# edcmain.net
KiCad netlist of a schematic drawn in EAGLE
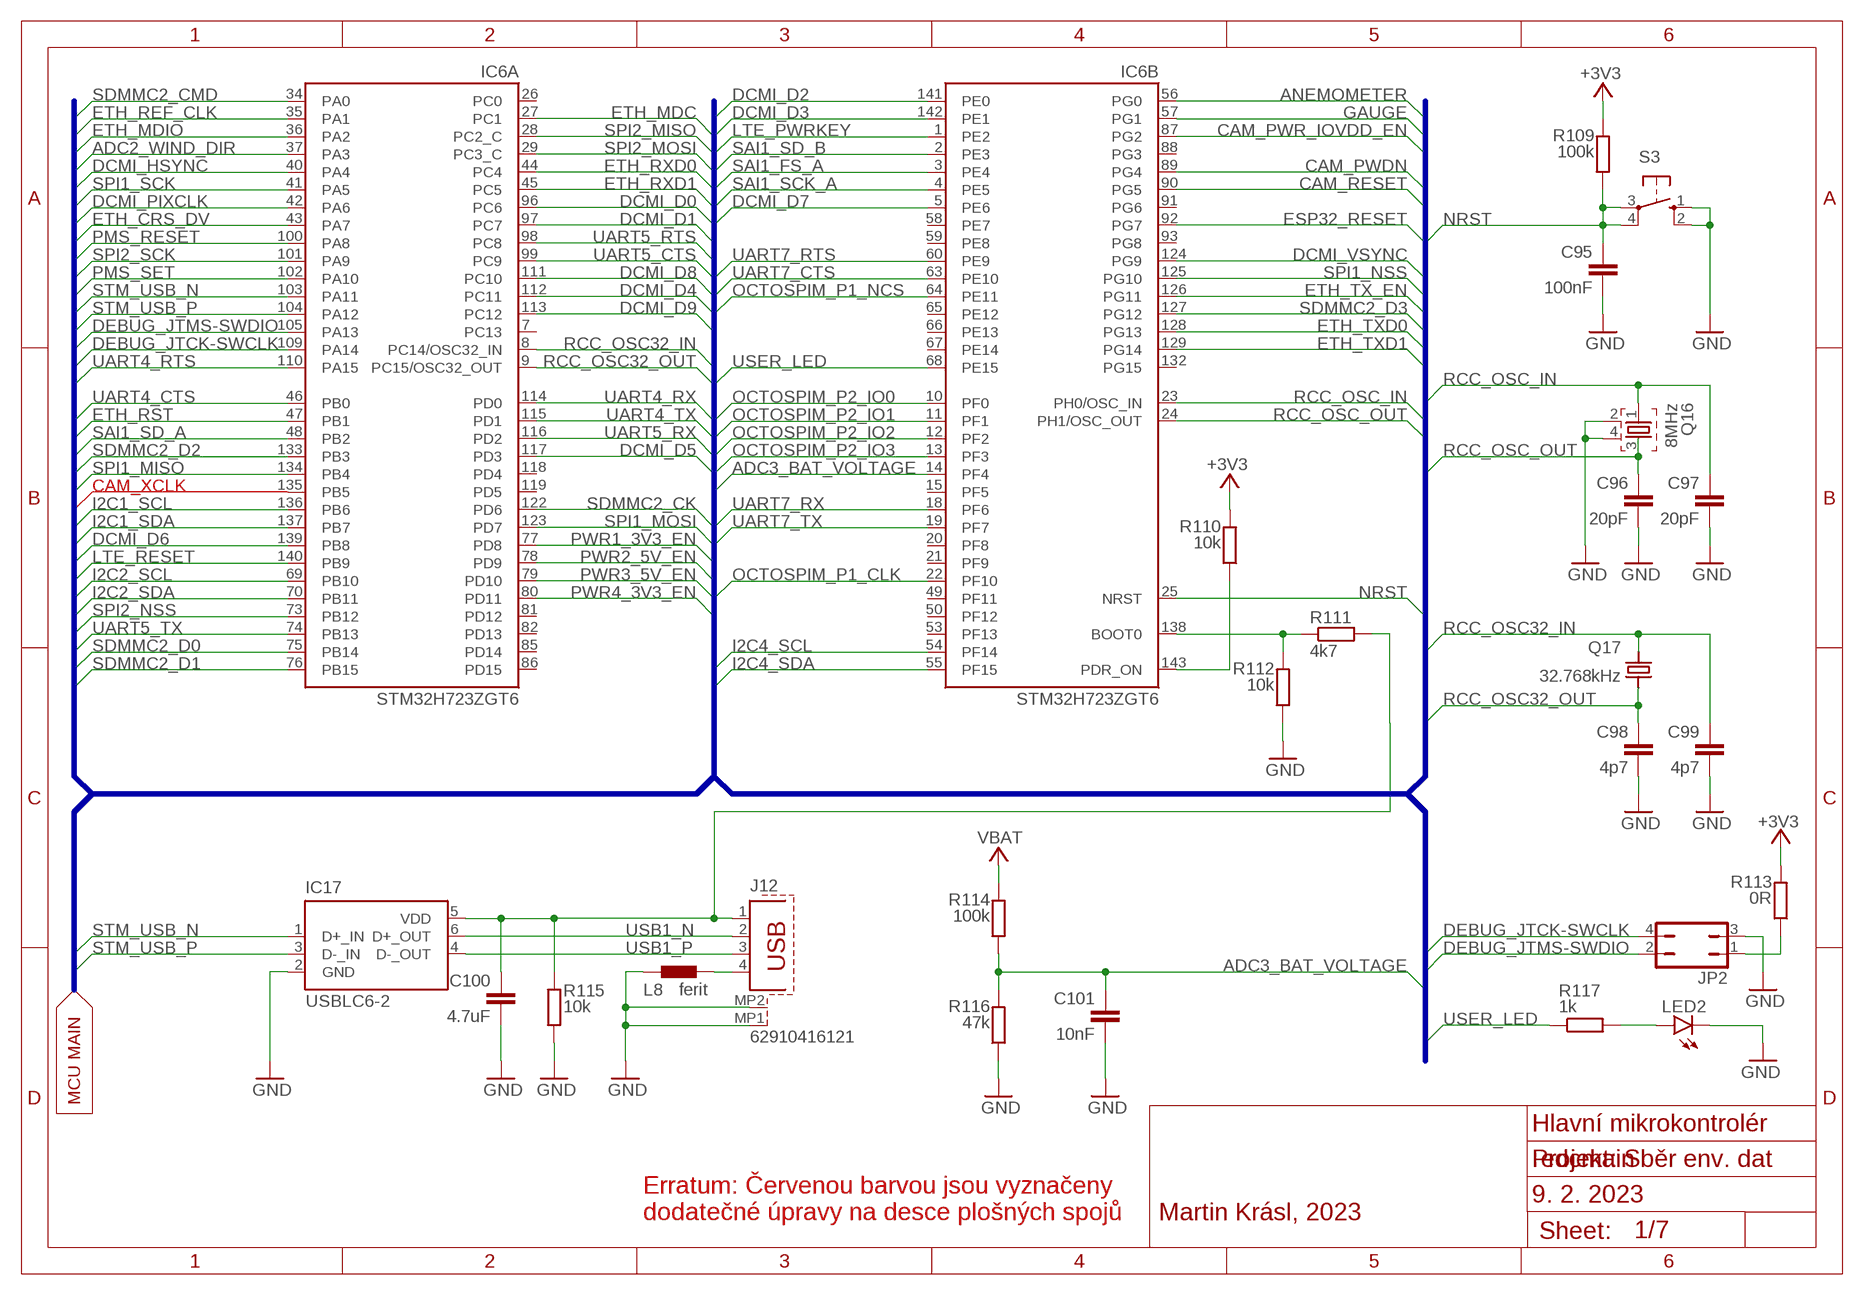
[diagram p0: schematic, sheet 1]
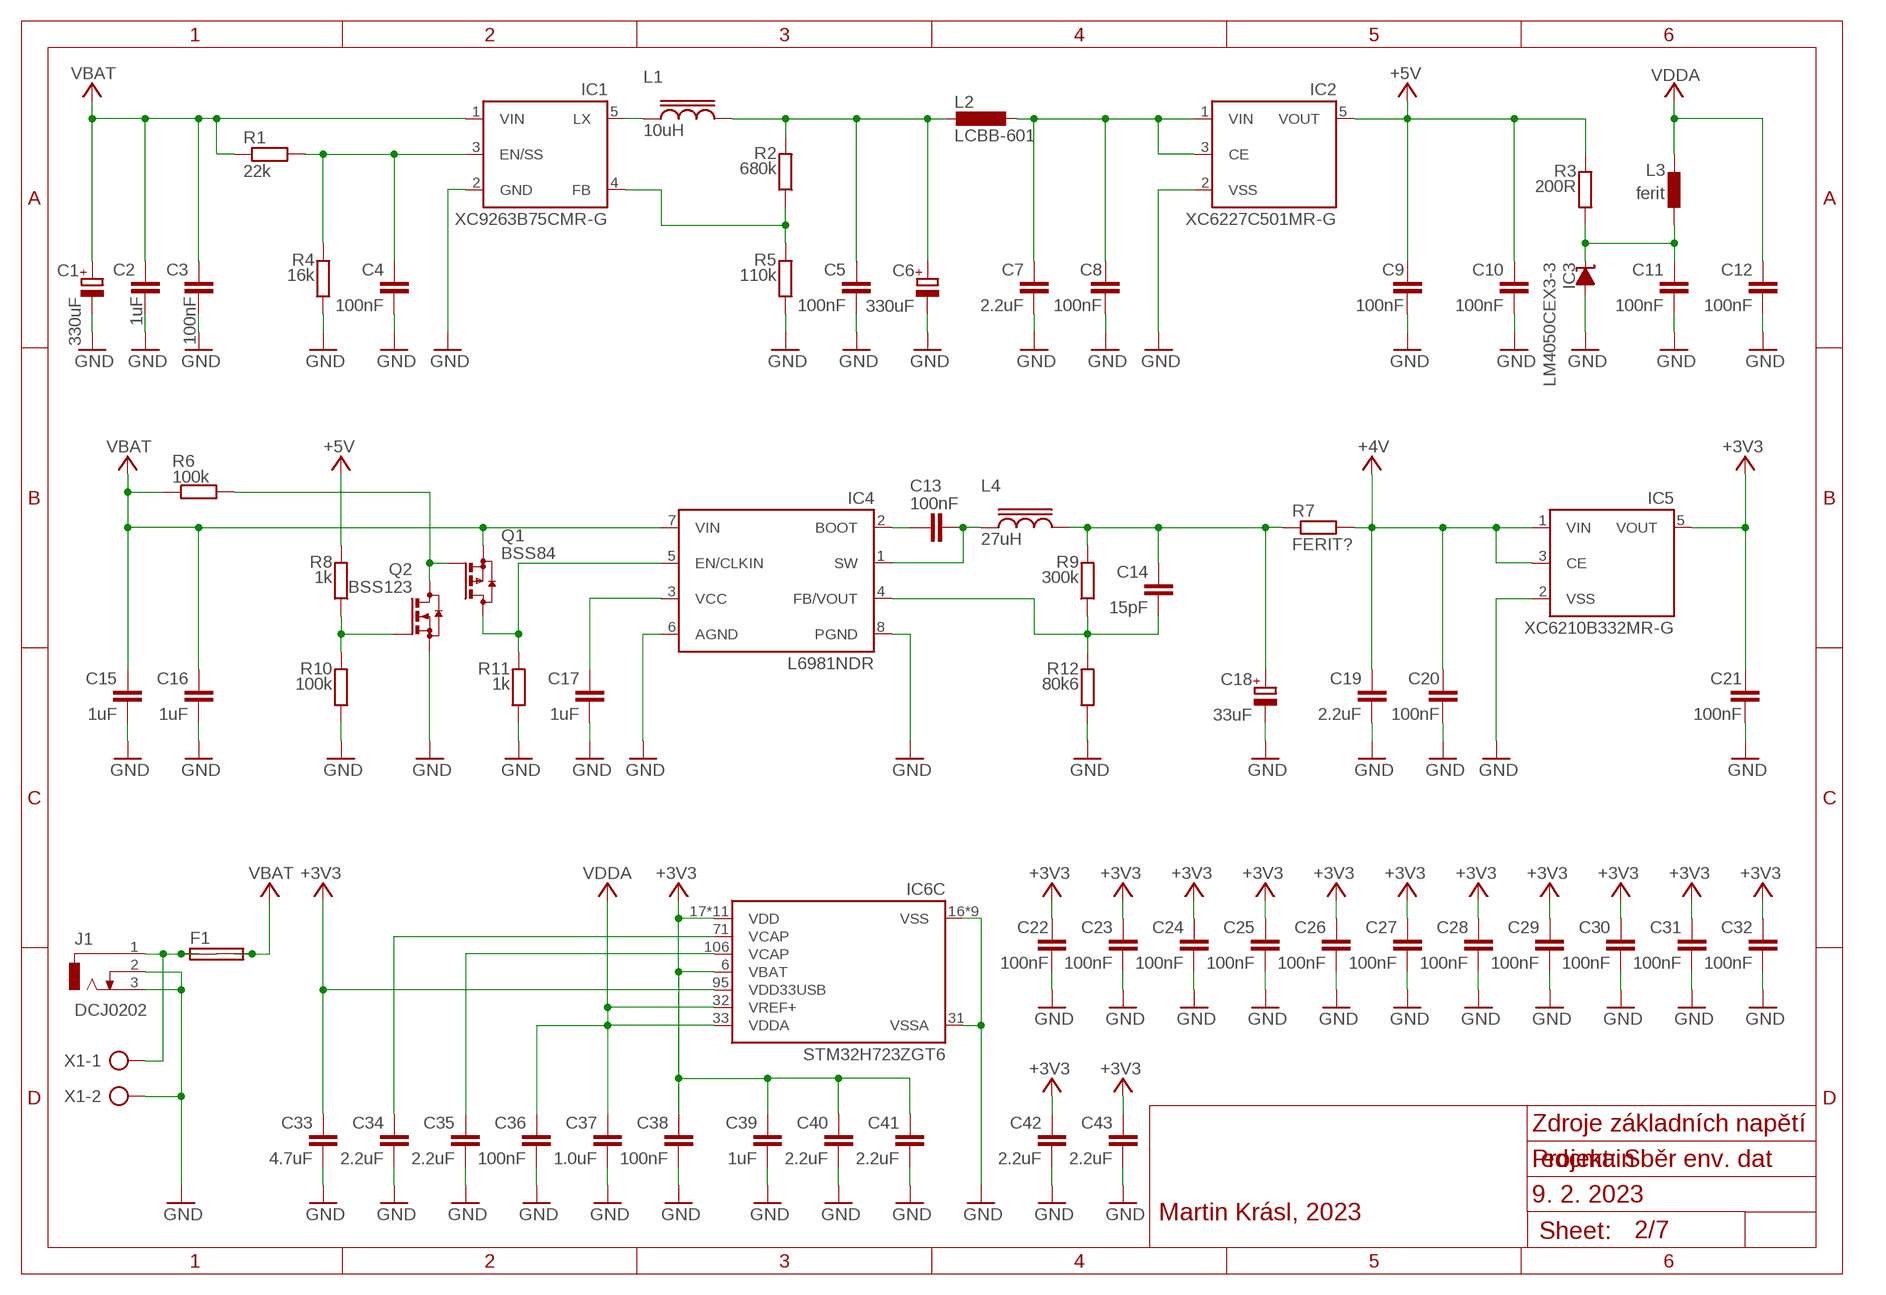
[diagram p1: schematic, sheet 2]
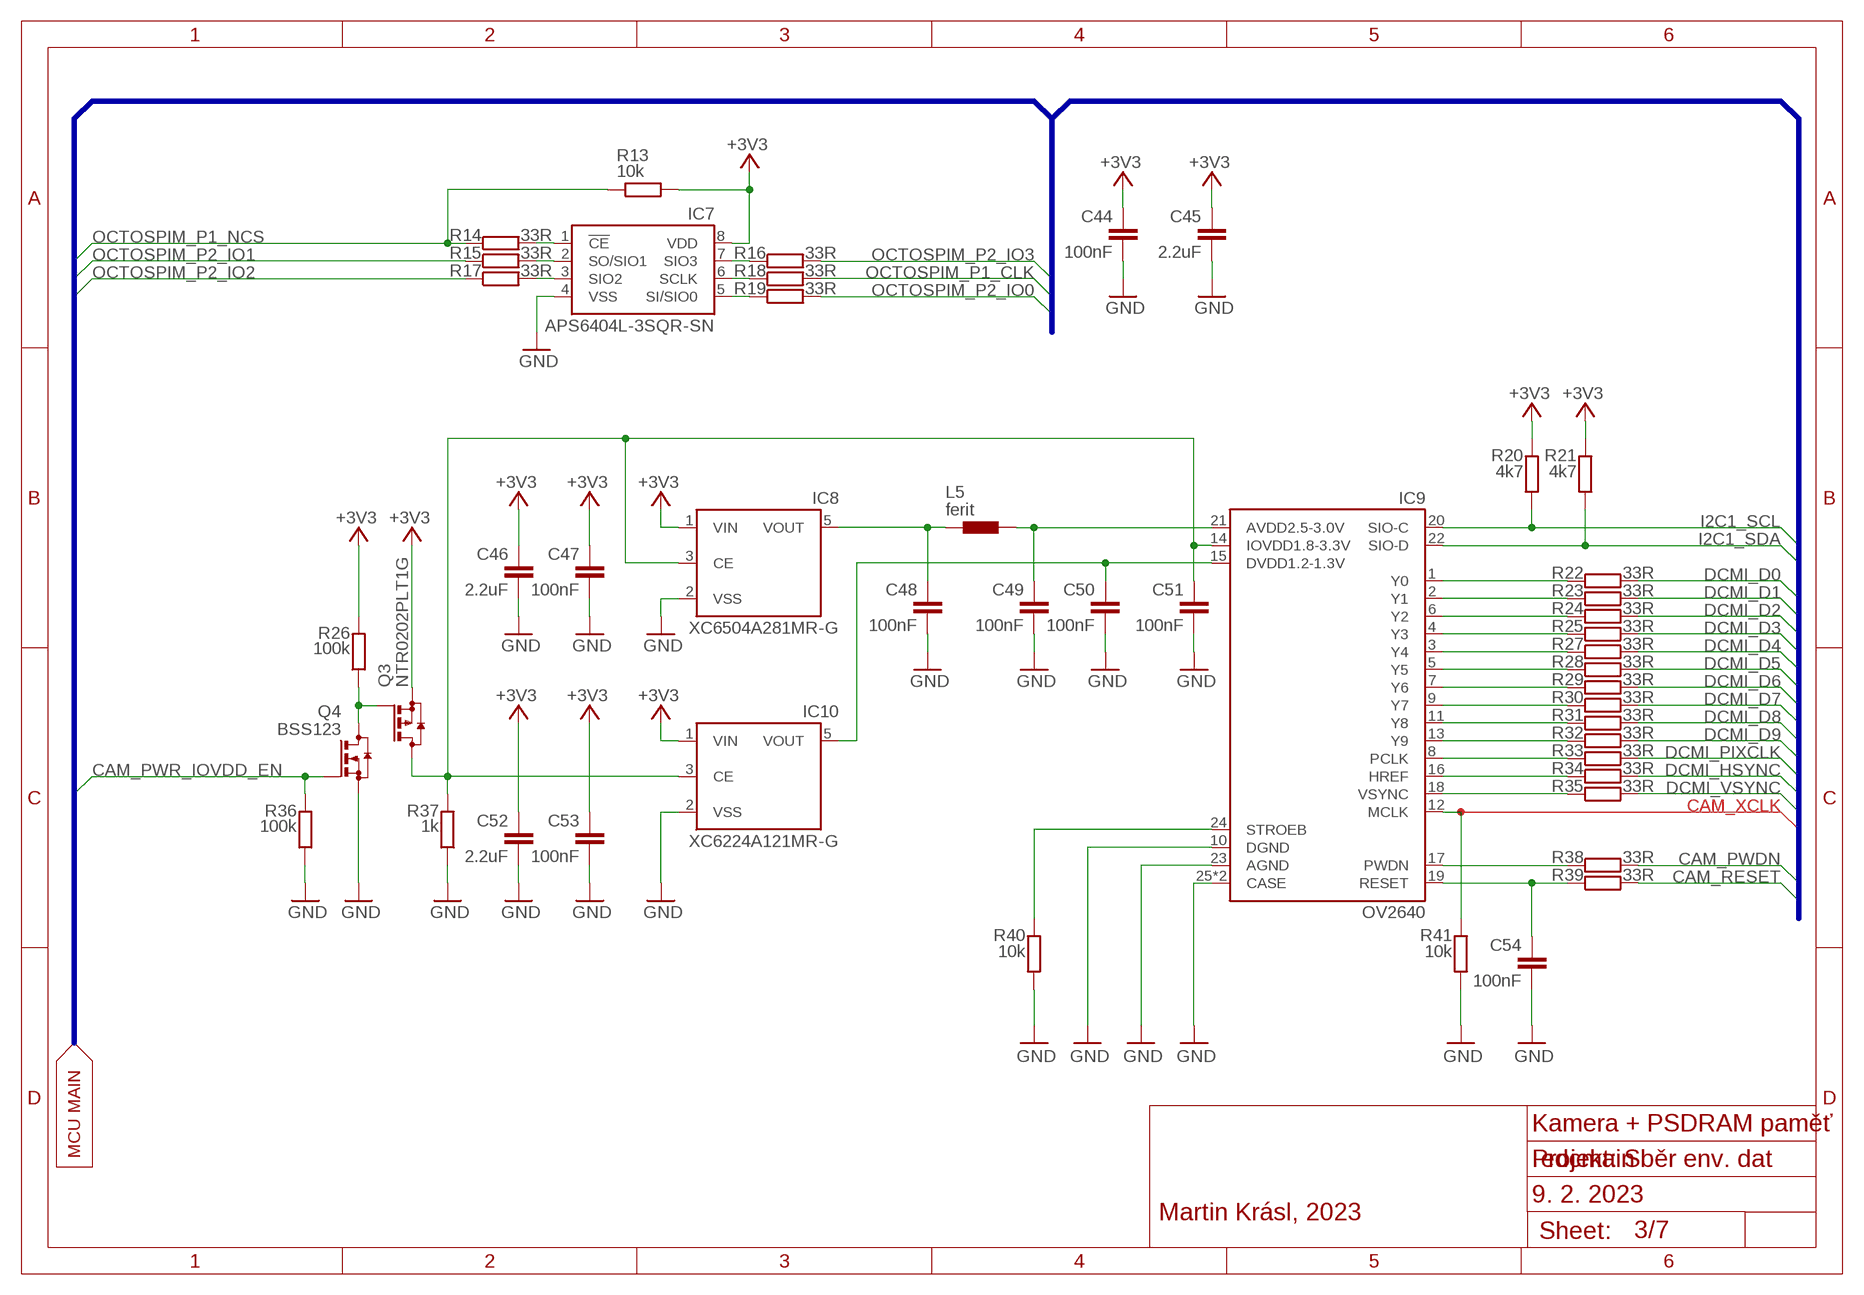
[diagram p2: schematic, sheet 3]
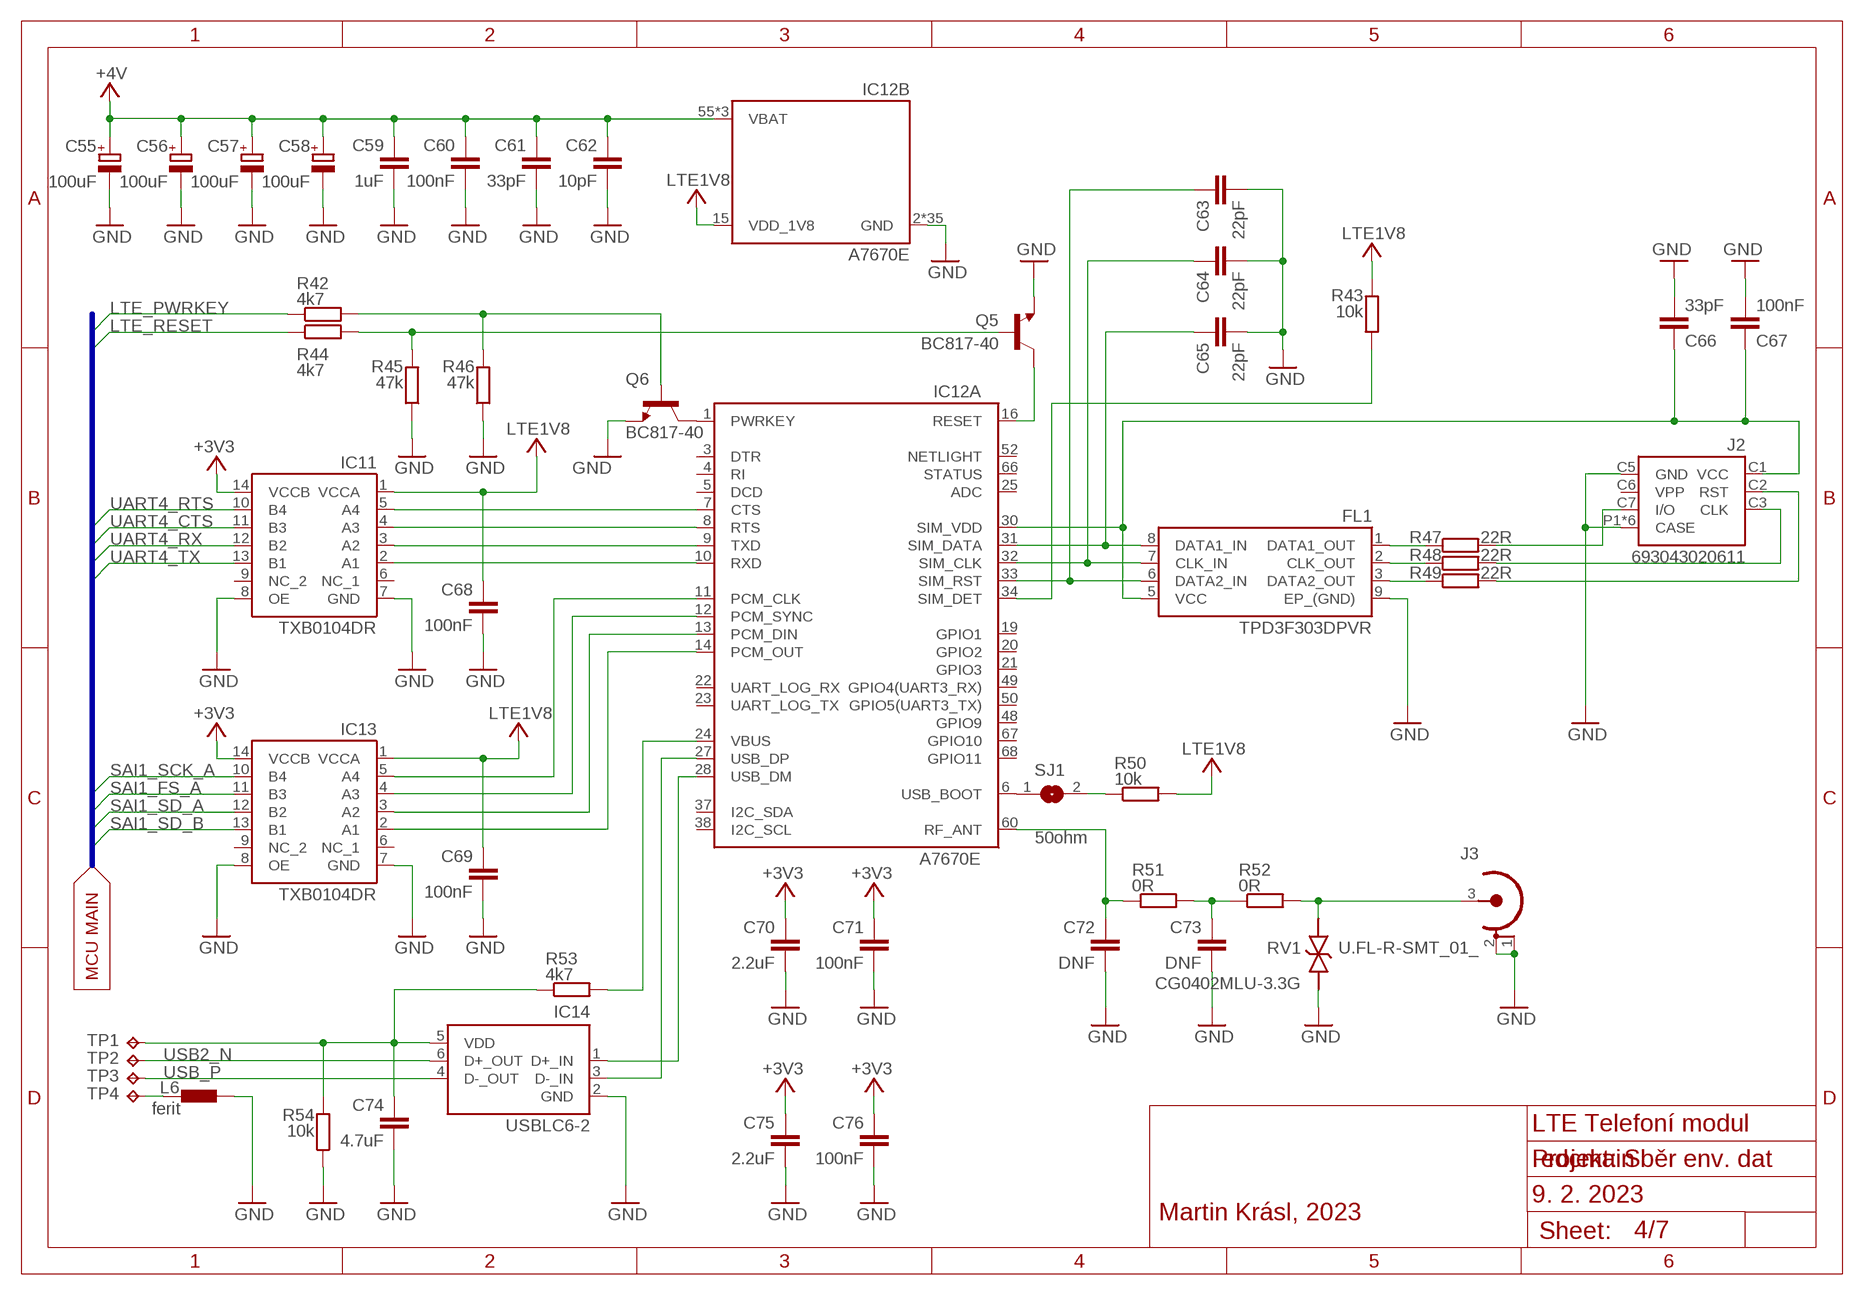
[diagram p3: schematic, sheet 4]
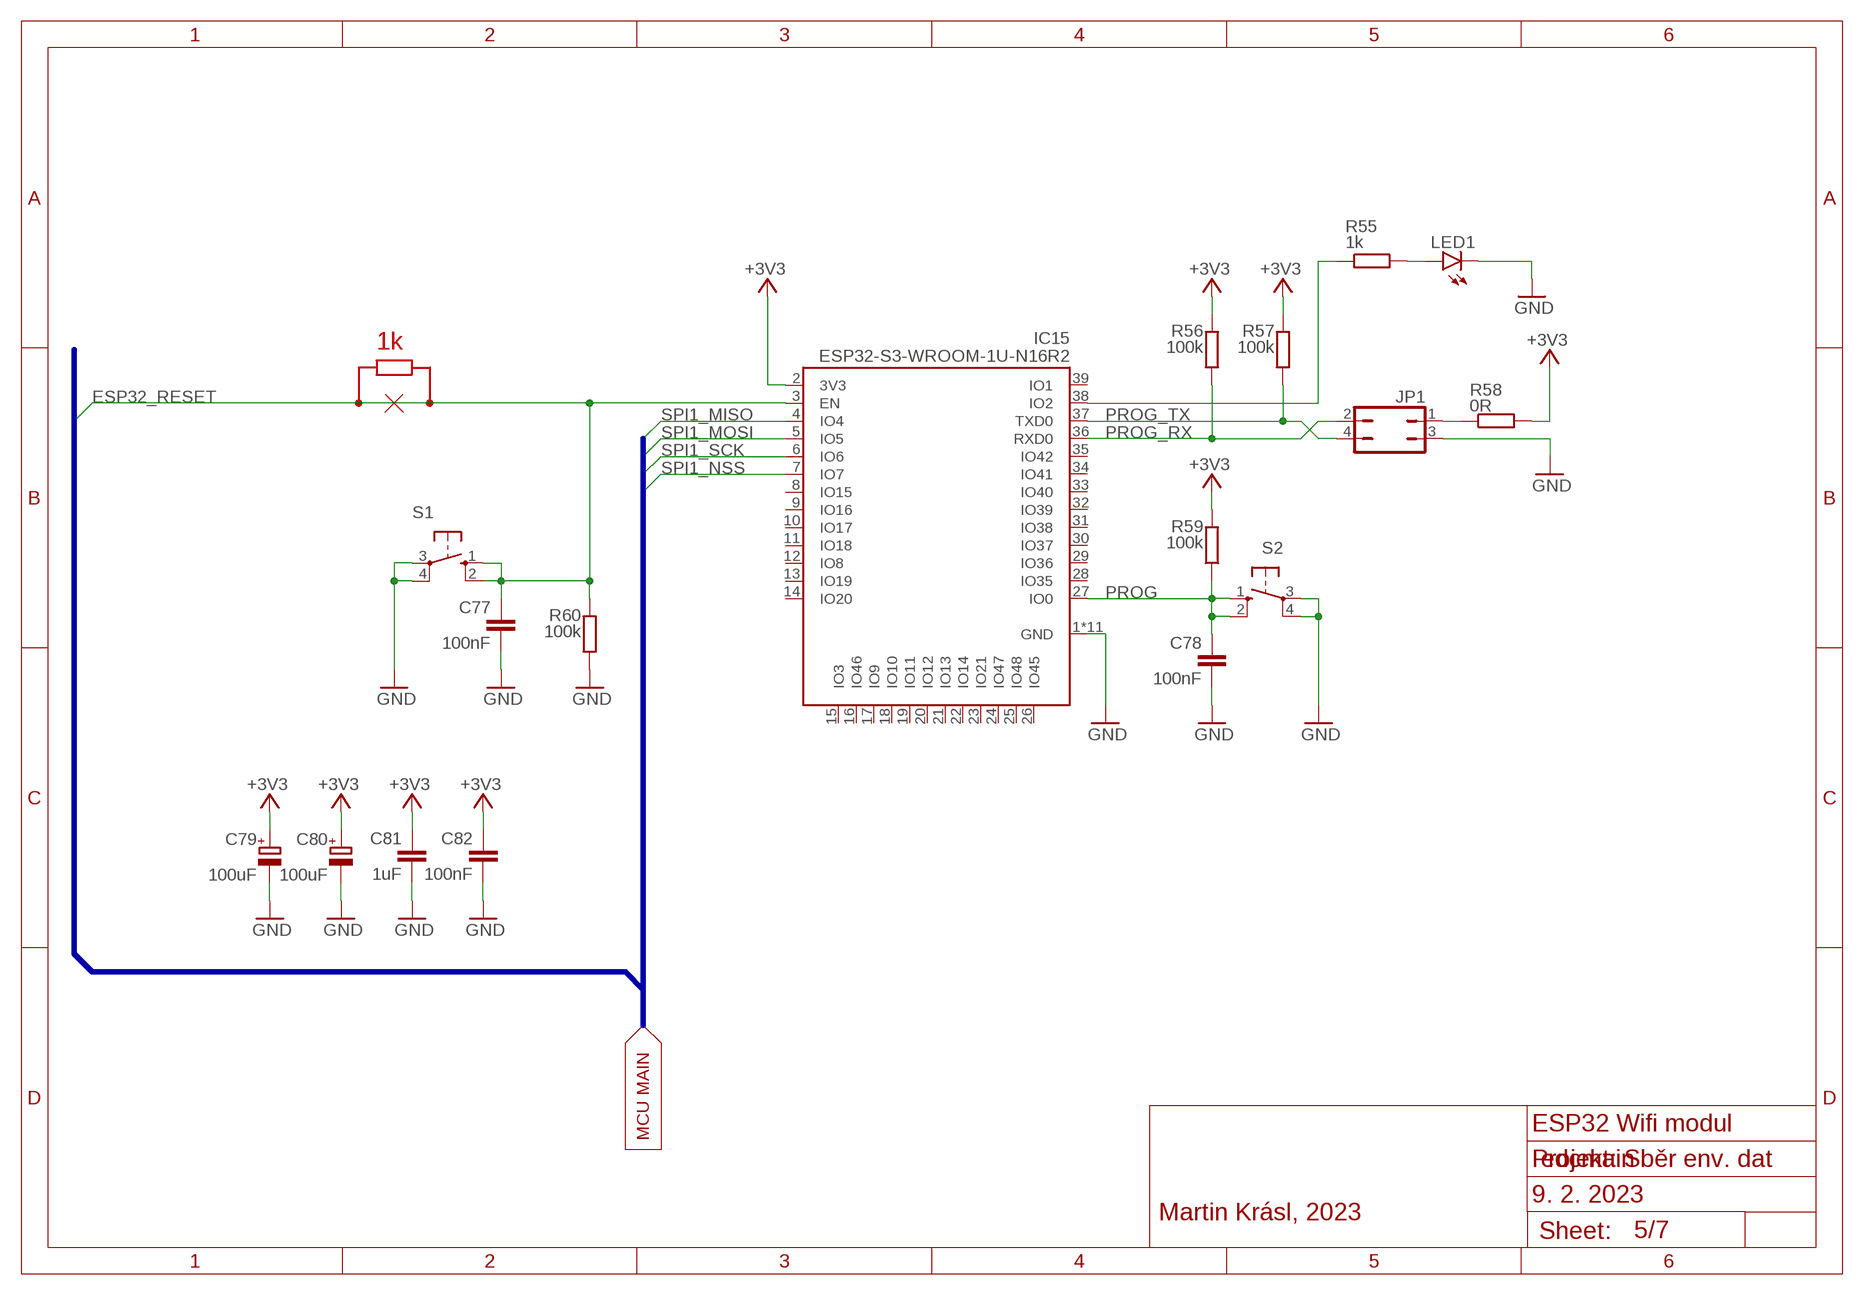
[diagram p4: schematic, sheet 5]
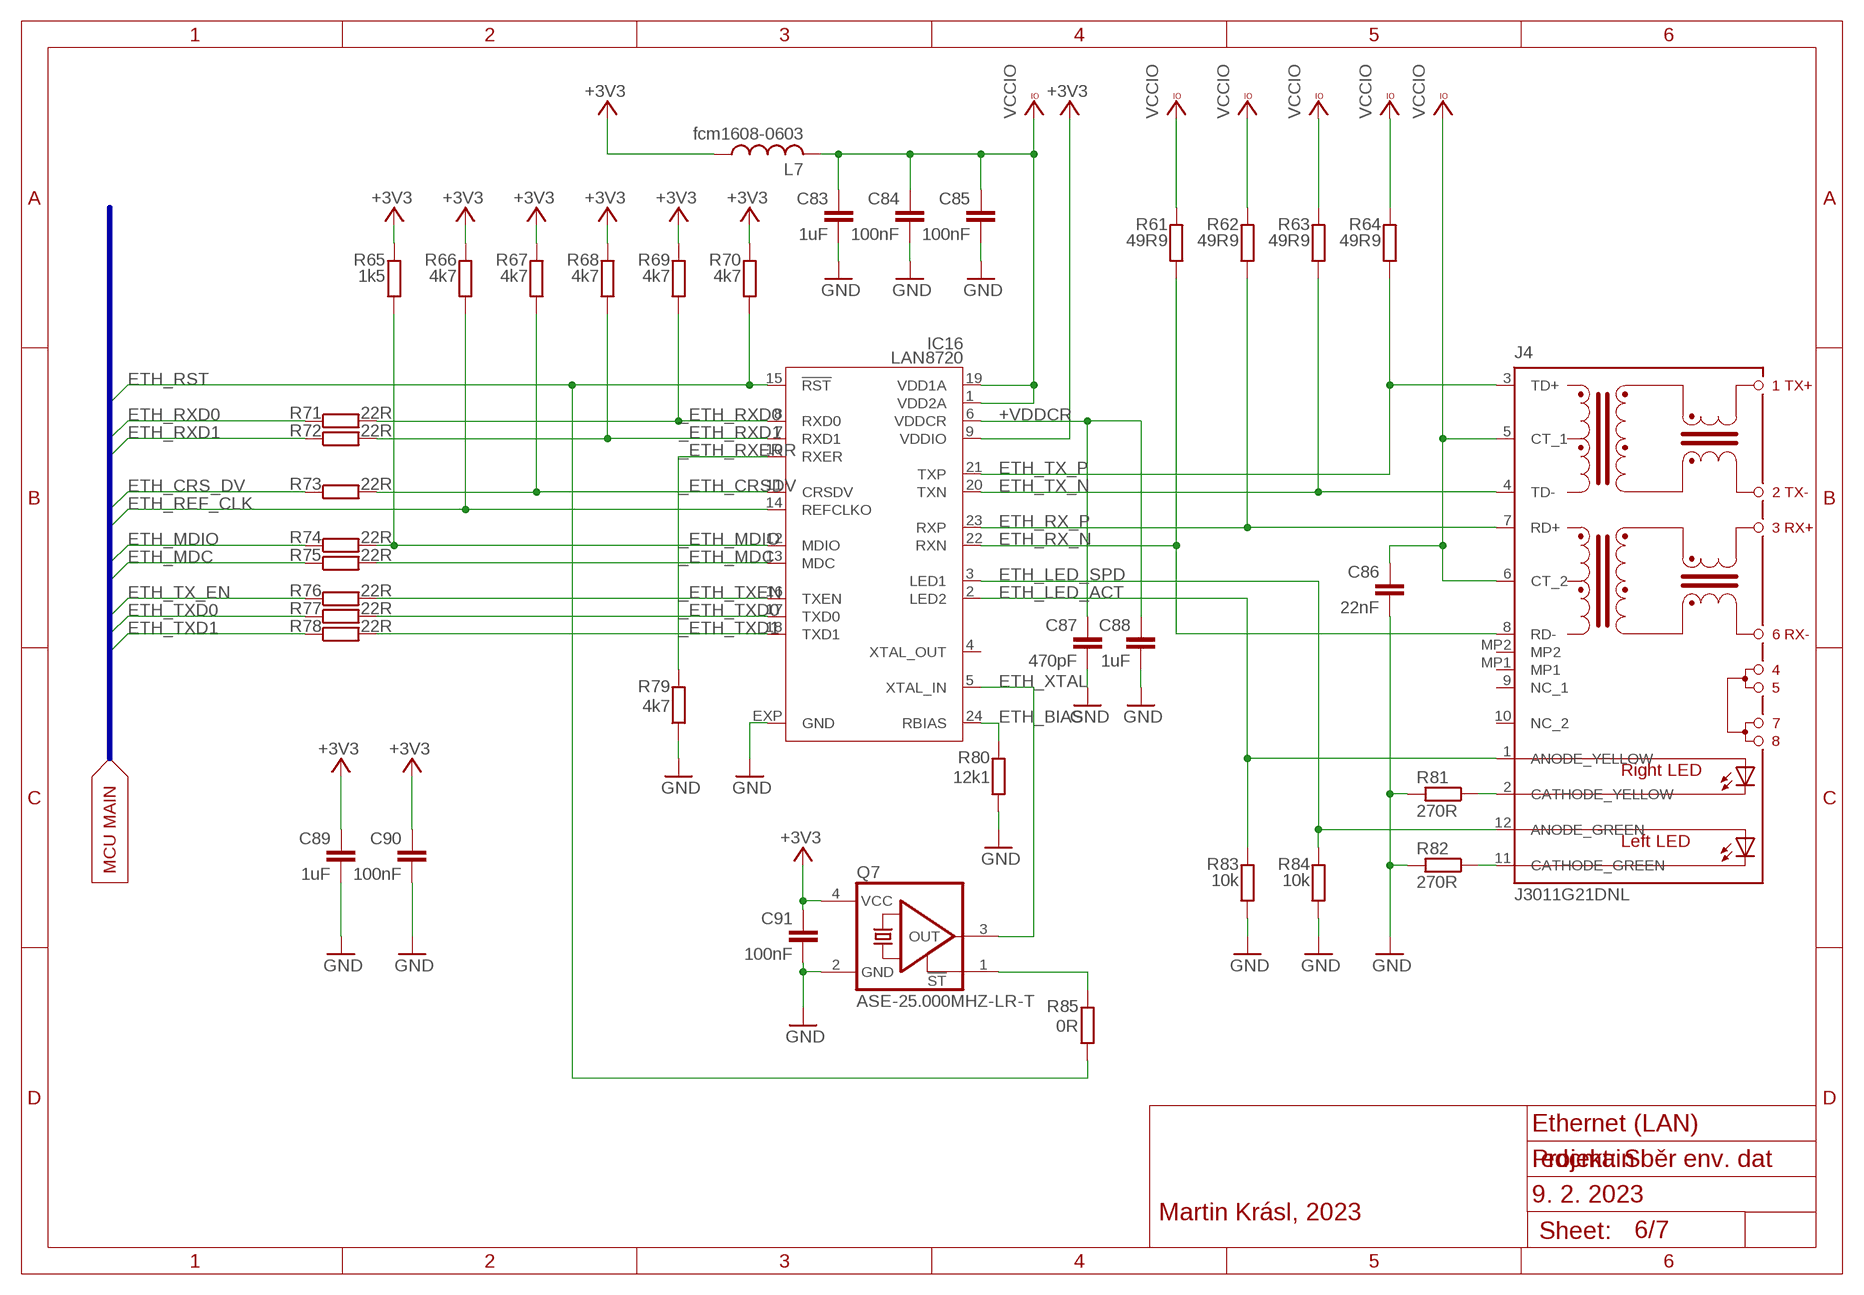
[diagram p5: schematic, sheet 6]
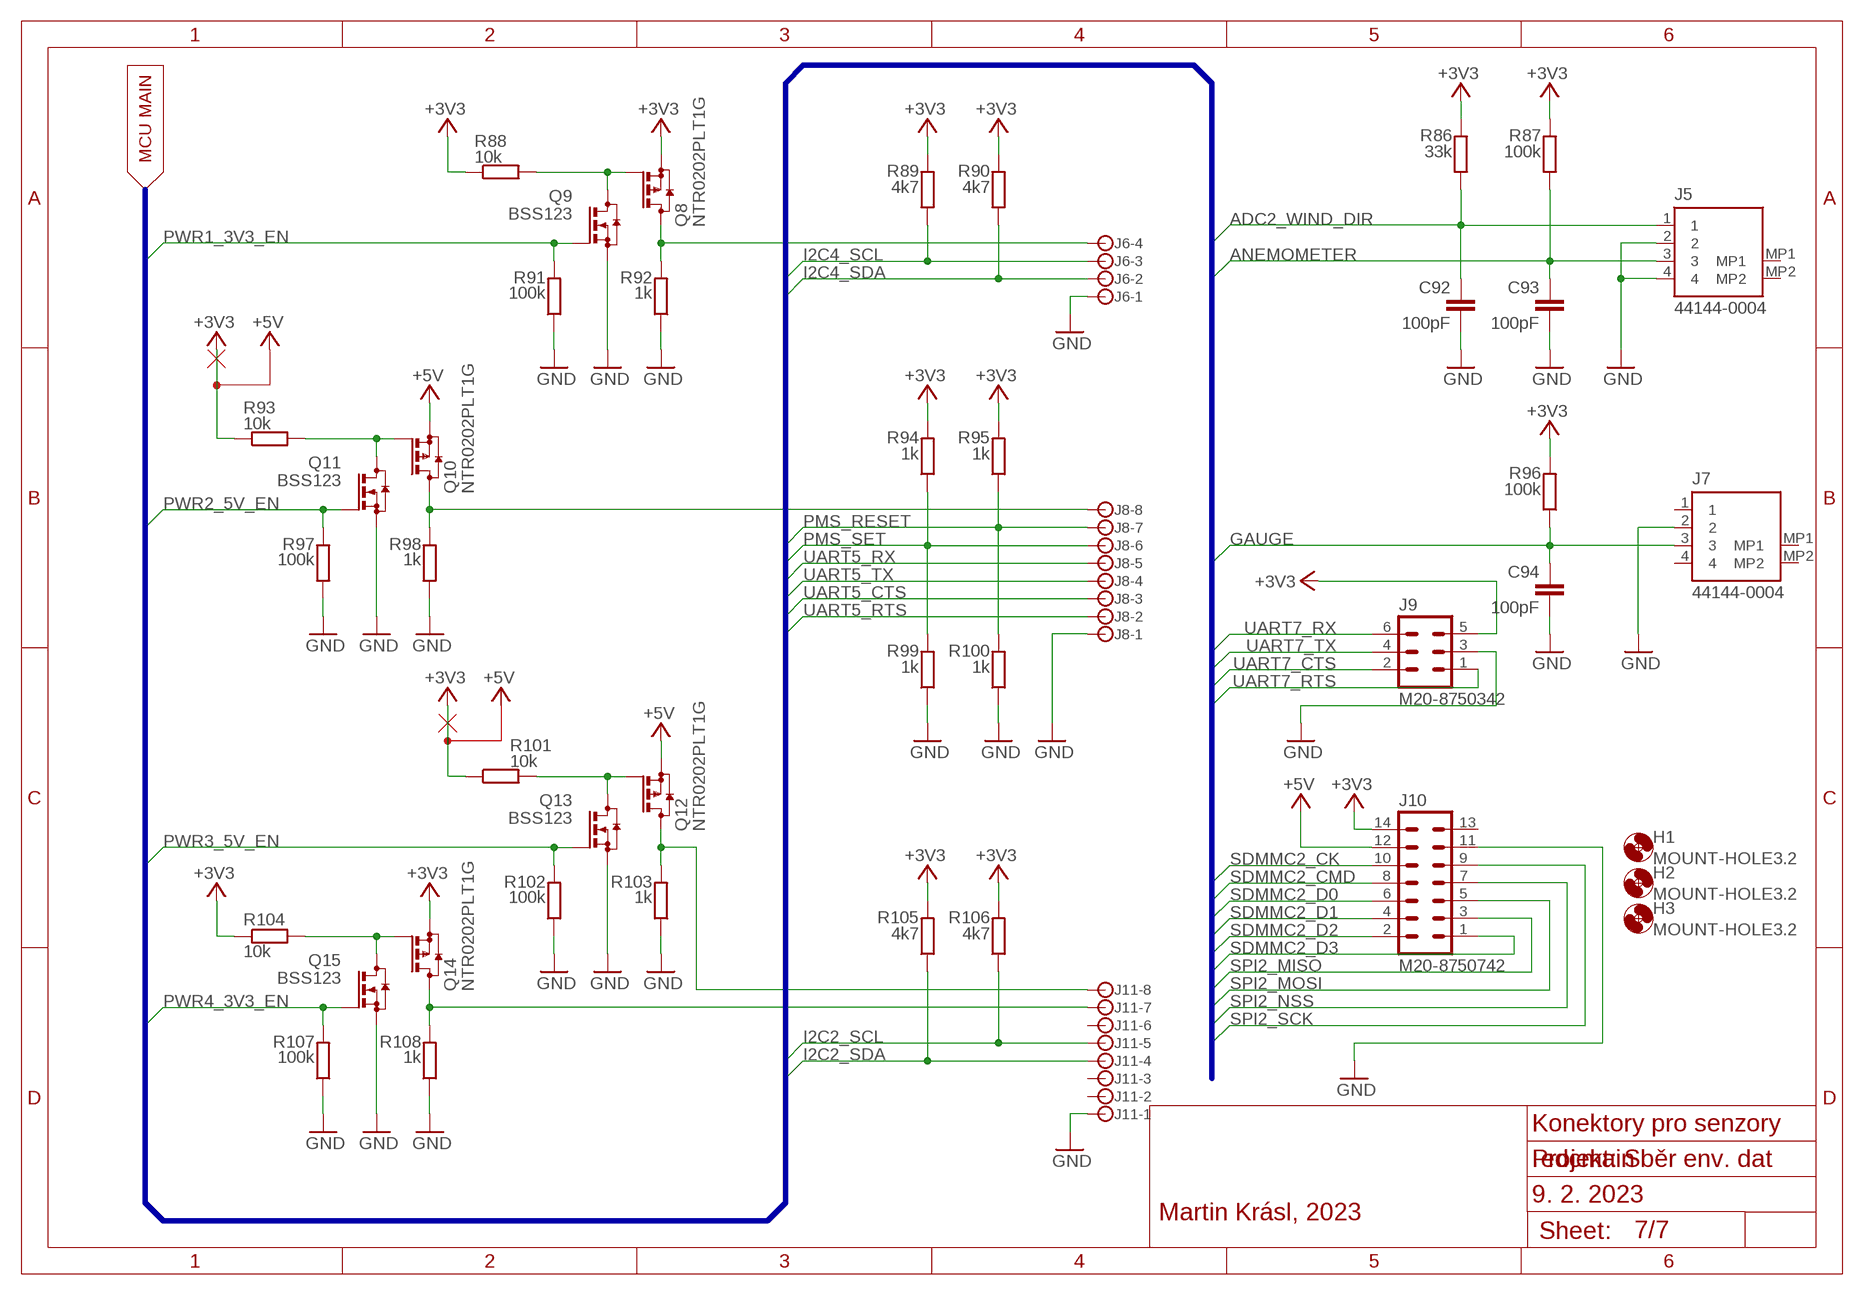
[diagram p6: schematic, sheet 7]

(export (version "E")
  (design (tool "Eeschema 10.0.6"))
  (components
    (comp (ref "C77")
      (value "100nF")
      (footprint "eagle-import:C0402")
      (libsource (lib "eagle-import") (part "C-EUC0402"))
    )
    (comp (ref "C78")
      (value "100nF")
      (footprint "eagle-import:C0402")
      (libsource (lib "eagle-import") (part "C-EUC0402"))
    )
    (comp (ref "C79")
      (value "100uF")
      (footprint "eagle-import:B_3528-21R")
      (libsource (lib "eagle-import") (part "CPOL-EUB/3528-21R"))
    )
    (comp (ref "C80")
      (value "100uF")
      (footprint "eagle-import:B_3528-21R")
      (libsource (lib "eagle-import") (part "CPOL-EUB/3528-21R"))
    )
    (comp (ref "C81")
      (value "1uF")
      (footprint "eagle-import:C0805")
      (libsource (lib "eagle-import") (part "C-EUC0805"))
    )
    (comp (ref "C82")
      (value "100nF")
      (footprint "eagle-import:C0402")
      (libsource (lib "eagle-import") (part "C-EUC0402"))
    )
    (comp (ref "IC15")
      (value "ESP32-S3-WROOM-1U-N16R2")
      (footprint "eagle-import:ESP32S3WROOM1UN16R2")
      (fields (field (name "MOUSER_PART_NUMBER") "356-ESP32S3WM1UN16R2"))
      (libsource (lib "eagle-import") (part "ESP32-S3-WROOM-1U-N16R2"))
    )
    (comp (ref "JP1")
      (value "JP2Q")
      (footprint "eagle-import:JP2Q")
      (libsource (lib "eagle-import") (part "JP2Q"))
    )
    (comp (ref "LED1")
      (value "LEDCHIP-LED0805")
      (footprint "eagle-import:CHIP-LED0805")
      (libsource (lib "eagle-import") (part "LEDCHIP-LED0805"))
    )
    (comp (ref "R55")
      (value "1k")
      (footprint "eagle-import:R0402")
      (libsource (lib "eagle-import") (part "R-EU_R0402"))
    )
    (comp (ref "R56")
      (value "100k")
      (footprint "eagle-import:R0402")
      (libsource (lib "eagle-import") (part "R-EU_R0402"))
    )
    (comp (ref "R57")
      (value "100k")
      (footprint "eagle-import:R0402")
      (libsource (lib "eagle-import") (part "R-EU_R0402"))
    )
    (comp (ref "R58")
      (value "0R")
      (footprint "eagle-import:R0402")
      (libsource (lib "eagle-import") (part "R-EU_R0402"))
    )
    (comp (ref "R59")
      (value "100k")
      (footprint "eagle-import:R0402")
      (libsource (lib "eagle-import") (part "R-EU_R0402"))
    )
    (comp (ref "R60")
      (value "100k")
      (footprint "eagle-import:R0402")
      (libsource (lib "eagle-import") (part "R-EU_R0402"))
    )
    (comp (ref "S1")
      (value "10-XX")
      (footprint "eagle-import:B3F-10XX")
      (fields (field (name "MPN") "B3F-1000"))
      (libsource (lib "eagle-import") (part "10-XX"))
    )
    (comp (ref "S2")
      (value "10-XX")
      (footprint "eagle-import:B3F-10XX")
      (fields (field (name "MPN") "B3F-1000"))
      (libsource (lib "eagle-import") (part "10-XX"))
    )
    (comp (ref "C44")
      (value "100nF")
      (footprint "eagle-import:C0402")
      (libsource (lib "eagle-import") (part "C-EUC0402"))
    )
    (comp (ref "C45")
      (value "2.2uF")
      (footprint "eagle-import:C0402")
      (libsource (lib "eagle-import") (part "C-EUC0402"))
    )
    (comp (ref "C46")
      (value "2.2uF")
      (footprint "eagle-import:C0402")
      (libsource (lib "eagle-import") (part "C-EUC0402"))
    )
    (comp (ref "C47")
      (value "100nF")
      (footprint "eagle-import:C0402")
      (libsource (lib "eagle-import") (part "C-EUC0402"))
    )
    (comp (ref "C48")
      (value "100nF")
      (footprint "eagle-import:C0402")
      (libsource (lib "eagle-import") (part "C-EUC0402"))
    )
    (comp (ref "C49")
      (value "100nF")
      (footprint "eagle-import:C0402")
      (libsource (lib "eagle-import") (part "C-EUC0402"))
    )
    (comp (ref "C50")
      (value "100nF")
      (footprint "eagle-import:C0402")
      (libsource (lib "eagle-import") (part "C-EUC0402"))
    )
    (comp (ref "C51")
      (value "100nF")
      (footprint "eagle-import:C0402")
      (libsource (lib "eagle-import") (part "C-EUC0402"))
    )
    (comp (ref "C52")
      (value "2.2uF")
      (footprint "eagle-import:C0805")
      (libsource (lib "eagle-import") (part "C-EUC0805"))
    )
    (comp (ref "C53")
      (value "100nF")
      (footprint "eagle-import:C0402")
      (libsource (lib "eagle-import") (part "C-EUC0402"))
    )
    (comp (ref "C54")
      (value "100nF")
      (footprint "eagle-import:C0402")
      (libsource (lib "eagle-import") (part "C-EUC0402"))
    )
    (comp (ref "IC7")
      (value "APS6404L-3SQR-SN")
      (footprint "eagle-import:SOP08")
      (libsource (lib "eagle-import") (part "APS6404L-3SQR-SN"))
    )
    (comp (ref "IC8")
      (value "XC6504A281MR-G")
      (footprint "eagle-import:SOT95P280X130-5N")
      (fields
        (field (name "MANUFACTURER_PART_NUMBER") "XC6210B332MR-G")
        (field (name "MOUSER_PART_NUMBER") "865-XC6210B332MR-G")
      )
      (libsource (lib "eagle-import") (part "XC6210B332MR-G"))
    )
    (comp (ref "IC9")
      (value "OV2640")
      (footprint "eagle-import:XF2M-2415-1A-SWAP")
      (libsource (lib "eagle-import") (part "OV2640"))
    )
    (comp (ref "IC10")
      (value "XC6224A121MR-G")
      (footprint "eagle-import:SOT95P280X130-5N")
      (fields
        (field (name "MANUFACTURER_PART_NUMBER") "XC6210B332MR-G")
        (field (name "MOUSER_PART_NUMBER") "865-XC6210B332MR-G")
      )
      (libsource (lib "eagle-import") (part "XC6210B332MR-G"))
    )
    (comp (ref "L5")
      (value "ferit")
      (footprint "eagle-import:0402")
      (libsource (lib "eagle-import") (part "BLM15HB121SN1"))
    )
    (comp (ref "Q3")
      (value "NTR0202PLT1G")
      (footprint "eagle-import:SOT23")
      (libsource (lib "eagle-import") (part "BSS84"))
    )
    (comp (ref "Q4")
      (value "BSS123")
      (footprint "eagle-import:SOT23")
      (libsource (lib "eagle-import") (part "BSS123"))
    )
    (comp (ref "R13")
      (value "10k")
      (footprint "eagle-import:R0402")
      (libsource (lib "eagle-import") (part "R-EU_R0402"))
    )
    (comp (ref "R14")
      (value "33R")
      (footprint "eagle-import:R0402")
      (libsource (lib "eagle-import") (part "R-EU_R0402"))
    )
    (comp (ref "R15")
      (value "33R")
      (footprint "eagle-import:R0402")
      (libsource (lib "eagle-import") (part "R-EU_R0402"))
    )
    (comp (ref "R16")
      (value "33R")
      (footprint "eagle-import:R0402")
      (libsource (lib "eagle-import") (part "R-EU_R0402"))
    )
    (comp (ref "R17")
      (value "33R")
      (footprint "eagle-import:R0402")
      (libsource (lib "eagle-import") (part "R-EU_R0402"))
    )
    (comp (ref "R18")
      (value "33R")
      (footprint "eagle-import:R0402")
      (libsource (lib "eagle-import") (part "R-EU_R0402"))
    )
    (comp (ref "R19")
      (value "33R")
      (footprint "eagle-import:R0402")
      (libsource (lib "eagle-import") (part "R-EU_R0402"))
    )
    (comp (ref "R20")
      (value "4k7")
      (footprint "eagle-import:R0402")
      (libsource (lib "eagle-import") (part "R-EU_R0402"))
    )
    (comp (ref "R21")
      (value "4k7")
      (footprint "eagle-import:R0402")
      (libsource (lib "eagle-import") (part "R-EU_R0402"))
    )
    (comp (ref "R22")
      (value "33R")
      (footprint "eagle-import:R0402")
      (libsource (lib "eagle-import") (part "R-EU_R0402"))
    )
    (comp (ref "R23")
      (value "33R")
      (footprint "eagle-import:R0402")
      (libsource (lib "eagle-import") (part "R-EU_R0402"))
    )
    (comp (ref "R24")
      (value "33R")
      (footprint "eagle-import:R0402")
      (libsource (lib "eagle-import") (part "R-EU_R0402"))
    )
    (comp (ref "R25")
      (value "33R")
      (footprint "eagle-import:R0402")
      (libsource (lib "eagle-import") (part "R-EU_R0402"))
    )
    (comp (ref "R26")
      (value "100k")
      (footprint "eagle-import:R0402")
      (libsource (lib "eagle-import") (part "R-EU_R0402"))
    )
    (comp (ref "R27")
      (value "33R")
      (footprint "eagle-import:R0402")
      (libsource (lib "eagle-import") (part "R-EU_R0402"))
    )
    (comp (ref "R28")
      (value "33R")
      (footprint "eagle-import:R0402")
      (libsource (lib "eagle-import") (part "R-EU_R0402"))
    )
    (comp (ref "R29")
      (value "33R")
      (footprint "eagle-import:R0402")
      (libsource (lib "eagle-import") (part "R-EU_R0402"))
    )
    (comp (ref "R30")
      (value "33R")
      (footprint "eagle-import:R0402")
      (libsource (lib "eagle-import") (part "R-EU_R0402"))
    )
    (comp (ref "R31")
      (value "33R")
      (footprint "eagle-import:R0402")
      (libsource (lib "eagle-import") (part "R-EU_R0402"))
    )
    (comp (ref "R32")
      (value "33R")
      (footprint "eagle-import:R0402")
      (libsource (lib "eagle-import") (part "R-EU_R0402"))
    )
    (comp (ref "R33")
      (value "33R")
      (footprint "eagle-import:R0402")
      (libsource (lib "eagle-import") (part "R-EU_R0402"))
    )
    (comp (ref "R34")
      (value "33R")
      (footprint "eagle-import:R0402")
      (libsource (lib "eagle-import") (part "R-EU_R0402"))
    )
    (comp (ref "R35")
      (value "33R")
      (footprint "eagle-import:R0402")
      (libsource (lib "eagle-import") (part "R-EU_R0402"))
    )
    (comp (ref "R36")
      (value "100k")
      (footprint "eagle-import:R0402")
      (libsource (lib "eagle-import") (part "R-EU_R0402"))
    )
    (comp (ref "R37")
      (value "1k")
      (footprint "eagle-import:R0402")
      (libsource (lib "eagle-import") (part "R-EU_R0402"))
    )
    (comp (ref "R38")
      (value "33R")
      (footprint "eagle-import:R0402")
      (libsource (lib "eagle-import") (part "R-EU_R0402"))
    )
    (comp (ref "R39")
      (value "33R")
      (footprint "eagle-import:R0402")
      (libsource (lib "eagle-import") (part "R-EU_R0402"))
    )
    (comp (ref "R40")
      (value "10k")
      (footprint "eagle-import:R0402")
      (libsource (lib "eagle-import") (part "R-EU_R0402"))
    )
    (comp (ref "R41")
      (value "10k")
      (footprint "eagle-import:R0402")
      (libsource (lib "eagle-import") (part "R-EU_R0402"))
    )
    (comp (ref "C1")
      (value "330uF")
      (footprint "eagle-import:PANASONIC_G")
      (libsource (lib "eagle-import") (part "CPOL-EUG"))
    )
    (comp (ref "C2")
      (value "1uF")
      (footprint "eagle-import:C0805")
      (libsource (lib "eagle-import") (part "C-EUC0805"))
    )
    (comp (ref "C3")
      (value "100nF")
      (footprint "eagle-import:C0402")
      (libsource (lib "eagle-import") (part "C-EUC0402"))
    )
    (comp (ref "C4")
      (value "100nF")
      (footprint "eagle-import:C0402")
      (libsource (lib "eagle-import") (part "C-EUC0402"))
    )
    (comp (ref "C5")
      (value "100nF")
      (footprint "eagle-import:C0402")
      (libsource (lib "eagle-import") (part "C-EUC0402"))
    )
    (comp (ref "C6")
      (value "330uF")
      (footprint "eagle-import:PANASONIC_G")
      (libsource (lib "eagle-import") (part "CPOL-EUG"))
    )
    (comp (ref "C7")
      (value "2.2uF")
      (footprint "eagle-import:C0805")
      (libsource (lib "eagle-import") (part "C-EUC0805"))
    )
    (comp (ref "C8")
      (value "100nF")
      (footprint "eagle-import:C0402")
      (libsource (lib "eagle-import") (part "C-EUC0402"))
    )
    (comp (ref "C9")
      (value "100nF")
      (footprint "eagle-import:C0402")
      (libsource (lib "eagle-import") (part "C-EUC0402"))
    )
    (comp (ref "C10")
      (value "100nF")
      (footprint "eagle-import:C0402")
      (libsource (lib "eagle-import") (part "C-EUC0402"))
    )
    (comp (ref "C11")
      (value "100nF")
      (footprint "eagle-import:C0402")
      (libsource (lib "eagle-import") (part "C-EUC0402"))
    )
    (comp (ref "C12")
      (value "100nF")
      (footprint "eagle-import:C0402")
      (libsource (lib "eagle-import") (part "C-EUC0402"))
    )
    (comp (ref "C13")
      (value "100nF")
      (footprint "eagle-import:C0402")
      (libsource (lib "eagle-import") (part "C-EUC0402"))
    )
    (comp (ref "C14")
      (value "15pF")
      (footprint "eagle-import:C0402")
      (libsource (lib "eagle-import") (part "C-EUC0402"))
    )
    (comp (ref "C15")
      (value "1uF")
      (footprint "eagle-import:C0805")
      (libsource (lib "eagle-import") (part "C-EUC0805"))
    )
    (comp (ref "C16")
      (value "1uF")
      (footprint "eagle-import:C0805")
      (libsource (lib "eagle-import") (part "C-EUC0805"))
    )
    (comp (ref "C17")
      (value "1uF")
      (footprint "eagle-import:C0402")
      (libsource (lib "eagle-import") (part "C-EUC0402"))
    )
    (comp (ref "C18")
      (value "33uF")
      (footprint "eagle-import:PANASONIC_G")
      (libsource (lib "eagle-import") (part "CPOL-EUG"))
    )
    (comp (ref "C19")
      (value "2.2uF")
      (footprint "eagle-import:C0402")
      (libsource (lib "eagle-import") (part "C-EUC0402"))
    )
    (comp (ref "C20")
      (value "100nF")
      (footprint "eagle-import:C0402")
      (libsource (lib "eagle-import") (part "C-EUC0402"))
    )
    (comp (ref "C21")
      (value "100nF")
      (footprint "eagle-import:C0402")
      (libsource (lib "eagle-import") (part "C-EUC0402"))
    )
    (comp (ref "C22")
      (value "100nF")
      (footprint "eagle-import:C0402")
      (libsource (lib "eagle-import") (part "C-EUC0402"))
    )
    (comp (ref "C23")
      (value "100nF")
      (footprint "eagle-import:C0402")
      (libsource (lib "eagle-import") (part "C-EUC0402"))
    )
    (comp (ref "C24")
      (value "100nF")
      (footprint "eagle-import:C0402")
      (libsource (lib "eagle-import") (part "C-EUC0402"))
    )
    (comp (ref "C25")
      (value "100nF")
      (footprint "eagle-import:C0402")
      (libsource (lib "eagle-import") (part "C-EUC0402"))
    )
    (comp (ref "C26")
      (value "100nF")
      (footprint "eagle-import:C0402")
      (libsource (lib "eagle-import") (part "C-EUC0402"))
    )
    (comp (ref "C27")
      (value "100nF")
      (footprint "eagle-import:C0402")
      (libsource (lib "eagle-import") (part "C-EUC0402"))
    )
    (comp (ref "C28")
      (value "100nF")
      (footprint "eagle-import:C0402")
      (libsource (lib "eagle-import") (part "C-EUC0402"))
    )
    (comp (ref "C29")
      (value "100nF")
      (footprint "eagle-import:C0402")
      (libsource (lib "eagle-import") (part "C-EUC0402"))
    )
    (comp (ref "C30")
      (value "100nF")
      (footprint "eagle-import:C0402")
      (libsource (lib "eagle-import") (part "C-EUC0402"))
    )
    (comp (ref "C31")
      (value "100nF")
      (footprint "eagle-import:C0402")
      (libsource (lib "eagle-import") (part "C-EUC0402"))
    )
    (comp (ref "C32")
      (value "100nF")
      (footprint "eagle-import:C0402")
      (libsource (lib "eagle-import") (part "C-EUC0402"))
    )
    (comp (ref "C33")
      (value "4.7uF")
      (footprint "eagle-import:C0402")
      (libsource (lib "eagle-import") (part "C-EUC0402"))
    )
    (comp (ref "C34")
      (value "2.2uF")
      (footprint "eagle-import:C0805")
      (libsource (lib "eagle-import") (part "C-EUC0805"))
    )
    (comp (ref "C35")
      (value "2.2uF")
      (footprint "eagle-import:C0805")
      (libsource (lib "eagle-import") (part "C-EUC0805"))
    )
    (comp (ref "C36")
      (value "100nF")
      (footprint "eagle-import:C0402")
      (libsource (lib "eagle-import") (part "C-EUC0402"))
    )
    (comp (ref "C37")
      (value "1.0uF")
      (footprint "eagle-import:C0402")
      (libsource (lib "eagle-import") (part "C-EUC0402"))
    )
    (comp (ref "C38")
      (value "100nF")
      (footprint "eagle-import:C0402")
      (libsource (lib "eagle-import") (part "C-EUC0402"))
    )
    (comp (ref "C39")
      (value "1uF")
      (footprint "eagle-import:C0402")
      (libsource (lib "eagle-import") (part "C-EUC0402"))
    )
    (comp (ref "C40")
      (value "2.2uF")
      (footprint "eagle-import:C0402")
      (libsource (lib "eagle-import") (part "C-EUC0402"))
    )
    (comp (ref "C41")
      (value "2.2uF")
      (footprint "eagle-import:C0402")
      (libsource (lib "eagle-import") (part "C-EUC0402"))
    )
    (comp (ref "C42")
      (value "2.2uF")
      (footprint "eagle-import:C0402")
      (libsource (lib "eagle-import") (part "C-EUC0402"))
    )
    (comp (ref "C43")
      (value "2.2uF")
      (footprint "eagle-import:C0805")
      (libsource (lib "eagle-import") (part "C-EUC0805"))
    )
    (comp (ref "F1")
      (value "SHK20L")
      (footprint "eagle-import:SHK20L")
      (libsource (lib "eagle-import") (part "SHK20L"))
    )
    (comp (ref "IC1")
      (value "XC9263B75CMR-G")
      (footprint "eagle-import:SOT95P280X130-5N")
      (fields
        (field (name "MANUFACTURER_PART_NUMBER") "XC9263B755MR-G")
        (field (name "MOUSER_PART_NUMBER") "865-XC9263B755MR-G")
      )
      (libsource (lib "eagle-import") (part "XC9263B755MR-G"))
    )
    (comp (ref "IC2")
      (value "XC6227C501MR-G")
      (footprint "eagle-import:SOT95P280X130-5N")
      (fields
        (field (name "MANUFACTURER_PART_NUMBER") "XC6210B332MR-G")
        (field (name "MOUSER_PART_NUMBER") "865-XC6210B332MR-G")
      )
      (libsource (lib "eagle-import") (part "XC6210B332MR-G"))
    )
    (comp (ref "IC3")
      (value "LM4050CEX3-3")
      (footprint "eagle-import:SC70-3")
      (libsource (lib "eagle-import") (part "LM4041"))
    )
    (comp (ref "IC4")
      (value "L6981NDR")
      (footprint "eagle-import:SOIC127P600X175-8N")
      (fields (field (name "MOUSER_PART_NUMBER") "511-L6981NDR"))
      (libsource (lib "eagle-import") (part "L6981NDR"))
    )
    (comp (ref "IC5")
      (value "XC6210B332MR-G")
      (footprint "eagle-import:SOT95P280X130-5N")
      (fields (field (name "MOUSER_PART_NUMBER") "865-XC6210B332MR-G"))
      (libsource (lib "eagle-import") (part "XC6210B332MR-G"))
    )
    (comp (ref "IC6")
      (value "STM32H723ZGT6")
      (footprint "eagle-import:QFP50P2200X2200X160-144N")
      (fields (field (name "MOUSER_PART_NUMBER") "511-STM32H723ZGT6"))
      (libsource (lib "eagle-import") (part "STM32H723ZGT6"))
    )
    (comp (ref "IMG1")
      (value "IMAGEPRINT")
      (footprint "eagle-import:RD_14_24_PRINT")
      (libsource (lib "eagle-import") (part "IMAGEPRINT"))
    )
    (comp (ref "J1")
      (value "DCJ0202")
      (footprint "eagle-import:DCJ0202")
      (libsource (lib "eagle-import") (part "DCJ0202"))
    )
    (comp (ref "L1")
      (value "10uH")
      (footprint "eagle-import:L6")
      (libsource (lib "eagle-import") (part "INDUCTORLQH5BP|4D28"))
    )
    (comp (ref "L2")
      (value "LCBB-601")
      (footprint "eagle-import:L2012C")
      (libsource (lib "eagle-import") (part "L-EU2012(0805)"))
    )
    (comp (ref "L3")
      (value "ferit")
      (footprint "eagle-import:0402")
      (libsource (lib "eagle-import") (part "BLM15HB121SN1"))
    )
    (comp (ref "L4")
      (value "27uH")
      (footprint "eagle-import:L6")
      (libsource (lib "eagle-import") (part "INDUCTORLQH5BP|4D28"))
    )
    (comp (ref "Q1")
      (value "BSS84")
      (footprint "eagle-import:SOT23")
      (libsource (lib "eagle-import") (part "BSS84"))
    )
    (comp (ref "Q2")
      (value "BSS123")
      (footprint "eagle-import:SOT23")
      (libsource (lib "eagle-import") (part "BSS123"))
    )
    (comp (ref "R1")
      (value "22k")
      (footprint "eagle-import:R0402")
      (libsource (lib "eagle-import") (part "R-EU_R0402"))
    )
    (comp (ref "R2")
      (value "680k")
      (footprint "eagle-import:R0402")
      (libsource (lib "eagle-import") (part "R-EU_R0402"))
    )
    (comp (ref "R3")
      (value "200R")
      (footprint "eagle-import:R0402")
      (libsource (lib "eagle-import") (part "R-EU_R0402"))
    )
    (comp (ref "R4")
      (value "16k")
      (footprint "eagle-import:R0402")
      (libsource (lib "eagle-import") (part "R-EU_R0402"))
    )
    (comp (ref "R5")
      (value "110k")
      (footprint "eagle-import:R0402")
      (libsource (lib "eagle-import") (part "R-EU_R0402"))
    )
    (comp (ref "R6")
      (value "100k")
      (footprint "eagle-import:R0402")
      (libsource (lib "eagle-import") (part "R-EU_R0402"))
    )
    (comp (ref "R7")
      (value "FERIT?")
      (footprint "eagle-import:R2010")
      (libsource (lib "eagle-import") (part "R-EU_R2010"))
    )
    (comp (ref "R8")
      (value "1k")
      (footprint "eagle-import:R0402")
      (libsource (lib "eagle-import") (part "R-EU_R0402"))
    )
    (comp (ref "R9")
      (value "300k")
      (footprint "eagle-import:R0402")
      (libsource (lib "eagle-import") (part "R-EU_R0402"))
    )
    (comp (ref "R10")
      (value "100k")
      (footprint "eagle-import:R0402")
      (libsource (lib "eagle-import") (part "R-EU_R0402"))
    )
    (comp (ref "R11")
      (value "1k")
      (footprint "eagle-import:R0402")
      (libsource (lib "eagle-import") (part "R-EU_R0402"))
    )
    (comp (ref "R12")
      (value "80k6")
      (footprint "eagle-import:R0402")
      (libsource (lib "eagle-import") (part "R-EU_R0402"))
    )
    (comp (ref "X1")
      (value "AK500/2")
      (footprint "eagle-import:AK500_2")
      (libsource (lib "eagle-import") (part "AK500/2"))
    )
    (comp (ref "C55")
      (value "100uF")
      (footprint "eagle-import:B_3528-21R")
      (libsource (lib "eagle-import") (part "CPOL-EUB/3528-21R"))
    )
    (comp (ref "C56")
      (value "100uF")
      (footprint "eagle-import:B_3528-21R")
      (libsource (lib "eagle-import") (part "CPOL-EUB/3528-21R"))
    )
    (comp (ref "C57")
      (value "100uF")
      (footprint "eagle-import:B_3528-21R")
      (libsource (lib "eagle-import") (part "CPOL-EUB/3528-21R"))
    )
    (comp (ref "C58")
      (value "100uF")
      (footprint "eagle-import:B_3528-21R")
      (libsource (lib "eagle-import") (part "CPOL-EUB/3528-21R"))
    )
    (comp (ref "C59")
      (value "1uF")
      (footprint "eagle-import:C0805")
      (libsource (lib "eagle-import") (part "C-EUC0805"))
    )
    (comp (ref "C60")
      (value "100nF")
      (footprint "eagle-import:C0402")
      (libsource (lib "eagle-import") (part "C-EUC0402"))
    )
    (comp (ref "C61")
      (value "33pF")
      (footprint "eagle-import:C0402")
      (libsource (lib "eagle-import") (part "C-EUC0402"))
    )
    (comp (ref "C62")
      (value "10pF")
      (footprint "eagle-import:C0402")
      (libsource (lib "eagle-import") (part "C-EUC0402"))
    )
    (comp (ref "C63")
      (value "22pF")
      (footprint "eagle-import:C0402")
      (libsource (lib "eagle-import") (part "C-EUC0402"))
    )
    (comp (ref "C64")
      (value "22pF")
      (footprint "eagle-import:C0402")
      (libsource (lib "eagle-import") (part "C-EUC0402"))
    )
    (comp (ref "C65")
      (value "22pF")
      (footprint "eagle-import:C0402")
      (libsource (lib "eagle-import") (part "C-EUC0402"))
    )
    (comp (ref "C66")
      (value "33pF")
      (footprint "eagle-import:C0402")
      (libsource (lib "eagle-import") (part "C-EUC0402"))
    )
    (comp (ref "C67")
      (value "100nF")
      (footprint "eagle-import:C0402")
      (libsource (lib "eagle-import") (part "C-EUC0402"))
    )
    (comp (ref "C68")
      (value "100nF")
      (footprint "eagle-import:C0402")
      (libsource (lib "eagle-import") (part "C-EUC0402"))
    )
    (comp (ref "C69")
      (value "100nF")
      (footprint "eagle-import:C0402")
      (libsource (lib "eagle-import") (part "C-EUC0402"))
    )
    (comp (ref "C70")
      (value "2.2uF")
      (footprint "eagle-import:C0402")
      (libsource (lib "eagle-import") (part "C-EUC0402"))
    )
    (comp (ref "C71")
      (value "100nF")
      (footprint "eagle-import:C0402")
      (libsource (lib "eagle-import") (part "C-EUC0402"))
    )
    (comp (ref "C72")
      (value "DNF")
      (footprint "eagle-import:C0402")
      (libsource (lib "eagle-import") (part "C-EUC0402"))
    )
    (comp (ref "C73")
      (value "DNF")
      (footprint "eagle-import:C0402")
      (libsource (lib "eagle-import") (part "C-EUC0402"))
    )
    (comp (ref "C74")
      (value "4.7uF")
      (footprint "eagle-import:C0402")
      (libsource (lib "eagle-import") (part "C-EUC0402"))
    )
    (comp (ref "C75")
      (value "2.2uF")
      (footprint "eagle-import:C0402")
      (libsource (lib "eagle-import") (part "C-EUC0402"))
    )
    (comp (ref "C76")
      (value "100nF")
      (footprint "eagle-import:C0402")
      (libsource (lib "eagle-import") (part "C-EUC0402"))
    )
    (comp (ref "FL1")
      (value "TPD3F303DPVR")
      (footprint "eagle-import:SON50P160X210X65-9N")
      (fields (field (name "MOUSER_PART_NUMBER") "595-TPD3F303DPVR"))
      (libsource (lib "eagle-import") (part "TPD3F303DPVR"))
    )
    (comp (ref "IC11")
      (value "TXB0104DR")
      (footprint "eagle-import:SOIC127P600X175-14N")
      (fields (field (name "MOUSER_PART_NUMBER") "595-TXB0104DR"))
      (libsource (lib "eagle-import") (part "TXB0104DR"))
    )
    (comp (ref "IC12")
      (value "A7670E")
      (footprint "eagle-import:A7670CLNSC")
      (fields (field (name "MANUFACTURER_PART_NUMBER") "A7670C-LNSC"))
      (libsource (lib "eagle-import") (part "A7670C-LNSC"))
    )
    (comp (ref "IC13")
      (value "TXB0104DR")
      (footprint "eagle-import:SOIC127P600X175-14N")
      (fields (field (name "MOUSER_PART_NUMBER") "595-TXB0104DR"))
      (libsource (lib "eagle-import") (part "TXB0104DR"))
    )
    (comp (ref "IC14")
      (value "USBLC6-2")
      (footprint "eagle-import:SOT23-6")
      (libsource (lib "eagle-import") (part "USBLC6-2"))
    )
    (comp (ref "J2")
      (value "693043020611")
      (footprint "eagle-import:693043020611")
      (fields (field (name "MOUSER_PART_NUMBER") "710-693043020611"))
      (libsource (lib "eagle-import") (part "693043020611"))
    )
    (comp (ref "J3")
      (value "U.FL-R-SMT_01_")
      (footprint "eagle-import:UFLRSMT01")
      (fields
        (field (name "MANUFACTURER_PART_NUMBER") "U.FL-R-SMT(01)")
        (field (name "MOUSER_PART_NUMBER") "798-U.FL-R-SMT01")
      )
      (libsource (lib "eagle-import") (part "U.FL-R-SMT_01_"))
    )
    (comp (ref "L6")
      (value "ferit")
      (footprint "eagle-import:0402")
      (libsource (lib "eagle-import") (part "BLM15HB121SN1"))
    )
    (comp (ref "Q5")
      (value "BC817-40")
      (footprint "eagle-import:SOT23-BEC")
      (libsource (lib "eagle-import") (part "BC817SMD-16LT1"))
    )
    (comp (ref "Q6")
      (value "BC817-40")
      (footprint "eagle-import:SOT23-BEC")
      (libsource (lib "eagle-import") (part "BC817SMD-16LT1"))
    )
    (comp (ref "R42")
      (value "4k7")
      (footprint "eagle-import:R0402")
      (libsource (lib "eagle-import") (part "R-EU_R0402"))
    )
    (comp (ref "R43")
      (value "10k")
      (footprint "eagle-import:R0402")
      (libsource (lib "eagle-import") (part "R-EU_R0402"))
    )
    (comp (ref "R44")
      (value "4k7")
      (footprint "eagle-import:R0402")
      (libsource (lib "eagle-import") (part "R-EU_R0402"))
    )
    (comp (ref "R45")
      (value "47k")
      (footprint "eagle-import:R0402")
      (libsource (lib "eagle-import") (part "R-EU_R0402"))
    )
    (comp (ref "R46")
      (value "47k")
      (footprint "eagle-import:R0402")
      (libsource (lib "eagle-import") (part "R-EU_R0402"))
    )
    (comp (ref "R47")
      (value "22R")
      (footprint "eagle-import:R0402")
      (libsource (lib "eagle-import") (part "R-EU_R0402"))
    )
    (comp (ref "R48")
      (value "22R")
      (footprint "eagle-import:R0402")
      (libsource (lib "eagle-import") (part "R-EU_R0402"))
    )
    (comp (ref "R49")
      (value "22R")
      (footprint "eagle-import:R0402")
      (libsource (lib "eagle-import") (part "R-EU_R0402"))
    )
    (comp (ref "R50")
      (value "10k")
      (footprint "eagle-import:R0402")
      (libsource (lib "eagle-import") (part "R-EU_R0402"))
    )
    (comp (ref "R51")
      (value "0R")
      (footprint "eagle-import:R0402")
      (libsource (lib "eagle-import") (part "R-EU_R0402"))
    )
    (comp (ref "R52")
      (value "0R")
      (footprint "eagle-import:R0402")
      (libsource (lib "eagle-import") (part "R-EU_R0402"))
    )
    (comp (ref "R53")
      (value "4k7")
      (footprint "eagle-import:R0402")
      (libsource (lib "eagle-import") (part "R-EU_R0402"))
    )
    (comp (ref "R54")
      (value "10k")
      (footprint "eagle-import:R0402")
      (libsource (lib "eagle-import") (part "R-EU_R0402"))
    )
    (comp (ref "RV1")
      (value "CG0402MLU-3.3G")
      (footprint "eagle-import:VARC1005X41N")
      (fields (field (name "MOUSER_PART_NUMBER") "652-CG0402MLU-3.3G"))
      (libsource (lib "eagle-import") (part "CG0402MLU-3.3G"))
    )
    (comp (ref "SJ1") (value "SJ") (footprint "eagle-import:SJ") (libsource (lib "eagle-import") (part "SJ")))
    (comp (ref "TP1")
      (value "TPB1,27")
      (footprint "eagle-import:B1,27")
      (libsource (lib "eagle-import") (part "TPB1,27"))
    )
    (comp (ref "TP2")
      (value "TPB1,27")
      (footprint "eagle-import:B1,27")
      (libsource (lib "eagle-import") (part "TPB1,27"))
    )
    (comp (ref "TP3")
      (value "TPB1,27")
      (footprint "eagle-import:B1,27")
      (libsource (lib "eagle-import") (part "TPB1,27"))
    )
    (comp (ref "TP4")
      (value "TPB1,27")
      (footprint "eagle-import:B1,27")
      (libsource (lib "eagle-import") (part "TPB1,27"))
    )
    (comp (ref "C92")
      (value "100pF")
      (footprint "eagle-import:C0402")
      (libsource (lib "eagle-import") (part "C-EUC0402"))
    )
    (comp (ref "C93")
      (value "100pF")
      (footprint "eagle-import:C0402")
      (libsource (lib "eagle-import") (part "C-EUC0402"))
    )
    (comp (ref "C94")
      (value "100pF")
      (footprint "eagle-import:C0402")
      (libsource (lib "eagle-import") (part "C-EUC0402"))
    )
    (comp (ref "H1")
      (value "MOUNT-HOLE3.2")
      (footprint "eagle-import:3,2")
      (libsource (lib "eagle-import") (part "MOUNT-HOLE3.2"))
    )
    (comp (ref "H2")
      (value "MOUNT-HOLE3.2")
      (footprint "eagle-import:3,2")
      (libsource (lib "eagle-import") (part "MOUNT-HOLE3.2"))
    )
    (comp (ref "H3")
      (value "MOUNT-HOLE3.2")
      (footprint "eagle-import:3,2")
      (libsource (lib "eagle-import") (part "MOUNT-HOLE3.2"))
    )
    (comp (ref "J5")
      (value "44144-0004")
      (footprint "eagle-import:441440004")
      (fields (field (name "MOUSER_PART_NUMBER") "538-44144-0004"))
      (libsource (lib "eagle-import") (part "44144-0004"))
    )
    (comp (ref "J6")
      (value "JST-XH-4")
      (footprint "eagle-import:B4B-XH-A")
      (fields (field (name "MF") "JST") (field (name "MPN") "B4B-XH-A"))
      (libsource (lib "eagle-import") (part "JST-XH-4"))
    )
    (comp (ref "J7")
      (value "44144-0004")
      (footprint "eagle-import:441440004")
      (fields (field (name "MOUSER_PART_NUMBER") "538-44144-0004"))
      (libsource (lib "eagle-import") (part "44144-0004"))
    )
    (comp (ref "J8")
      (value "JST-XH-8")
      (footprint "eagle-import:B8B-XH-A")
      (fields (field (name "MF") "JST") (field (name "MPN") "B8B-XH-A"))
      (libsource (lib "eagle-import") (part "JST-XH-8"))
    )
    (comp (ref "J9")
      (value "M20-8750342")
      (footprint "eagle-import:M208750342")
      (fields (field (name "MOUSER_PART_NUMBER") "855-M20-8750342"))
      (libsource (lib "eagle-import") (part "M20-8750342"))
    )
    (comp (ref "J10")
      (value "M20-8750742")
      (footprint "eagle-import:M208750742")
      (fields (field (name "MOUSER_PART_NUMBER") "855-M20-8750742"))
      (libsource (lib "eagle-import") (part "M20-8750742"))
    )
    (comp (ref "J11")
      (value "JST-XH-8")
      (footprint "eagle-import:B8B-XH-A")
      (fields (field (name "MF") "JST") (field (name "MPN") "B8B-XH-A"))
      (libsource (lib "eagle-import") (part "JST-XH-8"))
    )
    (comp (ref "Q8")
      (value "NTR0202PLT1G")
      (footprint "eagle-import:SOT23")
      (libsource (lib "eagle-import") (part "BSS84"))
    )
    (comp (ref "Q9")
      (value "BSS123")
      (footprint "eagle-import:SOT23")
      (libsource (lib "eagle-import") (part "BSS123"))
    )
    (comp (ref "Q10")
      (value "NTR0202PLT1G")
      (footprint "eagle-import:SOT23")
      (libsource (lib "eagle-import") (part "BSS84"))
    )
    (comp (ref "Q11")
      (value "BSS123")
      (footprint "eagle-import:SOT23")
      (libsource (lib "eagle-import") (part "BSS123"))
    )
    (comp (ref "Q12")
      (value "NTR0202PLT1G")
      (footprint "eagle-import:SOT23")
      (libsource (lib "eagle-import") (part "BSS84"))
    )
    (comp (ref "Q13")
      (value "BSS123")
      (footprint "eagle-import:SOT23")
      (libsource (lib "eagle-import") (part "BSS123"))
    )
    (comp (ref "Q14")
      (value "NTR0202PLT1G")
      (footprint "eagle-import:SOT23")
      (libsource (lib "eagle-import") (part "BSS84"))
    )
    (comp (ref "Q15")
      (value "BSS123")
      (footprint "eagle-import:SOT23")
      (libsource (lib "eagle-import") (part "BSS123"))
    )
    (comp (ref "R86")
      (value "33k")
      (footprint "eagle-import:R0402")
      (libsource (lib "eagle-import") (part "R-EU_R0402"))
    )
    (comp (ref "R87")
      (value "100k")
      (footprint "eagle-import:R0402")
      (libsource (lib "eagle-import") (part "R-EU_R0402"))
    )
    (comp (ref "R88")
      (value "10k")
      (footprint "eagle-import:R0402")
      (libsource (lib "eagle-import") (part "R-EU_R0402"))
    )
    (comp (ref "R89")
      (value "4k7")
      (footprint "eagle-import:R0402")
      (libsource (lib "eagle-import") (part "R-EU_R0402"))
    )
    (comp (ref "R90")
      (value "4k7")
      (footprint "eagle-import:R0402")
      (libsource (lib "eagle-import") (part "R-EU_R0402"))
    )
    (comp (ref "R91")
      (value "100k")
      (footprint "eagle-import:R0402")
      (libsource (lib "eagle-import") (part "R-EU_R0402"))
    )
    (comp (ref "R92")
      (value "1k")
      (footprint "eagle-import:R0402")
      (libsource (lib "eagle-import") (part "R-EU_R0402"))
    )
    (comp (ref "R93")
      (value "10k")
      (footprint "eagle-import:R0402")
      (libsource (lib "eagle-import") (part "R-EU_R0402"))
    )
    (comp (ref "R94")
      (value "1k")
      (footprint "eagle-import:R0402")
      (libsource (lib "eagle-import") (part "R-EU_R0402"))
    )
    (comp (ref "R95")
      (value "1k")
      (footprint "eagle-import:R0402")
      (libsource (lib "eagle-import") (part "R-EU_R0402"))
    )
    (comp (ref "R96")
      (value "100k")
      (footprint "eagle-import:R0402")
      (libsource (lib "eagle-import") (part "R-EU_R0402"))
    )
    (comp (ref "R97")
      (value "100k")
      (footprint "eagle-import:R0402")
      (libsource (lib "eagle-import") (part "R-EU_R0402"))
    )
    (comp (ref "R98")
      (value "1k")
      (footprint "eagle-import:R0402")
      (libsource (lib "eagle-import") (part "R-EU_R0402"))
    )
    (comp (ref "R99")
      (value "1k")
      (footprint "eagle-import:R0402")
      (libsource (lib "eagle-import") (part "R-EU_R0402"))
    )
    (comp (ref "R100")
      (value "1k")
      (footprint "eagle-import:R0402")
      (libsource (lib "eagle-import") (part "R-EU_R0402"))
    )
    (comp (ref "R101")
      (value "10k")
      (footprint "eagle-import:R0402")
      (libsource (lib "eagle-import") (part "R-EU_R0402"))
    )
    (comp (ref "R102")
      (value "100k")
      (footprint "eagle-import:R0402")
      (libsource (lib "eagle-import") (part "R-EU_R0402"))
    )
    (comp (ref "R103")
      (value "1k")
      (footprint "eagle-import:R0402")
      (libsource (lib "eagle-import") (part "R-EU_R0402"))
    )
    (comp (ref "R104")
      (value "10k")
      (footprint "eagle-import:R0402")
      (libsource (lib "eagle-import") (part "R-EU_R0402"))
    )
    (comp (ref "R105")
      (value "4k7")
      (footprint "eagle-import:R0402")
      (libsource (lib "eagle-import") (part "R-EU_R0402"))
    )
    (comp (ref "R106")
      (value "4k7")
      (footprint "eagle-import:R0402")
      (libsource (lib "eagle-import") (part "R-EU_R0402"))
    )
    (comp (ref "R107")
      (value "100k")
      (footprint "eagle-import:R0402")
      (libsource (lib "eagle-import") (part "R-EU_R0402"))
    )
    (comp (ref "R108")
      (value "1k")
      (footprint "eagle-import:R0402")
      (libsource (lib "eagle-import") (part "R-EU_R0402"))
    )
    (comp (ref "C83")
      (value "1uF")
      (footprint "eagle-import:C0402")
      (libsource (lib "eagle-import") (part "C-EUC0402"))
    )
    (comp (ref "C84")
      (value "100nF")
      (footprint "eagle-import:C0402")
      (libsource (lib "eagle-import") (part "C-EUC0402"))
    )
    (comp (ref "C85")
      (value "100nF")
      (footprint "eagle-import:C0402")
      (libsource (lib "eagle-import") (part "C-EUC0402"))
    )
    (comp (ref "C86")
      (value "22nF")
      (footprint "eagle-import:C0402")
      (libsource (lib "eagle-import") (part "C-EUC0402"))
    )
    (comp (ref "C87")
      (value "470pF")
      (footprint "eagle-import:C0402")
      (libsource (lib "eagle-import") (part "C-EUC0402"))
    )
    (comp (ref "C88")
      (value "1uF")
      (footprint "eagle-import:C0402")
      (libsource (lib "eagle-import") (part "C-EUC0402"))
    )
    (comp (ref "C89")
      (value "1uF")
      (footprint "eagle-import:C0402")
      (libsource (lib "eagle-import") (part "C-EUC0402"))
    )
    (comp (ref "C90")
      (value "100nF")
      (footprint "eagle-import:C0402")
      (libsource (lib "eagle-import") (part "C-EUC0402"))
    )
    (comp (ref "C91")
      (value "100nF")
      (footprint "eagle-import:C0402")
      (libsource (lib "eagle-import") (part "C-EUC0402"))
    )
    (comp (ref "IC16")
      (value "LAN8720")
      (footprint "eagle-import:QFN24")
      (libsource (lib "eagle-import") (part "LAN8720"))
    )
    (comp (ref "J4")
      (value "J3011G21DNL")
      (footprint "eagle-import:J3011G21DNL")
      (fields (field (name "MOUSER_PART_NUMBER") "673-J3011G21DNL"))
      (libsource (lib "eagle-import") (part "J3011G21DNL"))
    )
    (comp (ref "L7")
      (value "fcm1608-0603")
      (footprint "eagle-import:L2012C")
      (libsource (lib "eagle-import") (part "L-USL2012C"))
    )
    (comp (ref "Q7")
      (value "ASE-25.000MHZ-LR-T")
      (footprint "eagle-import:CRYSTAL3.2X2.5")
      (libsource (lib "eagle-import") (part "CRYSTAL2.5X2CRYSTAL3.2X2.5"))
    )
    (comp (ref "R61")
      (value "49R9")
      (footprint "eagle-import:R0402")
      (libsource (lib "eagle-import") (part "R-EU_R0402"))
    )
    (comp (ref "R62")
      (value "49R9")
      (footprint "eagle-import:R0402")
      (libsource (lib "eagle-import") (part "R-EU_R0402"))
    )
    (comp (ref "R63")
      (value "49R9")
      (footprint "eagle-import:R0402")
      (libsource (lib "eagle-import") (part "R-EU_R0402"))
    )
    (comp (ref "R64")
      (value "49R9")
      (footprint "eagle-import:R0402")
      (libsource (lib "eagle-import") (part "R-EU_R0402"))
    )
    (comp (ref "R65")
      (value "1k5")
      (footprint "eagle-import:R0402")
      (libsource (lib "eagle-import") (part "R-EU_R0402"))
    )
    (comp (ref "R66")
      (value "4k7")
      (footprint "eagle-import:R0402")
      (libsource (lib "eagle-import") (part "R-EU_R0402"))
    )
    (comp (ref "R67")
      (value "4k7")
      (footprint "eagle-import:R0402")
      (libsource (lib "eagle-import") (part "R-EU_R0402"))
    )
    (comp (ref "R68")
      (value "4k7")
      (footprint "eagle-import:R0402")
      (libsource (lib "eagle-import") (part "R-EU_R0402"))
    )
    (comp (ref "R69")
      (value "4k7")
      (footprint "eagle-import:R0402")
      (libsource (lib "eagle-import") (part "R-EU_R0402"))
    )
    (comp (ref "R70")
      (value "4k7")
      (footprint "eagle-import:R0402")
      (libsource (lib "eagle-import") (part "R-EU_R0402"))
    )
    (comp (ref "R71")
      (value "22R")
      (footprint "eagle-import:R0402")
      (libsource (lib "eagle-import") (part "R-EU_R0402"))
    )
    (comp (ref "R72")
      (value "22R")
      (footprint "eagle-import:R0402")
      (libsource (lib "eagle-import") (part "R-EU_R0402"))
    )
    (comp (ref "R73")
      (value "22R")
      (footprint "eagle-import:R0402")
      (libsource (lib "eagle-import") (part "R-EU_R0402"))
    )
    (comp (ref "R74")
      (value "22R")
      (footprint "eagle-import:R0402")
      (libsource (lib "eagle-import") (part "R-EU_R0402"))
    )
    (comp (ref "R75")
      (value "22R")
      (footprint "eagle-import:R0402")
      (libsource (lib "eagle-import") (part "R-EU_R0402"))
    )
    (comp (ref "R76")
      (value "22R")
      (footprint "eagle-import:R0402")
      (libsource (lib "eagle-import") (part "R-EU_R0402"))
    )
    (comp (ref "R77")
      (value "22R")
      (footprint "eagle-import:R0402")
      (libsource (lib "eagle-import") (part "R-EU_R0402"))
    )
    (comp (ref "R78")
      (value "22R")
      (footprint "eagle-import:R0402")
      (libsource (lib "eagle-import") (part "R-EU_R0402"))
    )
    (comp (ref "R79")
      (value "4k7")
      (footprint "eagle-import:R0402")
      (libsource (lib "eagle-import") (part "R-EU_R0402"))
    )
    (comp (ref "R80")
      (value "12k1")
      (footprint "eagle-import:R0402")
      (libsource (lib "eagle-import") (part "R-EU_R0402"))
    )
    (comp (ref "R81")
      (value "270R")
      (footprint "eagle-import:R0402")
      (libsource (lib "eagle-import") (part "R-EU_R0402"))
    )
    (comp (ref "R82")
      (value "270R")
      (footprint "eagle-import:R0402")
      (libsource (lib "eagle-import") (part "R-EU_R0402"))
    )
    (comp (ref "R83")
      (value "10k")
      (footprint "eagle-import:R0402")
      (libsource (lib "eagle-import") (part "R-EU_R0402"))
    )
    (comp (ref "R84")
      (value "10k")
      (footprint "eagle-import:R0402")
      (libsource (lib "eagle-import") (part "R-EU_R0402"))
    )
    (comp (ref "R85")
      (value "0R")
      (footprint "eagle-import:R0402")
      (libsource (lib "eagle-import") (part "R-EU_R0402"))
    )
    (comp (ref "C95")
      (value "100nF")
      (footprint "eagle-import:C0402")
      (libsource (lib "eagle-import") (part "C-EUC0402"))
    )
    (comp (ref "C96")
      (value "20pF")
      (footprint "eagle-import:C0402")
      (libsource (lib "eagle-import") (part "C-EUC0402"))
    )
    (comp (ref "C97")
      (value "20pF")
      (footprint "eagle-import:C0402")
      (libsource (lib "eagle-import") (part "C-EUC0402"))
    )
    (comp (ref "C98")
      (value "4p7")
      (footprint "eagle-import:C0402")
      (libsource (lib "eagle-import") (part "C-EUC0402"))
    )
    (comp (ref "C99")
      (value "4p7")
      (footprint "eagle-import:C0402")
      (libsource (lib "eagle-import") (part "C-EUC0402"))
    )
    (comp (ref "C100")
      (value "4.7uF")
      (footprint "eagle-import:C0402")
      (libsource (lib "eagle-import") (part "C-EUC0402"))
    )
    (comp (ref "C101")
      (value "10nF")
      (footprint "eagle-import:C0402")
      (libsource (lib "eagle-import") (part "C-EUC0402"))
    )
    (comp (ref "IC17")
      (value "USBLC6-2")
      (footprint "eagle-import:SOT23-6")
      (libsource (lib "eagle-import") (part "USBLC6-2"))
    )
    (comp (ref "J12")
      (value "62910416121")
      (footprint "eagle-import:62910416121")
      (fields (field (name "MOUSER_PART_NUMBER") "710-62910416121"))
      (libsource (lib "eagle-import") (part "62910416121"))
    )
    (comp (ref "JP2")
      (value "JP2Q")
      (footprint "eagle-import:JP2Q")
      (libsource (lib "eagle-import") (part "JP2Q"))
    )
    (comp (ref "L8")
      (value "ferit")
      (footprint "eagle-import:0402")
      (libsource (lib "eagle-import") (part "BLM15HB121SN1"))
    )
    (comp (ref "LED2")
      (value "LEDCHIP-LED0805")
      (footprint "eagle-import:CHIP-LED0805")
      (libsource (lib "eagle-import") (part "LEDCHIP-LED0805"))
    )
    (comp (ref "Q16")
      (value "8MHz")
      (footprint "eagle-import:CRYSTAL3.2X2.5")
      (libsource (lib "eagle-import") (part "CRYSTAL3.2X2.5"))
    )
    (comp (ref "Q17")
      (value "32.768kHz")
      (footprint "eagle-import:NX3215SA32768KEXS00AMU00003")
      (fields
        (field (name "MANUFACTURER_PART_NUMBER") "NX3215SA-32.768K-EXS00A-MU00003")
        (field (name "MOUSER_PART_NUMBER") "344-NX3215SA32.768K3")
      )
      (libsource (lib "eagle-import") (part "NX3215SA-32.768K-EXS00A-MU0000"))
    )
    (comp (ref "R109")
      (value "100k")
      (footprint "eagle-import:R0402")
      (libsource (lib "eagle-import") (part "R-EU_R0402"))
    )
    (comp (ref "R110")
      (value "10k")
      (footprint "eagle-import:R0402")
      (libsource (lib "eagle-import") (part "R-EU_R0402"))
    )
    (comp (ref "R111")
      (value "4k7")
      (footprint "eagle-import:R0402")
      (libsource (lib "eagle-import") (part "R-EU_R0402"))
    )
    (comp (ref "R112")
      (value "10k")
      (footprint "eagle-import:R0402")
      (libsource (lib "eagle-import") (part "R-EU_R0402"))
    )
    (comp (ref "R113")
      (value "0R")
      (footprint "eagle-import:R0402")
      (libsource (lib "eagle-import") (part "R-EU_R0402"))
    )
    (comp (ref "R114")
      (value "100k")
      (footprint "eagle-import:R0402")
      (libsource (lib "eagle-import") (part "R-EU_R0402"))
    )
    (comp (ref "R115")
      (value "10k")
      (footprint "eagle-import:R0402")
      (libsource (lib "eagle-import") (part "R-EU_R0402"))
    )
    (comp (ref "R116")
      (value "47k")
      (footprint "eagle-import:R0402")
      (libsource (lib "eagle-import") (part "R-EU_R0402"))
    )
    (comp (ref "R117")
      (value "1k")
      (footprint "eagle-import:R0402")
      (libsource (lib "eagle-import") (part "R-EU_R0402"))
    )
    (comp (ref "S3")
      (value "10-XX")
      (footprint "eagle-import:B3F-10XX")
      (fields (field (name "MPN") "B3F-1000"))
      (libsource (lib "eagle-import") (part "10-XX"))
    )
  )
  (nets
    (net (code "1") (name "+3V3") (class "Default")
      (node (ref "C21") (pin "1") (pinfunction "1_1") (pintype "passive"))
      (node (ref "C22") (pin "1") (pinfunction "1_1") (pintype "passive"))
      (node (ref "C23") (pin "1") (pinfunction "1_1") (pintype "passive"))
      (node (ref "C24") (pin "1") (pinfunction "1_1") (pintype "passive"))
      (node (ref "C25") (pin "1") (pinfunction "1_1") (pintype "passive"))
      (node (ref "C26") (pin "1") (pinfunction "1_1") (pintype "passive"))
      (node (ref "C27") (pin "1") (pinfunction "1_1") (pintype "passive"))
      (node (ref "C28") (pin "1") (pinfunction "1_1") (pintype "passive"))
      (node (ref "C29") (pin "1") (pinfunction "1_1") (pintype "passive"))
      (node (ref "C30") (pin "1") (pinfunction "1_1") (pintype "passive"))
      (node (ref "C31") (pin "1") (pinfunction "1_1") (pintype "passive"))
      (node (ref "C32") (pin "1") (pinfunction "1_1") (pintype "passive"))
      (node (ref "C33") (pin "1") (pinfunction "1_1") (pintype "passive"))
      (node (ref "C38") (pin "1") (pinfunction "1_1") (pintype "passive"))
      (node (ref "C39") (pin "1") (pinfunction "1_1") (pintype "passive"))
      (node (ref "C40") (pin "1") (pinfunction "1_1") (pintype "passive"))
      (node (ref "C41") (pin "1") (pinfunction "1_1") (pintype "passive"))
      (node (ref "C42") (pin "1") (pinfunction "1_1") (pintype "passive"))
      (node (ref "C43") (pin "1") (pinfunction "1_1") (pintype "passive"))
      (node (ref "C44") (pin "1") (pinfunction "1_1") (pintype "passive"))
      (node (ref "C45") (pin "1") (pinfunction "1_1") (pintype "passive"))
      (node (ref "C46") (pin "1") (pinfunction "1_1") (pintype "passive"))
      (node (ref "C47") (pin "1") (pinfunction "1_1") (pintype "passive"))
      (node (ref "C52") (pin "1") (pinfunction "1_1") (pintype "passive"))
      (node (ref "C53") (pin "1") (pinfunction "1_1") (pintype "passive"))
      (node (ref "C70") (pin "1") (pinfunction "1_1") (pintype "passive"))
      (node (ref "C71") (pin "1") (pinfunction "1_1") (pintype "passive"))
      (node (ref "C75") (pin "1") (pinfunction "1_1") (pintype "passive"))
      (node (ref "C76") (pin "1") (pinfunction "1_1") (pintype "passive"))
      (node (ref "C79") (pin "+") (pinfunction "+_+") (pintype "passive"))
      (node (ref "C80") (pin "+") (pinfunction "+_+") (pintype "passive"))
      (node (ref "C81") (pin "1") (pinfunction "1_1") (pintype "passive"))
      (node (ref "C82") (pin "1") (pinfunction "1_1") (pintype "passive"))
      (node (ref "C89") (pin "1") (pinfunction "1_1") (pintype "passive"))
      (node (ref "C90") (pin "1") (pinfunction "1_1") (pintype "passive"))
      (node (ref "C91") (pin "1") (pinfunction "1_1") (pintype "passive"))
      (node (ref "IC10") (pin "1") (pinfunction "VIN_1") (pintype "bidirectional"))
      (node (ref "IC11") (pin "14") (pinfunction "VCCB_14") (pintype "bidirectional"))
      (node (ref "IC13") (pin "14") (pinfunction "VCCB_14") (pintype "bidirectional"))
      (node (ref "IC15") (pin "2") (pinfunction "3V3_2") (pintype "bidirectional"))
      (node (ref "IC16") (pin "9") (pinfunction "VDDIO_9") (pintype "bidirectional"))
      (node (ref "IC5") (pin "5") (pinfunction "VOUT_5") (pintype "bidirectional"))
      (node (ref "IC6") (pin "108") (pinfunction "VDD_108") (pintype "power_in"))
      (node (ref "IC6") (pin "121") (pinfunction "VDD_121") (pintype "power_in"))
      (node (ref "IC6") (pin "131") (pinfunction "VDD_131") (pintype "power_in"))
      (node (ref "IC6") (pin "144") (pinfunction "VDD_144") (pintype "power_in"))
      (node (ref "IC6") (pin "17") (pinfunction "VDD_17") (pintype "power_in"))
      (node (ref "IC6") (pin "30") (pinfunction "VDD_30") (pintype "power_in"))
      (node (ref "IC6") (pin "39") (pinfunction "VDD_39") (pintype "power_in"))
      (node (ref "IC6") (pin "52") (pinfunction "VDD_52") (pintype "power_in"))
      (node (ref "IC6") (pin "6") (pinfunction "VBAT_6") (pintype "power_in"))
      (node (ref "IC6") (pin "62") (pinfunction "VDD_62") (pintype "power_in"))
      (node (ref "IC6") (pin "72") (pinfunction "VDD_72") (pintype "power_in"))
      (node (ref "IC6") (pin "84") (pinfunction "VDD_84") (pintype "power_in"))
      (node (ref "IC6") (pin "95") (pinfunction "VDD33USB_95") (pintype "power_in"))
      (node (ref "IC7") (pin "8") (pinfunction "VDD_8") (pintype "power_in"))
      (node (ref "IC8") (pin "1") (pinfunction "VIN_1") (pintype "bidirectional"))
      (node (ref "J10") (pin "14") (pinfunction "14_14") (pintype "bidirectional"))
      (node (ref "J9") (pin "5") (pinfunction "5_5") (pintype "bidirectional"))
      (node (ref "L7") (pin "1") (pinfunction "1_1") (pintype "passive"))
      (node (ref "Q14") (pin "2") (pinfunction "S_2") (pintype "passive"))
      (node (ref "Q3") (pin "2") (pinfunction "S_2") (pintype "passive"))
      (node (ref "Q7") (pin "4") (pinfunction "VCC_4") (pintype "power_in"))
      (node (ref "Q8") (pin "2") (pinfunction "S_2") (pintype "passive"))
      (node (ref "R101") (pin "1") (pinfunction "1_1") (pintype "passive"))
      (node (ref "R104") (pin "1") (pinfunction "1_1") (pintype "passive"))
      (node (ref "R105") (pin "2") (pinfunction "2_2") (pintype "passive"))
      (node (ref "R106") (pin "2") (pinfunction "2_2") (pintype "passive"))
      (node (ref "R109") (pin "2") (pinfunction "2_2") (pintype "passive"))
      (node (ref "R110") (pin "2") (pinfunction "2_2") (pintype "passive"))
      (node (ref "R113") (pin "2") (pinfunction "2_2") (pintype "passive"))
      (node (ref "R13") (pin "2") (pinfunction "2_2") (pintype "passive"))
      (node (ref "R20") (pin "2") (pinfunction "2_2") (pintype "passive"))
      (node (ref "R21") (pin "2") (pinfunction "2_2") (pintype "passive"))
      (node (ref "R26") (pin "2") (pinfunction "2_2") (pintype "passive"))
      (node (ref "R56") (pin "2") (pinfunction "2_2") (pintype "passive"))
      (node (ref "R57") (pin "2") (pinfunction "2_2") (pintype "passive"))
      (node (ref "R58") (pin "2") (pinfunction "2_2") (pintype "passive"))
      (node (ref "R59") (pin "2") (pinfunction "2_2") (pintype "passive"))
      (node (ref "R65") (pin "2") (pinfunction "2_2") (pintype "passive"))
      (node (ref "R66") (pin "2") (pinfunction "2_2") (pintype "passive"))
      (node (ref "R67") (pin "2") (pinfunction "2_2") (pintype "passive"))
      (node (ref "R68") (pin "2") (pinfunction "2_2") (pintype "passive"))
      (node (ref "R69") (pin "2") (pinfunction "2_2") (pintype "passive"))
      (node (ref "R70") (pin "2") (pinfunction "2_2") (pintype "passive"))
      (node (ref "R86") (pin "2") (pinfunction "2_2") (pintype "passive"))
      (node (ref "R87") (pin "2") (pinfunction "2_2") (pintype "passive"))
      (node (ref "R88") (pin "1") (pinfunction "1_1") (pintype "passive"))
      (node (ref "R89") (pin "2") (pinfunction "2_2") (pintype "passive"))
      (node (ref "R90") (pin "2") (pinfunction "2_2") (pintype "passive"))
      (node (ref "R93") (pin "1") (pinfunction "1_1") (pintype "passive"))
      (node (ref "R94") (pin "2") (pinfunction "2_2") (pintype "passive"))
      (node (ref "R95") (pin "2") (pinfunction "2_2") (pintype "passive"))
      (node (ref "R96") (pin "2") (pinfunction "2_2") (pintype "passive"))
    )
    (net (code "2") (name "+4V") (class "Default")
      (node (ref "C19") (pin "1") (pinfunction "1_1") (pintype "passive"))
      (node (ref "C20") (pin "1") (pinfunction "1_1") (pintype "passive"))
      (node (ref "C55") (pin "+") (pinfunction "+_+") (pintype "passive"))
      (node (ref "C56") (pin "+") (pinfunction "+_+") (pintype "passive"))
      (node (ref "C57") (pin "+") (pinfunction "+_+") (pintype "passive"))
      (node (ref "C58") (pin "+") (pinfunction "+_+") (pintype "passive"))
      (node (ref "C59") (pin "1") (pinfunction "1_1") (pintype "passive"))
      (node (ref "C60") (pin "1") (pinfunction "1_1") (pintype "passive"))
      (node (ref "C61") (pin "1") (pinfunction "1_1") (pintype "passive"))
      (node (ref "C62") (pin "1") (pinfunction "1_1") (pintype "passive"))
      (node (ref "IC12") (pin "55") (pinfunction "VBAT_55") (pintype "power_in"))
      (node (ref "IC12") (pin "56") (pinfunction "VBAT_56") (pintype "power_in"))
      (node (ref "IC12") (pin "57") (pinfunction "VBAT_57") (pintype "power_in"))
      (node (ref "IC5") (pin "1") (pinfunction "VIN_1") (pintype "bidirectional"))
      (node (ref "IC5") (pin "3") (pinfunction "CE_3") (pintype "bidirectional"))
      (node (ref "R7") (pin "2") (pinfunction "2_2") (pintype "passive"))
    )
    (net (code "3") (name "+5V") (class "Default")
      (node (ref "C10") (pin "1") (pinfunction "1_1") (pintype "passive"))
      (node (ref "C9") (pin "1") (pinfunction "1_1") (pintype "passive"))
      (node (ref "IC2") (pin "5") (pinfunction "VOUT_5") (pintype "bidirectional"))
      (node (ref "J10") (pin "12") (pinfunction "12_12") (pintype "bidirectional"))
      (node (ref "Q10") (pin "2") (pinfunction "S_2") (pintype "passive"))
      (node (ref "Q12") (pin "2") (pinfunction "S_2") (pintype "passive"))
      (node (ref "R3") (pin "2") (pinfunction "2_2") (pintype "passive"))
      (node (ref "R8") (pin "2") (pinfunction "2_2") (pintype "passive"))
    )
    (net (code "4") (name "+VDDCR") (class "Default")
      (node (ref "C87") (pin "1") (pinfunction "1_1") (pintype "passive"))
      (node (ref "C88") (pin "2") (pinfunction "2_2") (pintype "passive"))
      (node (ref "IC16") (pin "6") (pinfunction "VDDCR_6") (pintype "bidirectional"))
    )
    (net (code "5") (name "ADC2_WIND_DIR") (class "Default")
      (node (ref "C92") (pin "1") (pinfunction "1_1") (pintype "passive"))
      (node (ref "IC6") (pin "37") (pinfunction "PA3_37") (pintype "bidirectional"))
      (node (ref "J5") (pin "1") (pinfunction "1_1") (pintype "bidirectional"))
      (node (ref "R86") (pin "1") (pinfunction "1_1") (pintype "passive"))
    )
    (net (code "6") (name "ADC3_BAT_VOLTAGE") (class "Default")
      (node (ref "C101") (pin "1") (pinfunction "1_1") (pintype "passive"))
      (node (ref "IC6") (pin "14") (pinfunction "PF4_14") (pintype "bidirectional"))
      (node (ref "R114") (pin "1") (pinfunction "1_1") (pintype "passive"))
      (node (ref "R116") (pin "2") (pinfunction "2_2") (pintype "passive"))
    )
    (net (code "7") (name "ANEMOMETER") (class "Default")
      (node (ref "C93") (pin "1") (pinfunction "1_1") (pintype "passive"))
      (node (ref "IC6") (pin "56") (pinfunction "PG0_56") (pintype "bidirectional"))
      (node (ref "J5") (pin "3") (pinfunction "3_3") (pintype "bidirectional"))
      (node (ref "R87") (pin "1") (pinfunction "1_1") (pintype "passive"))
    )
    (net (code "8") (name "CAM_PWDN") (class "Default")
      (node (ref "IC6") (pin "89") (pinfunction "PG4_89") (pintype "bidirectional"))
      (node (ref "R38") (pin "2") (pinfunction "2_2") (pintype "passive"))
    )
    (net (code "9") (name "CAM_PWR_IOVDD_EN") (class "Default")
      (node (ref "IC6") (pin "87") (pinfunction "PG2_87") (pintype "bidirectional"))
      (node (ref "Q4") (pin "1") (pinfunction "G_1") (pintype "passive"))
      (node (ref "R36") (pin "2") (pinfunction "2_2") (pintype "passive"))
    )
    (net (code "10") (name "CAM_RESET") (class "Default")
      (node (ref "IC6") (pin "90") (pinfunction "PG5_90") (pintype "bidirectional"))
      (node (ref "R39") (pin "2") (pinfunction "2_2") (pintype "passive"))
    )
    (net (code "11") (name "DCMI_D0") (class "Default")
      (node (ref "IC6") (pin "96") (pinfunction "PC6_96") (pintype "bidirectional"))
      (node (ref "R22") (pin "2") (pinfunction "2_2") (pintype "passive"))
    )
    (net (code "12") (name "DCMI_D1") (class "Default")
      (node (ref "IC6") (pin "97") (pinfunction "PC7_97") (pintype "bidirectional"))
      (node (ref "R23") (pin "2") (pinfunction "2_2") (pintype "passive"))
    )
    (net (code "13") (name "DCMI_D2") (class "Default")
      (node (ref "IC6") (pin "141") (pinfunction "PE0_141") (pintype "bidirectional"))
      (node (ref "R24") (pin "2") (pinfunction "2_2") (pintype "passive"))
    )
    (net (code "14") (name "DCMI_D3") (class "Default")
      (node (ref "IC6") (pin "142") (pinfunction "PE1_142") (pintype "bidirectional"))
      (node (ref "R25") (pin "2") (pinfunction "2_2") (pintype "passive"))
    )
    (net (code "15") (name "DCMI_D4") (class "Default")
      (node (ref "IC6") (pin "112") (pinfunction "PC11_112") (pintype "bidirectional"))
      (node (ref "R27") (pin "2") (pinfunction "2_2") (pintype "passive"))
    )
    (net (code "16") (name "DCMI_D5") (class "Default")
      (node (ref "IC6") (pin "117") (pinfunction "PD3_117") (pintype "bidirectional"))
      (node (ref "R28") (pin "2") (pinfunction "2_2") (pintype "passive"))
    )
    (net (code "17") (name "DCMI_D6") (class "Default")
      (node (ref "IC6") (pin "139") (pinfunction "PB8_139") (pintype "bidirectional"))
      (node (ref "R29") (pin "2") (pinfunction "2_2") (pintype "passive"))
    )
    (net (code "18") (name "DCMI_D7") (class "Default")
      (node (ref "IC6") (pin "5") (pinfunction "PE6_5") (pintype "bidirectional"))
      (node (ref "R30") (pin "2") (pinfunction "2_2") (pintype "passive"))
    )
    (net (code "19") (name "DCMI_D8") (class "Default")
      (node (ref "IC6") (pin "111") (pinfunction "PC10_111") (pintype "bidirectional"))
      (node (ref "R31") (pin "2") (pinfunction "2_2") (pintype "passive"))
    )
    (net (code "20") (name "DCMI_D9") (class "Default")
      (node (ref "IC6") (pin "113") (pinfunction "PC12_113") (pintype "bidirectional"))
      (node (ref "R32") (pin "2") (pinfunction "2_2") (pintype "passive"))
    )
    (net (code "21") (name "DCMI_HSYNC") (class "Default")
      (node (ref "IC6") (pin "40") (pinfunction "PA4_40") (pintype "bidirectional"))
      (node (ref "R34") (pin "2") (pinfunction "2_2") (pintype "passive"))
    )
    (net (code "22") (name "DCMI_PIXCLK") (class "Default")
      (node (ref "IC6") (pin "42") (pinfunction "PA6_42") (pintype "bidirectional"))
      (node (ref "R33") (pin "2") (pinfunction "2_2") (pintype "passive"))
    )
    (net (code "23") (name "DCMI_VSYNC") (class "Default")
      (node (ref "IC6") (pin "124") (pinfunction "PG9_124") (pintype "bidirectional"))
      (node (ref "R35") (pin "2") (pinfunction "2_2") (pintype "passive"))
    )
    (net (code "24") (name "DEBUG_JTCK-SWCLK") (class "Default")
      (node (ref "IC6") (pin "109") (pinfunction "PA14_109") (pintype "bidirectional"))
      (node (ref "JP2") (pin "4") (pinfunction "4_4") (pintype "passive"))
    )
    (net (code "25") (name "DEBUG_JTMS-SWDIO") (class "Default")
      (node (ref "IC6") (pin "105") (pinfunction "PA13_105") (pintype "bidirectional"))
      (node (ref "JP2") (pin "2") (pinfunction "2_2") (pintype "passive"))
    )
    (net (code "26") (name "ESP32_RESET") (class "Default")
      (node (ref "C77") (pin "1") (pinfunction "1_1") (pintype "passive"))
      (node (ref "IC15") (pin "3") (pinfunction "EN_3") (pintype "bidirectional"))
      (node (ref "IC6") (pin "92") (pinfunction "PG7_92") (pintype "bidirectional"))
      (node (ref "R60") (pin "2") (pinfunction "2_2") (pintype "passive"))
      (node (ref "S1") (pin "1") (pinfunction "S_1") (pintype "passive"))
      (node (ref "S1") (pin "2") (pinfunction "S1_2") (pintype "passive"))
    )
    (net (code "27") (name "ETH_BIAS") (class "Default")
      (node (ref "IC16") (pin "24") (pinfunction "RBIAS_24") (pintype "bidirectional"))
      (node (ref "R80") (pin "1") (pinfunction "1_1") (pintype "passive"))
    )
    (net (code "28") (name "ETH_CRS_DV") (class "Default")
      (node (ref "IC6") (pin "43") (pinfunction "PA7_43") (pintype "bidirectional"))
      (node (ref "R73") (pin "1") (pinfunction "1_1") (pintype "passive"))
    )
    (net (code "29") (name "ETH_LED_ACT") (class "Default")
      (node (ref "IC16") (pin "2") (pinfunction "LED2_2") (pintype "bidirectional"))
      (node (ref "J4") (pin "1") (pinfunction "ANODE_YELLOW_1") (pintype "bidirectional"))
      (node (ref "R83") (pin "2") (pinfunction "2_2") (pintype "passive"))
    )
    (net (code "30") (name "ETH_LED_SPD") (class "Default")
      (node (ref "IC16") (pin "3") (pinfunction "LED1_3") (pintype "bidirectional"))
      (node (ref "J4") (pin "12") (pinfunction "ANODE_GREEN_12") (pintype "bidirectional"))
      (node (ref "R84") (pin "2") (pinfunction "2_2") (pintype "passive"))
    )
    (net (code "31") (name "ETH_MDC") (class "Default")
      (node (ref "IC6") (pin "27") (pinfunction "PC1_27") (pintype "bidirectional"))
      (node (ref "R75") (pin "1") (pinfunction "1_1") (pintype "passive"))
    )
    (net (code "32") (name "ETH_MDIO") (class "Default")
      (node (ref "IC6") (pin "36") (pinfunction "PA2_36") (pintype "bidirectional"))
      (node (ref "R74") (pin "1") (pinfunction "1_1") (pintype "passive"))
    )
    (net (code "33") (name "ETH_REF_CLK") (class "Default")
      (node (ref "IC16") (pin "14") (pinfunction "REFCLKO_14") (pintype "bidirectional"))
      (node (ref "IC6") (pin "35") (pinfunction "PA1_35") (pintype "bidirectional"))
      (node (ref "R66") (pin "1") (pinfunction "1_1") (pintype "passive"))
    )
    (net (code "34") (name "ETH_RST") (class "Default")
      (node (ref "IC16") (pin "15") (pinfunction "~{RST}_15") (pintype "bidirectional"))
      (node (ref "IC6") (pin "47") (pinfunction "PB1_47") (pintype "bidirectional"))
      (node (ref "R70") (pin "1") (pinfunction "1_1") (pintype "passive"))
      (node (ref "R85") (pin "2") (pinfunction "2_2") (pintype "passive"))
    )
    (net (code "35") (name "ETH_RXD0") (class "Default")
      (node (ref "IC6") (pin "44") (pinfunction "PC4_44") (pintype "bidirectional"))
      (node (ref "R71") (pin "1") (pinfunction "1_1") (pintype "passive"))
    )
    (net (code "36") (name "ETH_RXD1") (class "Default")
      (node (ref "IC6") (pin "45") (pinfunction "PC5_45") (pintype "bidirectional"))
      (node (ref "R72") (pin "1") (pinfunction "1_1") (pintype "passive"))
    )
    (net (code "37") (name "ETH_RX_N") (class "Default")
      (node (ref "IC16") (pin "22") (pinfunction "RXN_22") (pintype "bidirectional"))
      (node (ref "J4") (pin "8") (pinfunction "RD-_8") (pintype "bidirectional"))
      (node (ref "R61") (pin "1") (pinfunction "1_1") (pintype "passive"))
    )
    (net (code "38") (name "ETH_RX_P") (class "Default")
      (node (ref "IC16") (pin "23") (pinfunction "RXP_23") (pintype "bidirectional"))
      (node (ref "J4") (pin "7") (pinfunction "RD+_7") (pintype "bidirectional"))
      (node (ref "R62") (pin "1") (pinfunction "1_1") (pintype "passive"))
    )
    (net (code "39") (name "ETH_TXD0") (class "Default")
      (node (ref "IC6") (pin "128") (pinfunction "PG13_128") (pintype "bidirectional"))
      (node (ref "R77") (pin "1") (pinfunction "1_1") (pintype "passive"))
    )
    (net (code "40") (name "ETH_TXD1") (class "Default")
      (node (ref "IC6") (pin "129") (pinfunction "PG14_129") (pintype "bidirectional"))
      (node (ref "R78") (pin "1") (pinfunction "1_1") (pintype "passive"))
    )
    (net (code "41") (name "ETH_TX_EN") (class "Default")
      (node (ref "IC6") (pin "126") (pinfunction "PG11_126") (pintype "bidirectional"))
      (node (ref "R76") (pin "1") (pinfunction "1_1") (pintype "passive"))
    )
    (net (code "42") (name "ETH_TX_N") (class "Default")
      (node (ref "IC16") (pin "20") (pinfunction "TXN_20") (pintype "bidirectional"))
      (node (ref "J4") (pin "4") (pinfunction "TD-_4") (pintype "bidirectional"))
      (node (ref "R63") (pin "1") (pinfunction "1_1") (pintype "passive"))
    )
    (net (code "43") (name "ETH_TX_P") (class "Default")
      (node (ref "IC16") (pin "21") (pinfunction "TXP_21") (pintype "bidirectional"))
      (node (ref "J4") (pin "3") (pinfunction "TD+_3") (pintype "bidirectional"))
      (node (ref "R64") (pin "1") (pinfunction "1_1") (pintype "passive"))
    )
    (net (code "44") (name "ETH_XTAL") (class "Default")
      (node (ref "IC16") (pin "5") (pinfunction "XTAL_IN_5") (pintype "bidirectional"))
      (node (ref "Q7") (pin "3") (pinfunction "OUT_3") (pintype "output"))
    )
    (net (code "45") (name "GAUGE") (class "Default")
      (node (ref "C94") (pin "1") (pinfunction "1_1") (pintype "passive"))
      (node (ref "IC6") (pin "57") (pinfunction "PG1_57") (pintype "bidirectional"))
      (node (ref "J7") (pin "3") (pinfunction "3_3") (pintype "bidirectional"))
      (node (ref "R96") (pin "1") (pinfunction "1_1") (pintype "passive"))
    )
    (net (code "46") (name "GND") (class "Default")
      (node (ref "C1") (pin "-") (pinfunction "-_-") (pintype "passive"))
      (node (ref "C10") (pin "2") (pinfunction "2_2") (pintype "passive"))
      (node (ref "C100") (pin "2") (pinfunction "2_2") (pintype "passive"))
      (node (ref "C101") (pin "2") (pinfunction "2_2") (pintype "passive"))
      (node (ref "C11") (pin "2") (pinfunction "2_2") (pintype "passive"))
      (node (ref "C12") (pin "2") (pinfunction "2_2") (pintype "passive"))
      (node (ref "C15") (pin "2") (pinfunction "2_2") (pintype "passive"))
      (node (ref "C16") (pin "2") (pinfunction "2_2") (pintype "passive"))
      (node (ref "C17") (pin "2") (pinfunction "2_2") (pintype "passive"))
      (node (ref "C18") (pin "-") (pinfunction "-_-") (pintype "passive"))
      (node (ref "C19") (pin "2") (pinfunction "2_2") (pintype "passive"))
      (node (ref "C2") (pin "2") (pinfunction "2_2") (pintype "passive"))
      (node (ref "C20") (pin "2") (pinfunction "2_2") (pintype "passive"))
      (node (ref "C21") (pin "2") (pinfunction "2_2") (pintype "passive"))
      (node (ref "C22") (pin "2") (pinfunction "2_2") (pintype "passive"))
      (node (ref "C23") (pin "2") (pinfunction "2_2") (pintype "passive"))
      (node (ref "C24") (pin "2") (pinfunction "2_2") (pintype "passive"))
      (node (ref "C25") (pin "2") (pinfunction "2_2") (pintype "passive"))
      (node (ref "C26") (pin "2") (pinfunction "2_2") (pintype "passive"))
      (node (ref "C27") (pin "2") (pinfunction "2_2") (pintype "passive"))
      (node (ref "C28") (pin "2") (pinfunction "2_2") (pintype "passive"))
      (node (ref "C29") (pin "2") (pinfunction "2_2") (pintype "passive"))
      (node (ref "C3") (pin "2") (pinfunction "2_2") (pintype "passive"))
      (node (ref "C30") (pin "2") (pinfunction "2_2") (pintype "passive"))
      (node (ref "C31") (pin "2") (pinfunction "2_2") (pintype "passive"))
      (node (ref "C32") (pin "2") (pinfunction "2_2") (pintype "passive"))
      (node (ref "C33") (pin "2") (pinfunction "2_2") (pintype "passive"))
      (node (ref "C34") (pin "2") (pinfunction "2_2") (pintype "passive"))
      (node (ref "C35") (pin "2") (pinfunction "2_2") (pintype "passive"))
      (node (ref "C36") (pin "2") (pinfunction "2_2") (pintype "passive"))
      (node (ref "C37") (pin "2") (pinfunction "2_2") (pintype "passive"))
      (node (ref "C38") (pin "2") (pinfunction "2_2") (pintype "passive"))
      (node (ref "C39") (pin "2") (pinfunction "2_2") (pintype "passive"))
      (node (ref "C4") (pin "2") (pinfunction "2_2") (pintype "passive"))
      (node (ref "C40") (pin "2") (pinfunction "2_2") (pintype "passive"))
      (node (ref "C41") (pin "2") (pinfunction "2_2") (pintype "passive"))
      (node (ref "C42") (pin "2") (pinfunction "2_2") (pintype "passive"))
      (node (ref "C43") (pin "2") (pinfunction "2_2") (pintype "passive"))
      (node (ref "C44") (pin "2") (pinfunction "2_2") (pintype "passive"))
      (node (ref "C45") (pin "2") (pinfunction "2_2") (pintype "passive"))
      (node (ref "C46") (pin "2") (pinfunction "2_2") (pintype "passive"))
      (node (ref "C47") (pin "2") (pinfunction "2_2") (pintype "passive"))
      (node (ref "C48") (pin "2") (pinfunction "2_2") (pintype "passive"))
      (node (ref "C49") (pin "2") (pinfunction "2_2") (pintype "passive"))
      (node (ref "C5") (pin "2") (pinfunction "2_2") (pintype "passive"))
      (node (ref "C50") (pin "2") (pinfunction "2_2") (pintype "passive"))
      (node (ref "C51") (pin "2") (pinfunction "2_2") (pintype "passive"))
      (node (ref "C52") (pin "2") (pinfunction "2_2") (pintype "passive"))
      (node (ref "C53") (pin "2") (pinfunction "2_2") (pintype "passive"))
      (node (ref "C54") (pin "2") (pinfunction "2_2") (pintype "passive"))
      (node (ref "C55") (pin "-") (pinfunction "-_-") (pintype "passive"))
      (node (ref "C56") (pin "-") (pinfunction "-_-") (pintype "passive"))
      (node (ref "C57") (pin "-") (pinfunction "-_-") (pintype "passive"))
      (node (ref "C58") (pin "-") (pinfunction "-_-") (pintype "passive"))
      (node (ref "C59") (pin "2") (pinfunction "2_2") (pintype "passive"))
      (node (ref "C6") (pin "-") (pinfunction "-_-") (pintype "passive"))
      (node (ref "C60") (pin "2") (pinfunction "2_2") (pintype "passive"))
      (node (ref "C61") (pin "2") (pinfunction "2_2") (pintype "passive"))
      (node (ref "C62") (pin "2") (pinfunction "2_2") (pintype "passive"))
      (node (ref "C63") (pin "2") (pinfunction "2_2") (pintype "passive"))
      (node (ref "C64") (pin "2") (pinfunction "2_2") (pintype "passive"))
      (node (ref "C65") (pin "2") (pinfunction "2_2") (pintype "passive"))
      (node (ref "C66") (pin "2") (pinfunction "2_2") (pintype "passive"))
      (node (ref "C67") (pin "2") (pinfunction "2_2") (pintype "passive"))
      (node (ref "C68") (pin "2") (pinfunction "2_2") (pintype "passive"))
      (node (ref "C69") (pin "2") (pinfunction "2_2") (pintype "passive"))
      (node (ref "C7") (pin "2") (pinfunction "2_2") (pintype "passive"))
      (node (ref "C70") (pin "2") (pinfunction "2_2") (pintype "passive"))
      (node (ref "C71") (pin "2") (pinfunction "2_2") (pintype "passive"))
      (node (ref "C72") (pin "2") (pinfunction "2_2") (pintype "passive"))
      (node (ref "C73") (pin "2") (pinfunction "2_2") (pintype "passive"))
      (node (ref "C74") (pin "2") (pinfunction "2_2") (pintype "passive"))
      (node (ref "C75") (pin "2") (pinfunction "2_2") (pintype "passive"))
      (node (ref "C76") (pin "2") (pinfunction "2_2") (pintype "passive"))
      (node (ref "C77") (pin "2") (pinfunction "2_2") (pintype "passive"))
      (node (ref "C78") (pin "2") (pinfunction "2_2") (pintype "passive"))
      (node (ref "C79") (pin "-") (pinfunction "-_-") (pintype "passive"))
      (node (ref "C8") (pin "2") (pinfunction "2_2") (pintype "passive"))
      (node (ref "C80") (pin "-") (pinfunction "-_-") (pintype "passive"))
      (node (ref "C81") (pin "2") (pinfunction "2_2") (pintype "passive"))
      (node (ref "C82") (pin "2") (pinfunction "2_2") (pintype "passive"))
      (node (ref "C83") (pin "2") (pinfunction "2_2") (pintype "passive"))
      (node (ref "C84") (pin "2") (pinfunction "2_2") (pintype "passive"))
      (node (ref "C85") (pin "2") (pinfunction "2_2") (pintype "passive"))
      (node (ref "C86") (pin "2") (pinfunction "2_2") (pintype "passive"))
      (node (ref "C87") (pin "2") (pinfunction "2_2") (pintype "passive"))
      (node (ref "C88") (pin "1") (pinfunction "1_1") (pintype "passive"))
      (node (ref "C89") (pin "2") (pinfunction "2_2") (pintype "passive"))
      (node (ref "C9") (pin "2") (pinfunction "2_2") (pintype "passive"))
      (node (ref "C90") (pin "2") (pinfunction "2_2") (pintype "passive"))
      (node (ref "C91") (pin "2") (pinfunction "2_2") (pintype "passive"))
      (node (ref "C92") (pin "2") (pinfunction "2_2") (pintype "passive"))
      (node (ref "C93") (pin "2") (pinfunction "2_2") (pintype "passive"))
      (node (ref "C94") (pin "2") (pinfunction "2_2") (pintype "passive"))
      (node (ref "C95") (pin "2") (pinfunction "2_2") (pintype "passive"))
      (node (ref "C96") (pin "2") (pinfunction "2_2") (pintype "passive"))
      (node (ref "C97") (pin "2") (pinfunction "2_2") (pintype "passive"))
      (node (ref "C98") (pin "2") (pinfunction "2_2") (pintype "passive"))
      (node (ref "C99") (pin "2") (pinfunction "2_2") (pintype "passive"))
      (node (ref "FL1") (pin "9") (pinfunction "EP_(GND)_9") (pintype "bidirectional"))
      (node (ref "IC1") (pin "2") (pinfunction "GND_2") (pintype "bidirectional"))
      (node (ref "IC10") (pin "2") (pinfunction "VSS_2") (pintype "bidirectional"))
      (node (ref "IC11") (pin "7") (pinfunction "GND_7") (pintype "bidirectional"))
      (node (ref "IC11") (pin "8") (pinfunction "OE_8") (pintype "bidirectional"))
      (node (ref "IC12") (pin "17") (pinfunction "GND_17") (pintype "power_in"))
      (node (ref "IC12") (pin "18") (pinfunction "GND_18") (pintype "power_in"))
      (node (ref "IC12") (pin "2") (pinfunction "GND_2") (pintype "power_in"))
      (node (ref "IC12") (pin "29") (pinfunction "GND_29") (pintype "power_in"))
      (node (ref "IC12") (pin "39") (pinfunction "GND_39") (pintype "power_in"))
      (node (ref "IC12") (pin "45") (pinfunction "GND_45") (pintype "power_in"))
      (node (ref "IC12") (pin "46") (pinfunction "GND_46") (pintype "power_in"))
      (node (ref "IC12") (pin "54") (pinfunction "GND_54") (pintype "power_in"))
      (node (ref "IC12") (pin "58") (pinfunction "GND_58") (pintype "power_in"))
      (node (ref "IC12") (pin "59") (pinfunction "GND_59") (pintype "power_in"))
      (node (ref "IC12") (pin "61") (pinfunction "GND_61") (pintype "power_in"))
      (node (ref "IC12") (pin "62") (pinfunction "GND_62") (pintype "power_in"))
      (node (ref "IC12") (pin "63") (pinfunction "GND_63") (pintype "power_in"))
      (node (ref "IC12") (pin "64") (pinfunction "GND_64") (pintype "power_in"))
      (node (ref "IC12") (pin "65") (pinfunction "GND_65") (pintype "power_in"))
      (node (ref "IC12") (pin "69") (pinfunction "GND_69") (pintype "power_in"))
      (node (ref "IC12") (pin "70") (pinfunction "GND_70") (pintype "power_in"))
      (node (ref "IC12") (pin "71") (pinfunction "GND_71") (pintype "power_in"))
      (node (ref "IC12") (pin "72") (pinfunction "GND_72") (pintype "power_in"))
      (node (ref "IC12") (pin "73") (pinfunction "GND_73") (pintype "power_in"))
      (node (ref "IC12") (pin "74") (pinfunction "GND_74") (pintype "power_in"))
      (node (ref "IC12") (pin "75") (pinfunction "GND_75") (pintype "power_in"))
      (node (ref "IC12") (pin "76") (pinfunction "GND_76") (pintype "power_in"))
      (node (ref "IC12") (pin "77") (pinfunction "GND_77") (pintype "power_in"))
      (node (ref "IC12") (pin "78") (pinfunction "GND_78") (pintype "power_in"))
      (node (ref "IC12") (pin "79") (pinfunction "GND_79") (pintype "power_in"))
      (node (ref "IC12") (pin "80") (pinfunction "GND_80") (pintype "power_in"))
      (node (ref "IC12") (pin "81") (pinfunction "GND_81") (pintype "power_in"))
      (node (ref "IC12") (pin "82") (pinfunction "GND_82") (pintype "power_in"))
      (node (ref "IC12") (pin "83") (pinfunction "GND_83") (pintype "power_in"))
      (node (ref "IC12") (pin "84") (pinfunction "GND_84") (pintype "power_in"))
      (node (ref "IC12") (pin "85") (pinfunction "GND_85") (pintype "power_in"))
      (node (ref "IC12") (pin "86") (pinfunction "GND_86") (pintype "power_in"))
      (node (ref "IC12") (pin "87") (pinfunction "GND_87") (pintype "power_in"))
      (node (ref "IC12") (pin "88") (pinfunction "GND_88") (pintype "power_in"))
      (node (ref "IC13") (pin "7") (pinfunction "GND_7") (pintype "bidirectional"))
      (node (ref "IC13") (pin "8") (pinfunction "OE_8") (pintype "bidirectional"))
      (node (ref "IC14") (pin "2") (pinfunction "GND_2") (pintype "power_in"))
      (node (ref "IC15") (pin "1") (pinfunction "GND_1") (pintype "bidirectional"))
      (node (ref "IC15") (pin "40") (pinfunction "GND_40") (pintype "bidirectional"))
      (node (ref "IC15") (pin "41") (pinfunction "GND_41") (pintype "bidirectional"))
      (node (ref "IC15") (pin "42") (pinfunction "GND_42") (pintype "bidirectional"))
      (node (ref "IC15") (pin "43") (pinfunction "GND_43") (pintype "bidirectional"))
      (node (ref "IC15") (pin "44") (pinfunction "GND_44") (pintype "bidirectional"))
      (node (ref "IC15") (pin "45") (pinfunction "GND_45") (pintype "bidirectional"))
      (node (ref "IC15") (pin "46") (pinfunction "GND_46") (pintype "bidirectional"))
      (node (ref "IC15") (pin "47") (pinfunction "GND_47") (pintype "bidirectional"))
      (node (ref "IC15") (pin "48") (pinfunction "GND_48") (pintype "bidirectional"))
      (node (ref "IC15") (pin "49") (pinfunction "GND_49") (pintype "bidirectional"))
      (node (ref "IC16") (pin "EXP") (pinfunction "GND_EXP") (pintype "bidirectional"))
      (node (ref "IC17") (pin "2") (pinfunction "GND_2") (pintype "power_in"))
      (node (ref "IC2") (pin "2") (pinfunction "VSS_2") (pintype "bidirectional"))
      (node (ref "IC3") (pin "1") (pinfunction "A_1") (pintype "passive"))
      (node (ref "IC4") (pin "6") (pinfunction "AGND_6") (pintype "bidirectional"))
      (node (ref "IC4") (pin "8") (pinfunction "PGND_8") (pintype "bidirectional"))
      (node (ref "IC5") (pin "2") (pinfunction "VSS_2") (pintype "bidirectional"))
      (node (ref "IC6") (pin "107") (pinfunction "VSS_107") (pintype "power_in"))
      (node (ref "IC6") (pin "120") (pinfunction "VSS_120") (pintype "power_in"))
      (node (ref "IC6") (pin "130") (pinfunction "VSS_130") (pintype "power_in"))
      (node (ref "IC6") (pin "16") (pinfunction "VSS_16") (pintype "power_in"))
      (node (ref "IC6") (pin "31") (pinfunction "VSSA_31") (pintype "power_in"))
      (node (ref "IC6") (pin "38") (pinfunction "VSS_38") (pintype "power_in"))
      (node (ref "IC6") (pin "51") (pinfunction "VSS_51") (pintype "power_in"))
      (node (ref "IC6") (pin "61") (pinfunction "VSS_61") (pintype "power_in"))
      (node (ref "IC6") (pin "83") (pinfunction "VSS_83") (pintype "power_in"))
      (node (ref "IC6") (pin "94") (pinfunction "VSS_94") (pintype "power_in"))
      (node (ref "IC7") (pin "4") (pinfunction "VSS_4") (pintype "power_in"))
      (node (ref "IC8") (pin "2") (pinfunction "VSS_2") (pintype "bidirectional"))
      (node (ref "IC9") (pin "10") (pinfunction "DGND_10") (pintype "power_in"))
      (node (ref "IC9") (pin "23") (pinfunction "AGND_23") (pintype "power_in"))
      (node (ref "IC9") (pin "25") (pinfunction "CASE_25") (pintype "bidirectional"))
      (node (ref "IC9") (pin "26") (pinfunction "CASE_26") (pintype "bidirectional"))
      (node (ref "J1") (pin "2") (pinfunction "2_2") (pintype "passive"))
      (node (ref "J1") (pin "3") (pinfunction "3_3") (pintype "passive"))
      (node (ref "J10") (pin "11") (pinfunction "11_11") (pintype "bidirectional"))
      (node (ref "J11") (pin "1") (pinfunction "P_1") (pintype "bidirectional"))
      (node (ref "J12") (pin "MP1") (pinfunction "MP1_MP1") (pintype "bidirectional"))
      (node (ref "J12") (pin "MP2") (pinfunction "MP2_MP2") (pintype "bidirectional"))
      (node (ref "J2") (pin "C5") (pinfunction "GND_C5") (pintype "bidirectional"))
      (node (ref "J2") (pin "P1") (pinfunction "CASE_P1") (pintype "bidirectional"))
      (node (ref "J2") (pin "P2") (pinfunction "CASE_P2") (pintype "bidirectional"))
      (node (ref "J2") (pin "P3") (pinfunction "CASE_P3") (pintype "bidirectional"))
      (node (ref "J2") (pin "P4") (pinfunction "CASE_P4") (pintype "bidirectional"))
      (node (ref "J2") (pin "P5") (pinfunction "CASE_P5") (pintype "bidirectional"))
      (node (ref "J2") (pin "P6") (pinfunction "CASE_P6") (pintype "bidirectional"))
      (node (ref "J3") (pin "1") (pinfunction "GND_1") (pintype "bidirectional"))
      (node (ref "J3") (pin "2") (pinfunction "GND_2") (pintype "bidirectional"))
      (node (ref "J5") (pin "2") (pinfunction "2_2") (pintype "bidirectional"))
      (node (ref "J5") (pin "4") (pinfunction "4_4") (pintype "bidirectional"))
      (node (ref "J6") (pin "1") (pinfunction "P_1") (pintype "bidirectional"))
      (node (ref "J7") (pin "2") (pinfunction "2_2") (pintype "bidirectional"))
      (node (ref "J8") (pin "1") (pinfunction "P_1") (pintype "bidirectional"))
      (node (ref "J9") (pin "3") (pinfunction "3_3") (pintype "bidirectional"))
      (node (ref "JP1") (pin "3") (pinfunction "3_3") (pintype "passive"))
      (node (ref "JP2") (pin "3") (pinfunction "3_3") (pintype "passive"))
      (node (ref "L6") (pin "1") (pinfunction "1_1") (pintype "passive"))
      (node (ref "L8") (pin "1") (pinfunction "1_1") (pintype "passive"))
      (node (ref "LED1") (pin "C") (pinfunction "C_C") (pintype "passive"))
      (node (ref "LED2") (pin "C") (pinfunction "C_C") (pintype "passive"))
      (node (ref "Q11") (pin "2") (pinfunction "S_2") (pintype "passive"))
      (node (ref "Q13") (pin "2") (pinfunction "S_2") (pintype "passive"))
      (node (ref "Q15") (pin "2") (pinfunction "S_2") (pintype "passive"))
      (node (ref "Q16") (pin "2") (pinfunction "2_2") (pintype "passive"))
      (node (ref "Q16") (pin "4") (pinfunction "4_4") (pintype "passive"))
      (node (ref "Q2") (pin "2") (pinfunction "S_2") (pintype "passive"))
      (node (ref "Q4") (pin "2") (pinfunction "S_2") (pintype "passive"))
      (node (ref "Q5") (pin "E") (pinfunction "E_E") (pintype "passive"))
      (node (ref "Q6") (pin "E") (pinfunction "E_E") (pintype "passive"))
      (node (ref "Q7") (pin "2") (pinfunction "GND_2") (pintype "power_in"))
      (node (ref "Q9") (pin "2") (pinfunction "S_2") (pintype "passive"))
      (node (ref "R10") (pin "1") (pinfunction "1_1") (pintype "passive"))
      (node (ref "R100") (pin "1") (pinfunction "1_1") (pintype "passive"))
      (node (ref "R102") (pin "1") (pinfunction "1_1") (pintype "passive"))
      (node (ref "R103") (pin "1") (pinfunction "1_1") (pintype "passive"))
      (node (ref "R107") (pin "1") (pinfunction "1_1") (pintype "passive"))
      (node (ref "R108") (pin "1") (pinfunction "1_1") (pintype "passive"))
      (node (ref "R11") (pin "1") (pinfunction "1_1") (pintype "passive"))
      (node (ref "R112") (pin "1") (pinfunction "1_1") (pintype "passive"))
      (node (ref "R115") (pin "1") (pinfunction "1_1") (pintype "passive"))
      (node (ref "R116") (pin "1") (pinfunction "1_1") (pintype "passive"))
      (node (ref "R12") (pin "1") (pinfunction "1_1") (pintype "passive"))
      (node (ref "R36") (pin "1") (pinfunction "1_1") (pintype "passive"))
      (node (ref "R37") (pin "1") (pinfunction "1_1") (pintype "passive"))
      (node (ref "R4") (pin "1") (pinfunction "1_1") (pintype "passive"))
      (node (ref "R40") (pin "1") (pinfunction "1_1") (pintype "passive"))
      (node (ref "R41") (pin "1") (pinfunction "1_1") (pintype "passive"))
      (node (ref "R45") (pin "1") (pinfunction "1_1") (pintype "passive"))
      (node (ref "R46") (pin "1") (pinfunction "1_1") (pintype "passive"))
      (node (ref "R5") (pin "1") (pinfunction "1_1") (pintype "passive"))
      (node (ref "R54") (pin "1") (pinfunction "1_1") (pintype "passive"))
      (node (ref "R60") (pin "1") (pinfunction "1_1") (pintype "passive"))
      (node (ref "R79") (pin "1") (pinfunction "1_1") (pintype "passive"))
      (node (ref "R80") (pin "2") (pinfunction "2_2") (pintype "passive"))
      (node (ref "R81") (pin "2") (pinfunction "2_2") (pintype "passive"))
      (node (ref "R82") (pin "2") (pinfunction "2_2") (pintype "passive"))
      (node (ref "R83") (pin "1") (pinfunction "1_1") (pintype "passive"))
      (node (ref "R84") (pin "1") (pinfunction "1_1") (pintype "passive"))
      (node (ref "R91") (pin "1") (pinfunction "1_1") (pintype "passive"))
      (node (ref "R92") (pin "1") (pinfunction "1_1") (pintype "passive"))
      (node (ref "R97") (pin "1") (pinfunction "1_1") (pintype "passive"))
      (node (ref "R98") (pin "1") (pinfunction "1_1") (pintype "passive"))
      (node (ref "R99") (pin "1") (pinfunction "1_1") (pintype "passive"))
      (node (ref "RV1") (pin "2") (pinfunction "2_2") (pintype "bidirectional"))
      (node (ref "S1") (pin "3") (pinfunction "P_3") (pintype "passive"))
      (node (ref "S1") (pin "4") (pinfunction "P1_4") (pintype "passive"))
      (node (ref "S2") (pin "3") (pinfunction "P_3") (pintype "passive"))
      (node (ref "S2") (pin "4") (pinfunction "P1_4") (pintype "passive"))
      (node (ref "S3") (pin "1") (pinfunction "S_1") (pintype "passive"))
      (node (ref "S3") (pin "2") (pinfunction "S1_2") (pintype "passive"))
      (node (ref "X1") (pin "2") (pinfunction "KL_2") (pintype "passive"))
    )
    (net (code "47") (name "I2C1_SCL") (class "Default")
      (node (ref "IC6") (pin "136") (pinfunction "PB6_136") (pintype "bidirectional"))
      (node (ref "IC9") (pin "20") (pinfunction "SIO-C_20") (pintype "bidirectional"))
      (node (ref "R20") (pin "1") (pinfunction "1_1") (pintype "passive"))
    )
    (net (code "48") (name "I2C1_SDA") (class "Default")
      (node (ref "IC6") (pin "137") (pinfunction "PB7_137") (pintype "bidirectional"))
      (node (ref "IC9") (pin "22") (pinfunction "SIO-D_22") (pintype "bidirectional"))
      (node (ref "R21") (pin "1") (pinfunction "1_1") (pintype "passive"))
    )
    (net (code "49") (name "I2C2_SCL") (class "Default")
      (node (ref "IC6") (pin "69") (pinfunction "PB10_69") (pintype "bidirectional"))
      (node (ref "J11") (pin "5") (pinfunction "P_5") (pintype "bidirectional"))
      (node (ref "R106") (pin "1") (pinfunction "1_1") (pintype "passive"))
    )
    (net (code "50") (name "I2C2_SDA") (class "Default")
      (node (ref "IC6") (pin "70") (pinfunction "PB11_70") (pintype "bidirectional"))
      (node (ref "J11") (pin "4") (pinfunction "P_4") (pintype "bidirectional"))
      (node (ref "R105") (pin "1") (pinfunction "1_1") (pintype "passive"))
    )
    (net (code "51") (name "I2C4_SCL") (class "Default")
      (node (ref "IC6") (pin "54") (pinfunction "PF14_54") (pintype "bidirectional"))
      (node (ref "J6") (pin "3") (pinfunction "P_3") (pintype "bidirectional"))
      (node (ref "R89") (pin "1") (pinfunction "1_1") (pintype "passive"))
    )
    (net (code "52") (name "I2C4_SDA") (class "Default")
      (node (ref "IC6") (pin "55") (pinfunction "PF15_55") (pintype "bidirectional"))
      (node (ref "J6") (pin "2") (pinfunction "P_2") (pintype "bidirectional"))
      (node (ref "R90") (pin "1") (pinfunction "1_1") (pintype "passive"))
    )
    (net (code "53") (name "LTE1V8") (class "Default")
      (node (ref "C68") (pin "1") (pinfunction "1_1") (pintype "passive"))
      (node (ref "C69") (pin "1") (pinfunction "1_1") (pintype "passive"))
      (node (ref "IC11") (pin "1") (pinfunction "VCCA_1") (pintype "bidirectional"))
      (node (ref "IC12") (pin "15") (pinfunction "VDD_1V8_15") (pintype "power_in"))
      (node (ref "IC13") (pin "1") (pinfunction "VCCA_1") (pintype "bidirectional"))
      (node (ref "R43") (pin "2") (pinfunction "2_2") (pintype "passive"))
      (node (ref "R50") (pin "2") (pinfunction "2_2") (pintype "passive"))
    )
    (net (code "54") (name "LTE_PWRKEY") (class "Default")
      (node (ref "IC6") (pin "1") (pinfunction "PE2_1") (pintype "bidirectional"))
      (node (ref "R42") (pin "1") (pinfunction "1_1") (pintype "passive"))
    )
    (net (code "55") (name "LTE_RESET") (class "Default")
      (node (ref "IC6") (pin "140") (pinfunction "PB9_140") (pintype "bidirectional"))
      (node (ref "R44") (pin "1") (pinfunction "1_1") (pintype "passive"))
    )
    (net (code "56") (name "NRST") (class "Default")
      (node (ref "C95") (pin "1") (pinfunction "1_1") (pintype "passive"))
      (node (ref "IC6") (pin "25") (pinfunction "NRST_25") (pintype "input"))
      (node (ref "R109") (pin "1") (pinfunction "1_1") (pintype "passive"))
      (node (ref "S3") (pin "3") (pinfunction "P_3") (pintype "passive"))
      (node (ref "S3") (pin "4") (pinfunction "P1_4") (pintype "passive"))
    )
    (net (code "57") (name "Net-(C5-Pad1)") (class "Default")
      (node (ref "C5") (pin "1") (pinfunction "1_1") (pintype "passive"))
      (node (ref "C6") (pin "+") (pinfunction "+_+") (pintype "passive"))
      (node (ref "L1") (pin "P$2") (pinfunction "P$2_P$2") (pintype "bidirectional"))
      (node (ref "L2") (pin "2") (pinfunction "2_2") (pintype "passive"))
      (node (ref "R2") (pin "2") (pinfunction "2_2") (pintype "passive"))
    )
    (net (code "58") (name "Net-(C14-Pad1)") (class "Default")
      (node (ref "C14") (pin "1") (pinfunction "1_1") (pintype "passive"))
      (node (ref "C18") (pin "+") (pinfunction "+_+") (pintype "passive"))
      (node (ref "L4") (pin "P$2") (pinfunction "P$2_P$2") (pintype "bidirectional"))
      (node (ref "R7") (pin "1") (pinfunction "1_1") (pintype "passive"))
      (node (ref "R9") (pin "2") (pinfunction "2_2") (pintype "passive"))
    )
    (net (code "59") (name "Net-(C34-Pad1)") (class "Default")
      (node (ref "C34") (pin "1") (pinfunction "1_1") (pintype "passive"))
      (node (ref "IC6") (pin "71") (pinfunction "VCAP_71") (pintype "power_in"))
    )
    (net (code "60") (name "Net-(C35-Pad1)") (class "Default")
      (node (ref "C35") (pin "1") (pinfunction "1_1") (pintype "passive"))
      (node (ref "IC6") (pin "106") (pinfunction "VCAP_106") (pintype "power_in"))
    )
    (net (code "61") (name "Net-(C73-Pad1)") (class "Default")
      (node (ref "C73") (pin "1") (pinfunction "1_1") (pintype "passive"))
      (node (ref "R51") (pin "2") (pinfunction "2_2") (pintype "passive"))
      (node (ref "R52") (pin "1") (pinfunction "1_1") (pintype "passive"))
    )
    (net (code "62") (name "Net-(FL1-CLK_IN)") (class "Default")
      (node (ref "C64") (pin "1") (pinfunction "1_1") (pintype "passive"))
      (node (ref "FL1") (pin "7") (pinfunction "CLK_IN_7") (pintype "bidirectional"))
      (node (ref "IC12") (pin "32") (pinfunction "SIM_CLK_32") (pintype "bidirectional"))
    )
    (net (code "63") (name "Net-(FL1-CLK_OUT)") (class "Default")
      (node (ref "FL1") (pin "2") (pinfunction "CLK_OUT_2") (pintype "bidirectional"))
      (node (ref "R48") (pin "1") (pinfunction "1_1") (pintype "passive"))
    )
    (net (code "64") (name "Net-(FL1-DATA1_IN)") (class "Default")
      (node (ref "C65") (pin "1") (pinfunction "1_1") (pintype "passive"))
      (node (ref "FL1") (pin "8") (pinfunction "DATA1_IN_8") (pintype "bidirectional"))
      (node (ref "IC12") (pin "31") (pinfunction "SIM_DATA_31") (pintype "bidirectional"))
    )
    (net (code "65") (name "Net-(FL1-DATA1_OUT)") (class "Default")
      (node (ref "FL1") (pin "1") (pinfunction "DATA1_OUT_1") (pintype "bidirectional"))
      (node (ref "R47") (pin "1") (pinfunction "1_1") (pintype "passive"))
    )
    (net (code "66") (name "Net-(FL1-DATA2_IN)") (class "Default")
      (node (ref "C63") (pin "1") (pinfunction "1_1") (pintype "passive"))
      (node (ref "FL1") (pin "6") (pinfunction "DATA2_IN_6") (pintype "bidirectional"))
      (node (ref "IC12") (pin "33") (pinfunction "SIM_RST_33") (pintype "bidirectional"))
    )
    (net (code "67") (name "Net-(FL1-DATA2_OUT)") (class "Default")
      (node (ref "FL1") (pin "3") (pinfunction "DATA2_OUT_3") (pintype "bidirectional"))
      (node (ref "R49") (pin "1") (pinfunction "1_1") (pintype "passive"))
    )
    (net (code "68") (name "Net-(FL1-VCC)") (class "Default")
      (node (ref "C66") (pin "1") (pinfunction "1_1") (pintype "passive"))
      (node (ref "C67") (pin "1") (pinfunction "1_1") (pintype "passive"))
      (node (ref "FL1") (pin "5") (pinfunction "VCC_5") (pintype "bidirectional"))
      (node (ref "IC12") (pin "30") (pinfunction "SIM_VDD_30") (pintype "bidirectional"))
      (node (ref "J2") (pin "C1") (pinfunction "VCC_C1") (pintype "bidirectional"))
    )
    (net (code "69") (name "Net-(IC1-EN{slash}SS)") (class "Default")
      (node (ref "C4") (pin "1") (pinfunction "1_1") (pintype "passive"))
      (node (ref "IC1") (pin "3") (pinfunction "EN/SS_3") (pintype "bidirectional"))
      (node (ref "R1") (pin "2") (pinfunction "2_2") (pintype "passive"))
      (node (ref "R4") (pin "2") (pinfunction "2_2") (pintype "passive"))
    )
    (net (code "70") (name "Net-(IC1-FB)") (class "Default")
      (node (ref "IC1") (pin "4") (pinfunction "FB_4") (pintype "bidirectional"))
      (node (ref "R2") (pin "1") (pinfunction "1_1") (pintype "passive"))
      (node (ref "R5") (pin "2") (pinfunction "2_2") (pintype "passive"))
    )
    (net (code "71") (name "Net-(IC1-LX)") (class "Default")
      (node (ref "IC1") (pin "5") (pinfunction "LX_5") (pintype "bidirectional"))
      (node (ref "L1") (pin "P$1") (pinfunction "P$1_P$1") (pintype "bidirectional"))
    )
    (net (code "72") (name "Net-(IC2-CE)") (class "Default")
      (node (ref "C7") (pin "1") (pinfunction "1_1") (pintype "passive"))
      (node (ref "C8") (pin "1") (pinfunction "1_1") (pintype "passive"))
      (node (ref "IC2") (pin "1") (pinfunction "VIN_1") (pintype "bidirectional"))
      (node (ref "IC2") (pin "3") (pinfunction "CE_3") (pintype "bidirectional"))
      (node (ref "L2") (pin "1") (pinfunction "1_1") (pintype "passive"))
    )
    (net (code "73") (name "Net-(IC3-C)") (class "Default")
      (node (ref "C11") (pin "1") (pinfunction "1_1") (pintype "passive"))
      (node (ref "IC3") (pin "2") (pinfunction "C_2") (pintype "passive"))
      (node (ref "L3") (pin "1") (pinfunction "1_1") (pintype "passive"))
      (node (ref "R3") (pin "1") (pinfunction "1_1") (pintype "passive"))
    )
    (net (code "74") (name "Net-(IC4-BOOT)") (class "Default")
      (node (ref "C13") (pin "1") (pinfunction "1_1") (pintype "passive"))
      (node (ref "IC4") (pin "2") (pinfunction "BOOT_2") (pintype "bidirectional"))
    )
    (net (code "75") (name "Net-(IC4-EN{slash}CLKIN)") (class "Default")
      (node (ref "IC4") (pin "5") (pinfunction "EN/CLKIN_5") (pintype "bidirectional"))
      (node (ref "Q1") (pin "3") (pinfunction "D_3") (pintype "passive"))
      (node (ref "R11") (pin "2") (pinfunction "2_2") (pintype "passive"))
    )
    (net (code "76") (name "Net-(IC4-FB{slash}VOUT)") (class "Default")
      (node (ref "C14") (pin "2") (pinfunction "2_2") (pintype "passive"))
      (node (ref "IC4") (pin "4") (pinfunction "FB/VOUT_4") (pintype "bidirectional"))
      (node (ref "R12") (pin "2") (pinfunction "2_2") (pintype "passive"))
      (node (ref "R9") (pin "1") (pinfunction "1_1") (pintype "passive"))
    )
    (net (code "77") (name "Net-(IC4-SW)") (class "Default")
      (node (ref "C13") (pin "2") (pinfunction "2_2") (pintype "passive"))
      (node (ref "IC4") (pin "1") (pinfunction "SW_1") (pintype "bidirectional"))
      (node (ref "L4") (pin "P$1") (pinfunction "P$1_P$1") (pintype "bidirectional"))
    )
    (net (code "78") (name "Net-(IC4-VCC)") (class "Default")
      (node (ref "C17") (pin "1") (pinfunction "1_1") (pintype "passive"))
      (node (ref "IC4") (pin "3") (pinfunction "VCC_3") (pintype "bidirectional"))
    )
    (net (code "79") (name "Net-(IC6B-BOOT0)") (class "Default")
      (node (ref "IC6") (pin "138") (pinfunction "BOOT0_138") (pintype "input"))
      (node (ref "R111") (pin "1") (pinfunction "1_1") (pintype "passive"))
      (node (ref "R112") (pin "2") (pinfunction "2_2") (pintype "passive"))
    )
    (net (code "80") (name "Net-(IC6B-PDR_ON)") (class "Default")
      (node (ref "IC6") (pin "143") (pinfunction "PDR_ON_143") (pintype "input"))
      (node (ref "R110") (pin "1") (pinfunction "1_1") (pintype "passive"))
    )
    (net (code "81") (name "Net-(IC7-SCLK)") (class "Default")
      (node (ref "IC7") (pin "6") (pinfunction "SCLK_6") (pintype "bidirectional"))
      (node (ref "R18") (pin "1") (pinfunction "1_1") (pintype "passive"))
    )
    (net (code "82") (name "Net-(IC7-SIO2)") (class "Default")
      (node (ref "IC7") (pin "3") (pinfunction "SIO2_3") (pintype "bidirectional"))
      (node (ref "R17") (pin "2") (pinfunction "2_2") (pintype "passive"))
    )
    (net (code "83") (name "Net-(IC7-SIO3)") (class "Default")
      (node (ref "IC7") (pin "7") (pinfunction "SIO3_7") (pintype "bidirectional"))
      (node (ref "R16") (pin "1") (pinfunction "1_1") (pintype "passive"))
    )
    (net (code "84") (name "Net-(IC7-SI{slash}SIO0)") (class "Default")
      (node (ref "IC7") (pin "5") (pinfunction "SI/SIO0_5") (pintype "bidirectional"))
      (node (ref "R19") (pin "1") (pinfunction "1_1") (pintype "passive"))
    )
    (net (code "85") (name "Net-(IC7-SO{slash}SIO1)") (class "Default")
      (node (ref "IC7") (pin "2") (pinfunction "SO/SIO1_2") (pintype "bidirectional"))
      (node (ref "R15") (pin "2") (pinfunction "2_2") (pintype "passive"))
    )
    (net (code "86") (name "Net-(IC7-~{CE})") (class "Default")
      (node (ref "IC7") (pin "1") (pinfunction "~{CE}_1") (pintype "bidirectional"))
      (node (ref "R14") (pin "2") (pinfunction "2_2") (pintype "passive"))
    )
    (net (code "87") (name "Net-(IC8-VOUT)") (class "Default")
      (node (ref "C48") (pin "1") (pinfunction "1_1") (pintype "passive"))
      (node (ref "IC8") (pin "5") (pinfunction "VOUT_5") (pintype "bidirectional"))
      (node (ref "L5") (pin "1") (pinfunction "1_1") (pintype "passive"))
    )
    (net (code "88") (name "Net-(IC9-AVDD2.5-3.0V)") (class "Default")
      (node (ref "C49") (pin "1") (pinfunction "1_1") (pintype "passive"))
      (node (ref "IC9") (pin "21") (pinfunction "AVDD2.5-3.0V_21") (pintype "power_in"))
      (node (ref "L5") (pin "2") (pinfunction "2_2") (pintype "passive"))
    )
    (net (code "89") (name "Net-(IC9-HREF)") (class "Default")
      (node (ref "IC9") (pin "16") (pinfunction "HREF_16") (pintype "bidirectional"))
      (node (ref "R34") (pin "1") (pinfunction "1_1") (pintype "passive"))
    )
    (net (code "90") (name "Net-(IC9-MCLK)") (class "Default")
      (node (ref "IC9") (pin "12") (pinfunction "MCLK_12") (pintype "bidirectional"))
      (node (ref "R41") (pin "2") (pinfunction "2_2") (pintype "passive"))
    )
    (net (code "91") (name "Net-(IC9-PCLK)") (class "Default")
      (node (ref "IC9") (pin "8") (pinfunction "PCLK_8") (pintype "bidirectional"))
      (node (ref "R33") (pin "1") (pinfunction "1_1") (pintype "passive"))
    )
    (net (code "92") (name "Net-(IC9-PWDN)") (class "Default")
      (node (ref "IC9") (pin "17") (pinfunction "PWDN_17") (pintype "bidirectional"))
      (node (ref "R38") (pin "1") (pinfunction "1_1") (pintype "passive"))
    )
    (net (code "93") (name "Net-(IC9-RESET)") (class "Default")
      (node (ref "C54") (pin "1") (pinfunction "1_1") (pintype "passive"))
      (node (ref "IC9") (pin "19") (pinfunction "RESET_19") (pintype "bidirectional"))
      (node (ref "R39") (pin "1") (pinfunction "1_1") (pintype "passive"))
    )
    (net (code "94") (name "Net-(IC9-STROEB)") (class "Default")
      (node (ref "IC9") (pin "24") (pinfunction "STROEB_24") (pintype "power_in"))
      (node (ref "R40") (pin "2") (pinfunction "2_2") (pintype "passive"))
    )
    (net (code "95") (name "Net-(IC9-VSYNC)") (class "Default")
      (node (ref "IC9") (pin "18") (pinfunction "VSYNC_18") (pintype "bidirectional"))
      (node (ref "R35") (pin "1") (pinfunction "1_1") (pintype "passive"))
    )
    (net (code "96") (name "Net-(IC9-Y0)") (class "Default")
      (node (ref "IC9") (pin "1") (pinfunction "Y0_1") (pintype "bidirectional"))
      (node (ref "R22") (pin "1") (pinfunction "1_1") (pintype "passive"))
    )
    (net (code "97") (name "Net-(IC9-Y1)") (class "Default")
      (node (ref "IC9") (pin "2") (pinfunction "Y1_2") (pintype "bidirectional"))
      (node (ref "R23") (pin "1") (pinfunction "1_1") (pintype "passive"))
    )
    (net (code "98") (name "Net-(IC9-Y2)") (class "Default")
      (node (ref "IC9") (pin "6") (pinfunction "Y2_6") (pintype "bidirectional"))
      (node (ref "R24") (pin "1") (pinfunction "1_1") (pintype "passive"))
    )
    (net (code "99") (name "Net-(IC9-Y3)") (class "Default")
      (node (ref "IC9") (pin "4") (pinfunction "Y3_4") (pintype "bidirectional"))
      (node (ref "R25") (pin "1") (pinfunction "1_1") (pintype "passive"))
    )
    (net (code "100") (name "Net-(IC9-Y4)") (class "Default")
      (node (ref "IC9") (pin "3") (pinfunction "Y4_3") (pintype "bidirectional"))
      (node (ref "R27") (pin "1") (pinfunction "1_1") (pintype "passive"))
    )
    (net (code "101") (name "Net-(IC9-Y5)") (class "Default")
      (node (ref "IC9") (pin "5") (pinfunction "Y5_5") (pintype "bidirectional"))
      (node (ref "R28") (pin "1") (pinfunction "1_1") (pintype "passive"))
    )
    (net (code "102") (name "Net-(IC9-Y6)") (class "Default")
      (node (ref "IC9") (pin "7") (pinfunction "Y6_7") (pintype "bidirectional"))
      (node (ref "R29") (pin "1") (pinfunction "1_1") (pintype "passive"))
    )
    (net (code "103") (name "Net-(IC9-Y7)") (class "Default")
      (node (ref "IC9") (pin "9") (pinfunction "Y7_9") (pintype "bidirectional"))
      (node (ref "R30") (pin "1") (pinfunction "1_1") (pintype "passive"))
    )
    (net (code "104") (name "Net-(IC9-Y8)") (class "Default")
      (node (ref "IC9") (pin "11") (pinfunction "Y8_11") (pintype "bidirectional"))
      (node (ref "R31") (pin "1") (pinfunction "1_1") (pintype "passive"))
    )
    (net (code "105") (name "Net-(IC9-Y9)") (class "Default")
      (node (ref "IC9") (pin "13") (pinfunction "Y9_13") (pintype "bidirectional"))
      (node (ref "R32") (pin "1") (pinfunction "1_1") (pintype "passive"))
    )
    (net (code "106") (name "Net-(IC10-CE)") (class "Default")
      (node (ref "C51") (pin "1") (pinfunction "1_1") (pintype "passive"))
      (node (ref "IC10") (pin "3") (pinfunction "CE_3") (pintype "bidirectional"))
      (node (ref "IC8") (pin "3") (pinfunction "CE_3") (pintype "bidirectional"))
      (node (ref "IC9") (pin "14") (pinfunction "IOVDD1.8-3.3V_14") (pintype "power_in"))
      (node (ref "Q3") (pin "3") (pinfunction "D_3") (pintype "passive"))
      (node (ref "R37") (pin "2") (pinfunction "2_2") (pintype "passive"))
    )
    (net (code "107") (name "Net-(IC10-VOUT)") (class "Default")
      (node (ref "C50") (pin "1") (pinfunction "1_1") (pintype "passive"))
      (node (ref "IC10") (pin "5") (pinfunction "VOUT_5") (pintype "bidirectional"))
      (node (ref "IC9") (pin "15") (pinfunction "DVDD1.2-1.3V_15") (pintype "power_in"))
    )
    (net (code "108") (name "Net-(IC11-A1)") (class "Default")
      (node (ref "IC11") (pin "2") (pinfunction "A1_2") (pintype "bidirectional"))
      (node (ref "IC12") (pin "10") (pinfunction "RXD_10") (pintype "bidirectional"))
    )
    (net (code "109") (name "Net-(IC11-A2)") (class "Default")
      (node (ref "IC11") (pin "3") (pinfunction "A2_3") (pintype "bidirectional"))
      (node (ref "IC12") (pin "9") (pinfunction "TXD_9") (pintype "bidirectional"))
    )
    (net (code "110") (name "Net-(IC11-A3)") (class "Default")
      (node (ref "IC11") (pin "4") (pinfunction "A3_4") (pintype "bidirectional"))
      (node (ref "IC12") (pin "8") (pinfunction "RTS_8") (pintype "bidirectional"))
    )
    (net (code "111") (name "Net-(IC11-A4)") (class "Default")
      (node (ref "IC11") (pin "5") (pinfunction "A4_5") (pintype "bidirectional"))
      (node (ref "IC12") (pin "7") (pinfunction "CTS_7") (pintype "bidirectional"))
    )
    (net (code "112") (name "Net-(IC12A-PCM_CLK)") (class "Default")
      (node (ref "IC12") (pin "11") (pinfunction "PCM_CLK_11") (pintype "bidirectional"))
      (node (ref "IC13") (pin "5") (pinfunction "A4_5") (pintype "bidirectional"))
    )
    (net (code "113") (name "Net-(IC12A-PCM_DIN)") (class "Default")
      (node (ref "IC12") (pin "13") (pinfunction "PCM_DIN_13") (pintype "bidirectional"))
      (node (ref "IC13") (pin "3") (pinfunction "A2_3") (pintype "bidirectional"))
    )
    (net (code "114") (name "Net-(IC12A-PCM_OUT)") (class "Default")
      (node (ref "IC12") (pin "14") (pinfunction "PCM_OUT_14") (pintype "bidirectional"))
      (node (ref "IC13") (pin "2") (pinfunction "A1_2") (pintype "bidirectional"))
    )
    (net (code "115") (name "Net-(IC12A-PCM_SYNC)") (class "Default")
      (node (ref "IC12") (pin "12") (pinfunction "PCM_SYNC_12") (pintype "bidirectional"))
      (node (ref "IC13") (pin "4") (pinfunction "A3_4") (pintype "bidirectional"))
    )
    (net (code "116") (name "Net-(IC12A-PWRKEY)") (class "Default")
      (node (ref "IC12") (pin "1") (pinfunction "PWRKEY_1") (pintype "bidirectional"))
      (node (ref "Q6") (pin "C") (pinfunction "C_C") (pintype "passive"))
    )
    (net (code "117") (name "Net-(IC12A-RESET)") (class "Default")
      (node (ref "IC12") (pin "16") (pinfunction "RESET_16") (pintype "bidirectional"))
      (node (ref "Q5") (pin "C") (pinfunction "C_C") (pintype "passive"))
    )
    (net (code "118") (name "Net-(IC12A-RF_ANT)") (class "Default")
      (node (ref "C72") (pin "1") (pinfunction "1_1") (pintype "passive"))
      (node (ref "IC12") (pin "60") (pinfunction "RF_ANT_60") (pintype "bidirectional"))
      (node (ref "R51") (pin "1") (pinfunction "1_1") (pintype "passive"))
    )
    (net (code "119") (name "Net-(IC12A-SIM_DET)") (class "Default")
      (node (ref "IC12") (pin "34") (pinfunction "SIM_DET_34") (pintype "bidirectional"))
      (node (ref "R43") (pin "1") (pinfunction "1_1") (pintype "passive"))
    )
    (net (code "120") (name "Net-(IC12A-USB_BOOT)") (class "Default")
      (node (ref "IC12") (pin "6") (pinfunction "USB_BOOT_6") (pintype "bidirectional"))
      (node (ref "SJ1") (pin "1") (pinfunction "1_1") (pintype "passive"))
    )
    (net (code "121") (name "Net-(IC12A-USB_DM)") (class "Default")
      (node (ref "IC12") (pin "28") (pinfunction "USB_DM_28") (pintype "bidirectional"))
      (node (ref "IC14") (pin "1") (pinfunction "D+_IN_1") (pintype "input"))
    )
    (net (code "122") (name "Net-(IC12A-USB_DP)") (class "Default")
      (node (ref "IC12") (pin "27") (pinfunction "USB_DP_27") (pintype "bidirectional"))
      (node (ref "IC14") (pin "3") (pinfunction "D-_IN_3") (pintype "input"))
    )
    (net (code "123") (name "Net-(IC12A-VBUS)") (class "Default")
      (node (ref "IC12") (pin "24") (pinfunction "VBUS_24") (pintype "bidirectional"))
      (node (ref "R53") (pin "2") (pinfunction "2_2") (pintype "passive"))
    )
    (net (code "124") (name "Net-(IC14-VDD)") (class "Default")
      (node (ref "C74") (pin "1") (pinfunction "1_1") (pintype "passive"))
      (node (ref "IC14") (pin "5") (pinfunction "VDD_5") (pintype "power_in"))
      (node (ref "R53") (pin "1") (pinfunction "1_1") (pintype "passive"))
      (node (ref "R54") (pin "2") (pinfunction "2_2") (pintype "passive"))
      (node (ref "TP1") (pin "TP") (pinfunction "TP_TP") (pintype "input"))
    )
    (net (code "125") (name "Net-(IC15-IO2)") (class "Default")
      (node (ref "IC15") (pin "38") (pinfunction "IO2_38") (pintype "bidirectional"))
      (node (ref "R55") (pin "1") (pinfunction "1_1") (pintype "passive"))
    )
    (net (code "126") (name "Net-(IC17-VDD)") (class "Default")
      (node (ref "C100") (pin "1") (pinfunction "1_1") (pintype "passive"))
      (node (ref "IC17") (pin "5") (pinfunction "VDD_5") (pintype "power_in"))
      (node (ref "J12") (pin "1") (pinfunction "1_1") (pintype "bidirectional"))
      (node (ref "R111") (pin "2") (pinfunction "2_2") (pintype "passive"))
      (node (ref "R115") (pin "2") (pinfunction "2_2") (pintype "passive"))
    )
    (net (code "127") (name "Net-(J2-CLK)") (class "Default")
      (node (ref "J2") (pin "C3") (pinfunction "CLK_C3") (pintype "bidirectional"))
      (node (ref "R48") (pin "2") (pinfunction "2_2") (pintype "passive"))
    )
    (net (code "128") (name "Net-(J2-I{slash}O)") (class "Default")
      (node (ref "J2") (pin "C7") (pinfunction "I/O_C7") (pintype "bidirectional"))
      (node (ref "R47") (pin "2") (pinfunction "2_2") (pintype "passive"))
    )
    (net (code "129") (name "Net-(J2-RST)") (class "Default")
      (node (ref "J2") (pin "C2") (pinfunction "RST_C2") (pintype "bidirectional"))
      (node (ref "R49") (pin "2") (pinfunction "2_2") (pintype "passive"))
    )
    (net (code "130") (name "Net-(J3-SIG)") (class "Default")
      (node (ref "J3") (pin "3") (pinfunction "SIG_3") (pintype "bidirectional"))
      (node (ref "R52") (pin "2") (pinfunction "2_2") (pintype "passive"))
      (node (ref "RV1") (pin "1") (pinfunction "1_1") (pintype "bidirectional"))
    )
    (net (code "131") (name "Net-(J4-CATHODE_GREEN)") (class "Default")
      (node (ref "J4") (pin "11") (pinfunction "CATHODE_GREEN_11") (pintype "bidirectional"))
      (node (ref "R82") (pin "1") (pinfunction "1_1") (pintype "passive"))
    )
    (net (code "132") (name "Net-(J4-CATHODE_YELLOW)") (class "Default")
      (node (ref "J4") (pin "2") (pinfunction "CATHODE_YELLOW_2") (pintype "bidirectional"))
      (node (ref "R81") (pin "1") (pinfunction "1_1") (pintype "passive"))
    )
    (net (code "133") (name "Net-(J6D-P)") (class "Default")
      (node (ref "J6") (pin "4") (pinfunction "P_4") (pintype "bidirectional"))
      (node (ref "Q8") (pin "3") (pinfunction "D_3") (pintype "passive"))
      (node (ref "R92") (pin "2") (pinfunction "2_2") (pintype "passive"))
    )
    (net (code "134") (name "Net-(J8H-P)") (class "Default")
      (node (ref "J8") (pin "8") (pinfunction "P_8") (pintype "bidirectional"))
      (node (ref "Q10") (pin "3") (pinfunction "D_3") (pintype "passive"))
      (node (ref "R98") (pin "2") (pinfunction "2_2") (pintype "passive"))
    )
    (net (code "135") (name "Net-(J11G-P)") (class "Default")
      (node (ref "J11") (pin "7") (pinfunction "P_7") (pintype "bidirectional"))
      (node (ref "Q14") (pin "3") (pinfunction "D_3") (pintype "passive"))
      (node (ref "R108") (pin "2") (pinfunction "2_2") (pintype "passive"))
    )
    (net (code "136") (name "Net-(J11H-P)") (class "Default")
      (node (ref "J11") (pin "8") (pinfunction "P_8") (pintype "bidirectional"))
      (node (ref "Q12") (pin "3") (pinfunction "D_3") (pintype "passive"))
      (node (ref "R103") (pin "2") (pinfunction "2_2") (pintype "passive"))
    )
    (net (code "137") (name "Net-(J12-Pad4)") (class "Default")
      (node (ref "J12") (pin "4") (pinfunction "4_4") (pintype "bidirectional"))
      (node (ref "L8") (pin "2") (pinfunction "2_2") (pintype "passive"))
    )
    (net (code "138") (name "Net-(JP1-Pad1)") (class "Default")
      (node (ref "JP1") (pin "1") (pinfunction "1_1") (pintype "passive"))
      (node (ref "R58") (pin "1") (pinfunction "1_1") (pintype "passive"))
    )
    (net (code "139") (name "Net-(JP2-Pad1)") (class "Default")
      (node (ref "JP2") (pin "1") (pinfunction "1_1") (pintype "passive"))
      (node (ref "R113") (pin "1") (pinfunction "1_1") (pintype "passive"))
    )
    (net (code "140") (name "Net-(L6-Pad2)") (class "Default")
      (node (ref "L6") (pin "2") (pinfunction "2_2") (pintype "passive"))
      (node (ref "TP4") (pin "TP") (pinfunction "TP_TP") (pintype "input"))
    )
    (net (code "141") (name "Net-(LED1-PadA)") (class "Default")
      (node (ref "LED1") (pin "A") (pinfunction "A_A") (pintype "passive"))
      (node (ref "R55") (pin "2") (pinfunction "2_2") (pintype "passive"))
    )
    (net (code "142") (name "Net-(LED2-PadA)") (class "Default")
      (node (ref "LED2") (pin "A") (pinfunction "A_A") (pintype "passive"))
      (node (ref "R117") (pin "2") (pinfunction "2_2") (pintype "passive"))
    )
    (net (code "143") (name "Net-(Q1-G)") (class "Default")
      (node (ref "Q1") (pin "1") (pinfunction "G_1") (pintype "passive"))
      (node (ref "Q2") (pin "3") (pinfunction "D_3") (pintype "passive"))
      (node (ref "R6") (pin "2") (pinfunction "2_2") (pintype "passive"))
    )
    (net (code "144") (name "Net-(Q2-G)") (class "Default")
      (node (ref "Q2") (pin "1") (pinfunction "G_1") (pintype "passive"))
      (node (ref "R10") (pin "2") (pinfunction "2_2") (pintype "passive"))
      (node (ref "R8") (pin "1") (pinfunction "1_1") (pintype "passive"))
    )
    (net (code "145") (name "Net-(Q3-G)") (class "Default")
      (node (ref "Q3") (pin "1") (pinfunction "G_1") (pintype "passive"))
      (node (ref "Q4") (pin "3") (pinfunction "D_3") (pintype "passive"))
      (node (ref "R26") (pin "1") (pinfunction "1_1") (pintype "passive"))
    )
    (net (code "146") (name "Net-(Q5-PadB)") (class "Default")
      (node (ref "Q5") (pin "B") (pinfunction "B_B") (pintype "passive"))
      (node (ref "R44") (pin "2") (pinfunction "2_2") (pintype "passive"))
      (node (ref "R45") (pin "2") (pinfunction "2_2") (pintype "passive"))
    )
    (net (code "147") (name "Net-(Q6-PadB)") (class "Default")
      (node (ref "Q6") (pin "B") (pinfunction "B_B") (pintype "passive"))
      (node (ref "R42") (pin "2") (pinfunction "2_2") (pintype "passive"))
      (node (ref "R46") (pin "2") (pinfunction "2_2") (pintype "passive"))
    )
    (net (code "148") (name "Net-(Q7-~{ST})") (class "Default")
      (node (ref "Q7") (pin "1") (pinfunction "~{ST}_1") (pintype "input"))
      (node (ref "R85") (pin "1") (pinfunction "1_1") (pintype "passive"))
    )
    (net (code "149") (name "Net-(Q8-G)") (class "Default")
      (node (ref "Q8") (pin "1") (pinfunction "G_1") (pintype "passive"))
      (node (ref "Q9") (pin "3") (pinfunction "D_3") (pintype "passive"))
      (node (ref "R88") (pin "2") (pinfunction "2_2") (pintype "passive"))
    )
    (net (code "150") (name "Net-(Q10-G)") (class "Default")
      (node (ref "Q10") (pin "1") (pinfunction "G_1") (pintype "passive"))
      (node (ref "Q11") (pin "3") (pinfunction "D_3") (pintype "passive"))
      (node (ref "R93") (pin "2") (pinfunction "2_2") (pintype "passive"))
    )
    (net (code "151") (name "Net-(Q12-G)") (class "Default")
      (node (ref "Q12") (pin "1") (pinfunction "G_1") (pintype "passive"))
      (node (ref "Q13") (pin "3") (pinfunction "D_3") (pintype "passive"))
      (node (ref "R101") (pin "2") (pinfunction "2_2") (pintype "passive"))
    )
    (net (code "152") (name "Net-(Q14-G)") (class "Default")
      (node (ref "Q14") (pin "1") (pinfunction "G_1") (pintype "passive"))
      (node (ref "Q15") (pin "3") (pinfunction "D_3") (pintype "passive"))
      (node (ref "R104") (pin "2") (pinfunction "2_2") (pintype "passive"))
    )
    (net (code "153") (name "Net-(R50-Pad1)") (class "Default")
      (node (ref "R50") (pin "1") (pinfunction "1_1") (pintype "passive"))
      (node (ref "SJ1") (pin "2") (pinfunction "2_2") (pintype "passive"))
    )
    (net (code "154") (name "Net-(X1A-KL)") (class "Default")
      (node (ref "F1") (pin "1A") (pinfunction "1A_1A") (pintype "passive"))
      (node (ref "F1") (pin "1B") (pinfunction "1B_1B") (pintype "passive"))
      (node (ref "J1") (pin "1") (pinfunction "1_1") (pintype "passive"))
      (node (ref "X1") (pin "1") (pinfunction "KL_1") (pintype "passive"))
    )
    (net (code "155") (name "OCTOSPIM_P1_CLK") (class "Default")
      (node (ref "IC6") (pin "22") (pinfunction "PF10_22") (pintype "bidirectional"))
      (node (ref "R18") (pin "2") (pinfunction "2_2") (pintype "passive"))
    )
    (net (code "156") (name "OCTOSPIM_P1_NCS") (class "Default")
      (node (ref "IC6") (pin "64") (pinfunction "PE11_64") (pintype "bidirectional"))
      (node (ref "R13") (pin "1") (pinfunction "1_1") (pintype "passive"))
      (node (ref "R14") (pin "1") (pinfunction "1_1") (pintype "passive"))
    )
    (net (code "157") (name "OCTOSPIM_P2_IO0") (class "Default")
      (node (ref "IC6") (pin "10") (pinfunction "PF0_10") (pintype "bidirectional"))
      (node (ref "R19") (pin "2") (pinfunction "2_2") (pintype "passive"))
    )
    (net (code "158") (name "OCTOSPIM_P2_IO1") (class "Default")
      (node (ref "IC6") (pin "11") (pinfunction "PF1_11") (pintype "bidirectional"))
      (node (ref "R15") (pin "1") (pinfunction "1_1") (pintype "passive"))
    )
    (net (code "159") (name "OCTOSPIM_P2_IO2") (class "Default")
      (node (ref "IC6") (pin "12") (pinfunction "PF2_12") (pintype "bidirectional"))
      (node (ref "R17") (pin "1") (pinfunction "1_1") (pintype "passive"))
    )
    (net (code "160") (name "OCTOSPIM_P2_IO3") (class "Default")
      (node (ref "IC6") (pin "13") (pinfunction "PF3_13") (pintype "bidirectional"))
      (node (ref "R16") (pin "2") (pinfunction "2_2") (pintype "passive"))
    )
    (net (code "161") (name "PMS_RESET") (class "Default")
      (node (ref "IC6") (pin "100") (pinfunction "PA8_100") (pintype "bidirectional"))
      (node (ref "J8") (pin "7") (pinfunction "P_7") (pintype "bidirectional"))
      (node (ref "R100") (pin "2") (pinfunction "2_2") (pintype "passive"))
      (node (ref "R95") (pin "1") (pinfunction "1_1") (pintype "passive"))
    )
    (net (code "162") (name "PMS_SET") (class "Default")
      (node (ref "IC6") (pin "102") (pinfunction "PA10_102") (pintype "bidirectional"))
      (node (ref "J8") (pin "6") (pinfunction "P_6") (pintype "bidirectional"))
      (node (ref "R94") (pin "1") (pinfunction "1_1") (pintype "passive"))
      (node (ref "R99") (pin "2") (pinfunction "2_2") (pintype "passive"))
    )
    (net (code "163") (name "PROG") (class "Default")
      (node (ref "C78") (pin "1") (pinfunction "1_1") (pintype "passive"))
      (node (ref "IC15") (pin "27") (pinfunction "IO0_27") (pintype "bidirectional"))
      (node (ref "R59") (pin "1") (pinfunction "1_1") (pintype "passive"))
      (node (ref "S2") (pin "1") (pinfunction "S_1") (pintype "passive"))
      (node (ref "S2") (pin "2") (pinfunction "S1_2") (pintype "passive"))
    )
    (net (code "164") (name "PROG_RX") (class "Default")
      (node (ref "IC15") (pin "36") (pinfunction "RXD0_36") (pintype "bidirectional"))
      (node (ref "JP1") (pin "2") (pinfunction "2_2") (pintype "passive"))
      (node (ref "R56") (pin "1") (pinfunction "1_1") (pintype "passive"))
    )
    (net (code "165") (name "PROG_TX") (class "Default")
      (node (ref "IC15") (pin "37") (pinfunction "TXD0_37") (pintype "bidirectional"))
      (node (ref "JP1") (pin "4") (pinfunction "4_4") (pintype "passive"))
      (node (ref "R57") (pin "1") (pinfunction "1_1") (pintype "passive"))
    )
    (net (code "166") (name "PWR1_3V3_EN") (class "Default")
      (node (ref "IC6") (pin "77") (pinfunction "PD8_77") (pintype "bidirectional"))
      (node (ref "Q9") (pin "1") (pinfunction "G_1") (pintype "passive"))
      (node (ref "R91") (pin "2") (pinfunction "2_2") (pintype "passive"))
    )
    (net (code "167") (name "PWR2_5V_EN") (class "Default")
      (node (ref "IC6") (pin "78") (pinfunction "PD9_78") (pintype "bidirectional"))
      (node (ref "Q11") (pin "1") (pinfunction "G_1") (pintype "passive"))
      (node (ref "R97") (pin "2") (pinfunction "2_2") (pintype "passive"))
    )
    (net (code "168") (name "PWR3_5V_EN") (class "Default")
      (node (ref "IC6") (pin "79") (pinfunction "PD10_79") (pintype "bidirectional"))
      (node (ref "Q13") (pin "1") (pinfunction "G_1") (pintype "passive"))
      (node (ref "R102") (pin "2") (pinfunction "2_2") (pintype "passive"))
    )
    (net (code "169") (name "PWR4_3V3_EN") (class "Default")
      (node (ref "IC6") (pin "80") (pinfunction "PD11_80") (pintype "bidirectional"))
      (node (ref "Q15") (pin "1") (pinfunction "G_1") (pintype "passive"))
      (node (ref "R107") (pin "2") (pinfunction "2_2") (pintype "passive"))
    )
    (net (code "170") (name "RCC_OSC32_IN") (class "Default")
      (node (ref "C99") (pin "1") (pinfunction "1_1") (pintype "passive"))
      (node (ref "IC6") (pin "8") (pinfunction "PC14/OSC32_IN_8") (pintype "bidirectional"))
      (node (ref "Q17") (pin "2") (pinfunction "2_2") (pintype "bidirectional"))
    )
    (net (code "171") (name "RCC_OSC32_OUT") (class "Default")
      (node (ref "C98") (pin "1") (pinfunction "1_1") (pintype "passive"))
      (node (ref "IC6") (pin "9") (pinfunction "PC15/OSC32_OUT_9") (pintype "bidirectional"))
      (node (ref "Q17") (pin "1") (pinfunction "1_1") (pintype "bidirectional"))
    )
    (net (code "172") (name "RCC_OSC_IN") (class "Default")
      (node (ref "C97") (pin "1") (pinfunction "1_1") (pintype "passive"))
      (node (ref "IC6") (pin "23") (pinfunction "PH0/OSC_IN_23") (pintype "bidirectional"))
      (node (ref "Q16") (pin "1") (pinfunction "1_1") (pintype "passive"))
    )
    (net (code "173") (name "RCC_OSC_OUT") (class "Default")
      (node (ref "C96") (pin "1") (pinfunction "1_1") (pintype "passive"))
      (node (ref "IC6") (pin "24") (pinfunction "PH1/OSC_OUT_24") (pintype "bidirectional"))
      (node (ref "Q16") (pin "3") (pinfunction "3_3") (pintype "passive"))
    )
    (net (code "174") (name "SAI1_FS_A") (class "Default")
      (node (ref "IC13") (pin "11") (pinfunction "B3_11") (pintype "bidirectional"))
      (node (ref "IC6") (pin "3") (pinfunction "PE4_3") (pintype "bidirectional"))
    )
    (net (code "175") (name "SAI1_SCK_A") (class "Default")
      (node (ref "IC13") (pin "10") (pinfunction "B4_10") (pintype "bidirectional"))
      (node (ref "IC6") (pin "4") (pinfunction "PE5_4") (pintype "bidirectional"))
    )
    (net (code "176") (name "SAI1_SD_A") (class "Default")
      (node (ref "IC13") (pin "12") (pinfunction "B2_12") (pintype "bidirectional"))
      (node (ref "IC6") (pin "48") (pinfunction "PB2_48") (pintype "bidirectional"))
    )
    (net (code "177") (name "SAI1_SD_B") (class "Default")
      (node (ref "IC13") (pin "13") (pinfunction "B1_13") (pintype "bidirectional"))
      (node (ref "IC6") (pin "2") (pinfunction "PE3_2") (pintype "bidirectional"))
    )
    (net (code "178") (name "SDMMC2_CK") (class "Default")
      (node (ref "IC6") (pin "122") (pinfunction "PD6_122") (pintype "bidirectional"))
      (node (ref "J10") (pin "10") (pinfunction "10_10") (pintype "bidirectional"))
    )
    (net (code "179") (name "SDMMC2_CMD") (class "Default")
      (node (ref "IC6") (pin "34") (pinfunction "PA0_34") (pintype "bidirectional"))
      (node (ref "J10") (pin "8") (pinfunction "8_8") (pintype "bidirectional"))
    )
    (net (code "180") (name "SDMMC2_D0") (class "Default")
      (node (ref "IC6") (pin "75") (pinfunction "PB14_75") (pintype "bidirectional"))
      (node (ref "J10") (pin "6") (pinfunction "6_6") (pintype "bidirectional"))
    )
    (net (code "181") (name "SDMMC2_D1") (class "Default")
      (node (ref "IC6") (pin "76") (pinfunction "PB15_76") (pintype "bidirectional"))
      (node (ref "J10") (pin "4") (pinfunction "4_4") (pintype "bidirectional"))
    )
    (net (code "182") (name "SDMMC2_D2") (class "Default")
      (node (ref "IC6") (pin "133") (pinfunction "PB3_133") (pintype "bidirectional"))
      (node (ref "J10") (pin "2") (pinfunction "2_2") (pintype "bidirectional"))
    )
    (net (code "183") (name "SDMMC2_D3") (class "Default")
      (node (ref "IC6") (pin "127") (pinfunction "PG12_127") (pintype "bidirectional"))
      (node (ref "J10") (pin "1") (pinfunction "1_1") (pintype "bidirectional"))
    )
    (net (code "184") (name "SPI1_MISO") (class "Default")
      (node (ref "IC15") (pin "4") (pinfunction "IO4_4") (pintype "bidirectional"))
      (node (ref "IC6") (pin "134") (pinfunction "PB4_134") (pintype "bidirectional"))
    )
    (net (code "185") (name "SPI1_MOSI") (class "Default")
      (node (ref "IC15") (pin "5") (pinfunction "IO5_5") (pintype "bidirectional"))
      (node (ref "IC6") (pin "123") (pinfunction "PD7_123") (pintype "bidirectional"))
    )
    (net (code "186") (name "SPI1_NSS") (class "Default")
      (node (ref "IC15") (pin "7") (pinfunction "IO7_7") (pintype "bidirectional"))
      (node (ref "IC6") (pin "125") (pinfunction "PG10_125") (pintype "bidirectional"))
    )
    (net (code "187") (name "SPI1_SCK") (class "Default")
      (node (ref "IC15") (pin "6") (pinfunction "IO6_6") (pintype "bidirectional"))
      (node (ref "IC6") (pin "41") (pinfunction "PA5_41") (pintype "bidirectional"))
    )
    (net (code "188") (name "SPI2_MISO") (class "Default")
      (node (ref "IC6") (pin "28") (pinfunction "PC2_C_28") (pintype "bidirectional"))
      (node (ref "J10") (pin "3") (pinfunction "3_3") (pintype "bidirectional"))
    )
    (net (code "189") (name "SPI2_MOSI") (class "Default")
      (node (ref "IC6") (pin "29") (pinfunction "PC3_C_29") (pintype "bidirectional"))
      (node (ref "J10") (pin "5") (pinfunction "5_5") (pintype "bidirectional"))
    )
    (net (code "190") (name "SPI2_NSS") (class "Default")
      (node (ref "IC6") (pin "73") (pinfunction "PB12_73") (pintype "bidirectional"))
      (node (ref "J10") (pin "7") (pinfunction "7_7") (pintype "bidirectional"))
    )
    (net (code "191") (name "SPI2_SCK") (class "Default")
      (node (ref "IC6") (pin "101") (pinfunction "PA9_101") (pintype "bidirectional"))
      (node (ref "J10") (pin "9") (pinfunction "9_9") (pintype "bidirectional"))
    )
    (net (code "192") (name "STM_USB_N") (class "Default")
      (node (ref "IC17") (pin "1") (pinfunction "D+_IN_1") (pintype "input"))
      (node (ref "IC6") (pin "103") (pinfunction "PA11_103") (pintype "bidirectional"))
    )
    (net (code "193") (name "STM_USB_P") (class "Default")
      (node (ref "IC17") (pin "3") (pinfunction "D-_IN_3") (pintype "input"))
      (node (ref "IC6") (pin "104") (pinfunction "PA12_104") (pintype "bidirectional"))
    )
    (net (code "194") (name "UART4_CTS") (class "Default")
      (node (ref "IC11") (pin "11") (pinfunction "B3_11") (pintype "bidirectional"))
      (node (ref "IC6") (pin "46") (pinfunction "PB0_46") (pintype "bidirectional"))
    )
    (net (code "195") (name "UART4_RTS") (class "Default")
      (node (ref "IC11") (pin "10") (pinfunction "B4_10") (pintype "bidirectional"))
      (node (ref "IC6") (pin "110") (pinfunction "PA15_110") (pintype "bidirectional"))
    )
    (net (code "196") (name "UART4_RX") (class "Default")
      (node (ref "IC11") (pin "12") (pinfunction "B2_12") (pintype "bidirectional"))
      (node (ref "IC6") (pin "114") (pinfunction "PD0_114") (pintype "bidirectional"))
    )
    (net (code "197") (name "UART4_TX") (class "Default")
      (node (ref "IC11") (pin "13") (pinfunction "B1_13") (pintype "bidirectional"))
      (node (ref "IC6") (pin "115") (pinfunction "PD1_115") (pintype "bidirectional"))
    )
    (net (code "198") (name "UART5_CTS") (class "Default")
      (node (ref "IC6") (pin "99") (pinfunction "PC9_99") (pintype "bidirectional"))
      (node (ref "J8") (pin "3") (pinfunction "P_3") (pintype "bidirectional"))
    )
    (net (code "199") (name "UART5_RTS") (class "Default")
      (node (ref "IC6") (pin "98") (pinfunction "PC8_98") (pintype "bidirectional"))
      (node (ref "J8") (pin "2") (pinfunction "P_2") (pintype "bidirectional"))
    )
    (net (code "200") (name "UART5_RX") (class "Default")
      (node (ref "IC6") (pin "116") (pinfunction "PD2_116") (pintype "bidirectional"))
      (node (ref "J8") (pin "5") (pinfunction "P_5") (pintype "bidirectional"))
    )
    (net (code "201") (name "UART5_TX") (class "Default")
      (node (ref "IC6") (pin "74") (pinfunction "PB13_74") (pintype "bidirectional"))
      (node (ref "J8") (pin "4") (pinfunction "P_4") (pintype "bidirectional"))
    )
    (net (code "202") (name "UART7_CTS") (class "Default")
      (node (ref "IC6") (pin "63") (pinfunction "PE10_63") (pintype "bidirectional"))
      (node (ref "J9") (pin "2") (pinfunction "2_2") (pintype "bidirectional"))
    )
    (net (code "203") (name "UART7_RTS") (class "Default")
      (node (ref "IC6") (pin "60") (pinfunction "PE9_60") (pintype "bidirectional"))
      (node (ref "J9") (pin "1") (pinfunction "1_1") (pintype "bidirectional"))
    )
    (net (code "204") (name "UART7_RX") (class "Default")
      (node (ref "IC6") (pin "18") (pinfunction "PF6_18") (pintype "bidirectional"))
      (node (ref "J9") (pin "6") (pinfunction "6_6") (pintype "bidirectional"))
    )
    (net (code "205") (name "UART7_TX") (class "Default")
      (node (ref "IC6") (pin "19") (pinfunction "PF7_19") (pintype "bidirectional"))
      (node (ref "J9") (pin "4") (pinfunction "4_4") (pintype "bidirectional"))
    )
    (net (code "206") (name "USB1_N") (class "Default")
      (node (ref "IC17") (pin "6") (pinfunction "D+_OUT_6") (pintype "output"))
      (node (ref "J12") (pin "2") (pinfunction "2_2") (pintype "bidirectional"))
    )
    (net (code "207") (name "USB1_P") (class "Default")
      (node (ref "IC17") (pin "4") (pinfunction "D-_OUT_4") (pintype "output"))
      (node (ref "J12") (pin "3") (pinfunction "3_3") (pintype "bidirectional"))
    )
    (net (code "208") (name "USB2_N") (class "Default")
      (node (ref "IC14") (pin "6") (pinfunction "D+_OUT_6") (pintype "output"))
      (node (ref "TP2") (pin "TP") (pinfunction "TP_TP") (pintype "input"))
    )
    (net (code "209") (name "USB_P") (class "Default")
      (node (ref "IC14") (pin "4") (pinfunction "D-_OUT_4") (pintype "output"))
      (node (ref "TP3") (pin "TP") (pinfunction "TP_TP") (pintype "input"))
    )
    (net (code "210") (name "USER_LED") (class "Default")
      (node (ref "IC6") (pin "68") (pinfunction "PE15_68") (pintype "bidirectional"))
      (node (ref "R117") (pin "1") (pinfunction "1_1") (pintype "passive"))
    )
    (net (code "211") (name "VBAT") (class "Default")
      (node (ref "C1") (pin "+") (pinfunction "+_+") (pintype "passive"))
      (node (ref "C15") (pin "1") (pinfunction "1_1") (pintype "passive"))
      (node (ref "C16") (pin "1") (pinfunction "1_1") (pintype "passive"))
      (node (ref "C2") (pin "1") (pinfunction "1_1") (pintype "passive"))
      (node (ref "C3") (pin "1") (pinfunction "1_1") (pintype "passive"))
      (node (ref "F1") (pin "2A") (pinfunction "2A_2A") (pintype "passive"))
      (node (ref "F1") (pin "2B") (pinfunction "2B_2B") (pintype "passive"))
      (node (ref "IC1") (pin "1") (pinfunction "VIN_1") (pintype "bidirectional"))
      (node (ref "IC4") (pin "7") (pinfunction "VIN_7") (pintype "bidirectional"))
      (node (ref "Q1") (pin "2") (pinfunction "S_2") (pintype "passive"))
      (node (ref "R1") (pin "1") (pinfunction "1_1") (pintype "passive"))
      (node (ref "R114") (pin "2") (pinfunction "2_2") (pintype "passive"))
      (node (ref "R6") (pin "1") (pinfunction "1_1") (pintype "passive"))
    )
    (net (code "212") (name "VCCIO") (class "Default")
      (node (ref "C83") (pin "1") (pinfunction "1_1") (pintype "passive"))
      (node (ref "C84") (pin "1") (pinfunction "1_1") (pintype "passive"))
      (node (ref "C85") (pin "1") (pinfunction "1_1") (pintype "passive"))
      (node (ref "C86") (pin "1") (pinfunction "1_1") (pintype "passive"))
      (node (ref "IC16") (pin "1") (pinfunction "VDD2A_1") (pintype "bidirectional"))
      (node (ref "IC16") (pin "19") (pinfunction "VDD1A_19") (pintype "bidirectional"))
      (node (ref "J4") (pin "5") (pinfunction "CT_1_5") (pintype "bidirectional"))
      (node (ref "J4") (pin "6") (pinfunction "CT_2_6") (pintype "bidirectional"))
      (node (ref "L7") (pin "2") (pinfunction "2_2") (pintype "passive"))
      (node (ref "R61") (pin "2") (pinfunction "2_2") (pintype "passive"))
      (node (ref "R62") (pin "2") (pinfunction "2_2") (pintype "passive"))
      (node (ref "R63") (pin "2") (pinfunction "2_2") (pintype "passive"))
      (node (ref "R64") (pin "2") (pinfunction "2_2") (pintype "passive"))
    )
    (net (code "213") (name "VDDA") (class "Default")
      (node (ref "C12") (pin "1") (pinfunction "1_1") (pintype "passive"))
      (node (ref "C36") (pin "1") (pinfunction "1_1") (pintype "passive"))
      (node (ref "C37") (pin "1") (pinfunction "1_1") (pintype "passive"))
      (node (ref "IC6") (pin "32") (pinfunction "VREF+_32") (pintype "power_in"))
      (node (ref "IC6") (pin "33") (pinfunction "VDDA_33") (pintype "power_in"))
      (node (ref "L3") (pin "2") (pinfunction "2_2") (pintype "passive"))
    )
    (net (code "214") (name "_ETH_CRSDV") (class "Default")
      (node (ref "IC16") (pin "11") (pinfunction "CRSDV_11") (pintype "bidirectional"))
      (node (ref "R67") (pin "1") (pinfunction "1_1") (pintype "passive"))
      (node (ref "R73") (pin "2") (pinfunction "2_2") (pintype "passive"))
    )
    (net (code "215") (name "_ETH_MDC") (class "Default")
      (node (ref "IC16") (pin "13") (pinfunction "MDC_13") (pintype "bidirectional"))
      (node (ref "R75") (pin "2") (pinfunction "2_2") (pintype "passive"))
    )
    (net (code "216") (name "_ETH_MDIO") (class "Default")
      (node (ref "IC16") (pin "12") (pinfunction "MDIO_12") (pintype "bidirectional"))
      (node (ref "R65") (pin "1") (pinfunction "1_1") (pintype "passive"))
      (node (ref "R74") (pin "2") (pinfunction "2_2") (pintype "passive"))
    )
    (net (code "217") (name "_ETH_RXD0") (class "Default")
      (node (ref "IC16") (pin "8") (pinfunction "RXD0_8") (pintype "bidirectional"))
      (node (ref "R69") (pin "1") (pinfunction "1_1") (pintype "passive"))
      (node (ref "R71") (pin "2") (pinfunction "2_2") (pintype "passive"))
    )
    (net (code "218") (name "_ETH_RXD1") (class "Default")
      (node (ref "IC16") (pin "7") (pinfunction "RXD1_7") (pintype "bidirectional"))
      (node (ref "R68") (pin "1") (pinfunction "1_1") (pintype "passive"))
      (node (ref "R72") (pin "2") (pinfunction "2_2") (pintype "passive"))
    )
    (net (code "219") (name "_ETH_RXERR") (class "Default")
      (node (ref "IC16") (pin "10") (pinfunction "RXER_10") (pintype "bidirectional"))
      (node (ref "R79") (pin "2") (pinfunction "2_2") (pintype "passive"))
    )
    (net (code "220") (name "_ETH_TXD0") (class "Default")
      (node (ref "IC16") (pin "17") (pinfunction "TXD0_17") (pintype "bidirectional"))
      (node (ref "R77") (pin "2") (pinfunction "2_2") (pintype "passive"))
    )
    (net (code "221") (name "_ETH_TXD1") (class "Default")
      (node (ref "IC16") (pin "18") (pinfunction "TXD1_18") (pintype "bidirectional"))
      (node (ref "R78") (pin "2") (pinfunction "2_2") (pintype "passive"))
    )
    (net (code "222") (name "_ETH_TXEN") (class "Default")
      (node (ref "IC16") (pin "16") (pinfunction "TXEN_16") (pintype "bidirectional"))
      (node (ref "R76") (pin "2") (pinfunction "2_2") (pintype "passive"))
    )
    (net (code "223") (name "unconnected-(IC6A-PB5-Pad135)") (class "Default")
      (node (ref "IC6") (pin "135") (pinfunction "PB5_135") (pintype "bidirectional"))
    )
    (net (code "224") (name "unconnected-(IC6A-PC0-Pad26)") (class "Default")
      (node (ref "IC6") (pin "26") (pinfunction "PC0_26") (pintype "bidirectional"))
    )
    (net (code "225") (name "unconnected-(IC6A-PC13-Pad7)") (class "Default")
      (node (ref "IC6") (pin "7") (pinfunction "PC13_7") (pintype "bidirectional"))
    )
    (net (code "226") (name "unconnected-(IC6A-PD4-Pad118)") (class "Default")
      (node (ref "IC6") (pin "118") (pinfunction "PD4_118") (pintype "bidirectional"))
    )
    (net (code "227") (name "unconnected-(IC6A-PD5-Pad119)") (class "Default")
      (node (ref "IC6") (pin "119") (pinfunction "PD5_119") (pintype "bidirectional"))
    )
    (net (code "228") (name "unconnected-(IC6A-PD12-Pad81)") (class "Default")
      (node (ref "IC6") (pin "81") (pinfunction "PD12_81") (pintype "bidirectional"))
    )
    (net (code "229") (name "unconnected-(IC6A-PD13-Pad82)") (class "Default")
      (node (ref "IC6") (pin "82") (pinfunction "PD13_82") (pintype "bidirectional"))
    )
    (net (code "230") (name "unconnected-(IC6A-PD14-Pad85)") (class "Default")
      (node (ref "IC6") (pin "85") (pinfunction "PD14_85") (pintype "bidirectional"))
    )
    (net (code "231") (name "unconnected-(IC6A-PD15-Pad86)") (class "Default")
      (node (ref "IC6") (pin "86") (pinfunction "PD15_86") (pintype "bidirectional"))
    )
    (net (code "232") (name "unconnected-(IC6B-PE7-Pad58)") (class "Default")
      (node (ref "IC6") (pin "58") (pinfunction "PE7_58") (pintype "bidirectional"))
    )
    (net (code "233") (name "unconnected-(IC6B-PE8-Pad59)") (class "Default")
      (node (ref "IC6") (pin "59") (pinfunction "PE8_59") (pintype "bidirectional"))
    )
    (net (code "234") (name "unconnected-(IC6B-PE12-Pad65)") (class "Default")
      (node (ref "IC6") (pin "65") (pinfunction "PE12_65") (pintype "bidirectional"))
    )
    (net (code "235") (name "unconnected-(IC6B-PE13-Pad66)") (class "Default")
      (node (ref "IC6") (pin "66") (pinfunction "PE13_66") (pintype "bidirectional"))
    )
    (net (code "236") (name "unconnected-(IC6B-PE14-Pad67)") (class "Default")
      (node (ref "IC6") (pin "67") (pinfunction "PE14_67") (pintype "bidirectional"))
    )
    (net (code "237") (name "unconnected-(IC6B-PF5-Pad15)") (class "Default")
      (node (ref "IC6") (pin "15") (pinfunction "PF5_15") (pintype "bidirectional"))
    )
    (net (code "238") (name "unconnected-(IC6B-PF8-Pad20)") (class "Default")
      (node (ref "IC6") (pin "20") (pinfunction "PF8_20") (pintype "bidirectional"))
    )
    (net (code "239") (name "unconnected-(IC6B-PF9-Pad21)") (class "Default")
      (node (ref "IC6") (pin "21") (pinfunction "PF9_21") (pintype "bidirectional"))
    )
    (net (code "240") (name "unconnected-(IC6B-PF11-Pad49)") (class "Default")
      (node (ref "IC6") (pin "49") (pinfunction "PF11_49") (pintype "bidirectional"))
    )
    (net (code "241") (name "unconnected-(IC6B-PF12-Pad50)") (class "Default")
      (node (ref "IC6") (pin "50") (pinfunction "PF12_50") (pintype "bidirectional"))
    )
    (net (code "242") (name "unconnected-(IC6B-PF13-Pad53)") (class "Default")
      (node (ref "IC6") (pin "53") (pinfunction "PF13_53") (pintype "bidirectional"))
    )
    (net (code "243") (name "unconnected-(IC6B-PG3-Pad88)") (class "Default")
      (node (ref "IC6") (pin "88") (pinfunction "PG3_88") (pintype "bidirectional"))
    )
    (net (code "244") (name "unconnected-(IC6B-PG6-Pad91)") (class "Default")
      (node (ref "IC6") (pin "91") (pinfunction "PG6_91") (pintype "bidirectional"))
    )
    (net (code "245") (name "unconnected-(IC6B-PG8-Pad93)") (class "Default")
      (node (ref "IC6") (pin "93") (pinfunction "PG8_93") (pintype "bidirectional"))
    )
    (net (code "246") (name "unconnected-(IC6B-PG15-Pad132)") (class "Default")
      (node (ref "IC6") (pin "132") (pinfunction "PG15_132") (pintype "bidirectional"))
    )
    (net (code "247") (name "unconnected-(IC11-NC_1-Pad6)") (class "Default")
      (node (ref "IC11") (pin "6") (pinfunction "NC_1_6") (pintype "bidirectional"))
    )
    (net (code "248") (name "unconnected-(IC11-NC_2-Pad9)") (class "Default")
      (node (ref "IC11") (pin "9") (pinfunction "NC_2_9") (pintype "bidirectional"))
    )
    (net (code "249") (name "unconnected-(IC12A-ADC-Pad25)") (class "Default")
      (node (ref "IC12") (pin "25") (pinfunction "ADC_25") (pintype "bidirectional"))
    )
    (net (code "250") (name "unconnected-(IC12A-DCD-Pad5)") (class "Default")
      (node (ref "IC12") (pin "5") (pinfunction "DCD_5") (pintype "bidirectional"))
    )
    (net (code "251") (name "unconnected-(IC12A-DTR-Pad3)") (class "Default")
      (node (ref "IC12") (pin "3") (pinfunction "DTR_3") (pintype "bidirectional"))
    )
    (net (code "252") (name "unconnected-(IC12A-GPIO1-Pad19)") (class "Default")
      (node (ref "IC12") (pin "19") (pinfunction "GPIO1_19") (pintype "bidirectional"))
    )
    (net (code "253") (name "unconnected-(IC12A-GPIO2-Pad20)") (class "Default")
      (node (ref "IC12") (pin "20") (pinfunction "GPIO2_20") (pintype "bidirectional"))
    )
    (net (code "254") (name "unconnected-(IC12A-GPIO3-Pad21)") (class "Default")
      (node (ref "IC12") (pin "21") (pinfunction "GPIO3_21") (pintype "bidirectional"))
    )
    (net (code "255") (name "unconnected-(IC12A-GPIO4(UART3_RX)-Pad49)") (class "Default")
      (node (ref "IC12") (pin "49") (pinfunction "GPIO4(UART3_RX)_49") (pintype "bidirectional"))
    )
    (net (code "256") (name "unconnected-(IC12A-GPIO5(UART3_TX)-Pad50)") (class "Default")
      (node (ref "IC12") (pin "50") (pinfunction "GPIO5(UART3_TX)_50") (pintype "bidirectional"))
    )
    (net (code "257") (name "unconnected-(IC12A-GPIO9-Pad48)") (class "Default")
      (node (ref "IC12") (pin "48") (pinfunction "GPIO9_48") (pintype "bidirectional"))
    )
    (net (code "258") (name "unconnected-(IC12A-GPIO10-Pad67)") (class "Default")
      (node (ref "IC12") (pin "67") (pinfunction "GPIO10_67") (pintype "bidirectional"))
    )
    (net (code "259") (name "unconnected-(IC12A-GPIO11-Pad68)") (class "Default")
      (node (ref "IC12") (pin "68") (pinfunction "GPIO11_68") (pintype "bidirectional"))
    )
    (net (code "260") (name "unconnected-(IC12A-I2C_SCL-Pad38)") (class "Default")
      (node (ref "IC12") (pin "38") (pinfunction "I2C_SCL_38") (pintype "bidirectional"))
    )
    (net (code "261") (name "unconnected-(IC12A-I2C_SDA-Pad37)") (class "Default")
      (node (ref "IC12") (pin "37") (pinfunction "I2C_SDA_37") (pintype "bidirectional"))
    )
    (net (code "262") (name "unconnected-(IC12A-NETLIGHT-Pad52)") (class "Default")
      (node (ref "IC12") (pin "52") (pinfunction "NETLIGHT_52") (pintype "bidirectional"))
    )
    (net (code "263") (name "unconnected-(IC12A-RI-Pad4)") (class "Default")
      (node (ref "IC12") (pin "4") (pinfunction "RI_4") (pintype "bidirectional"))
    )
    (net (code "264") (name "unconnected-(IC12A-STATUS-Pad66)") (class "Default")
      (node (ref "IC12") (pin "66") (pinfunction "STATUS_66") (pintype "bidirectional"))
    )
    (net (code "265") (name "unconnected-(IC12A-UART_LOG_RX-Pad22)") (class "Default")
      (node (ref "IC12") (pin "22") (pinfunction "UART_LOG_RX_22") (pintype "bidirectional"))
    )
    (net (code "266") (name "unconnected-(IC12A-UART_LOG_TX-Pad23)") (class "Default")
      (node (ref "IC12") (pin "23") (pinfunction "UART_LOG_TX_23") (pintype "bidirectional"))
    )
    (net (code "267") (name "unconnected-(IC13-NC_1-Pad6)") (class "Default")
      (node (ref "IC13") (pin "6") (pinfunction "NC_1_6") (pintype "bidirectional"))
    )
    (net (code "268") (name "unconnected-(IC13-NC_2-Pad9)") (class "Default")
      (node (ref "IC13") (pin "9") (pinfunction "NC_2_9") (pintype "bidirectional"))
    )
    (net (code "269") (name "unconnected-(IC15-IO1-Pad39)") (class "Default")
      (node (ref "IC15") (pin "39") (pinfunction "IO1_39") (pintype "bidirectional"))
    )
    (net (code "270") (name "unconnected-(IC15-IO3-Pad15)") (class "Default")
      (node (ref "IC15") (pin "15") (pinfunction "IO3_15") (pintype "bidirectional"))
    )
    (net (code "271") (name "unconnected-(IC15-IO8-Pad12)") (class "Default")
      (node (ref "IC15") (pin "12") (pinfunction "IO8_12") (pintype "bidirectional"))
    )
    (net (code "272") (name "unconnected-(IC15-IO9-Pad17)") (class "Default")
      (node (ref "IC15") (pin "17") (pinfunction "IO9_17") (pintype "bidirectional"))
    )
    (net (code "273") (name "unconnected-(IC15-IO10-Pad18)") (class "Default")
      (node (ref "IC15") (pin "18") (pinfunction "IO10_18") (pintype "bidirectional"))
    )
    (net (code "274") (name "unconnected-(IC15-IO11-Pad19)") (class "Default")
      (node (ref "IC15") (pin "19") (pinfunction "IO11_19") (pintype "bidirectional"))
    )
    (net (code "275") (name "unconnected-(IC15-IO12-Pad20)") (class "Default")
      (node (ref "IC15") (pin "20") (pinfunction "IO12_20") (pintype "bidirectional"))
    )
    (net (code "276") (name "unconnected-(IC15-IO13-Pad21)") (class "Default")
      (node (ref "IC15") (pin "21") (pinfunction "IO13_21") (pintype "bidirectional"))
    )
    (net (code "277") (name "unconnected-(IC15-IO14-Pad22)") (class "Default")
      (node (ref "IC15") (pin "22") (pinfunction "IO14_22") (pintype "bidirectional"))
    )
    (net (code "278") (name "unconnected-(IC15-IO15-Pad8)") (class "Default")
      (node (ref "IC15") (pin "8") (pinfunction "IO15_8") (pintype "bidirectional"))
    )
    (net (code "279") (name "unconnected-(IC15-IO16-Pad9)") (class "Default")
      (node (ref "IC15") (pin "9") (pinfunction "IO16_9") (pintype "bidirectional"))
    )
    (net (code "280") (name "unconnected-(IC15-IO17-Pad10)") (class "Default")
      (node (ref "IC15") (pin "10") (pinfunction "IO17_10") (pintype "bidirectional"))
    )
    (net (code "281") (name "unconnected-(IC15-IO18-Pad11)") (class "Default")
      (node (ref "IC15") (pin "11") (pinfunction "IO18_11") (pintype "bidirectional"))
    )
    (net (code "282") (name "unconnected-(IC15-IO19-Pad13)") (class "Default")
      (node (ref "IC15") (pin "13") (pinfunction "IO19_13") (pintype "bidirectional"))
    )
    (net (code "283") (name "unconnected-(IC15-IO20-Pad14)") (class "Default")
      (node (ref "IC15") (pin "14") (pinfunction "IO20_14") (pintype "bidirectional"))
    )
    (net (code "284") (name "unconnected-(IC15-IO21-Pad23)") (class "Default")
      (node (ref "IC15") (pin "23") (pinfunction "IO21_23") (pintype "bidirectional"))
    )
    (net (code "285") (name "unconnected-(IC15-IO35-Pad28)") (class "Default")
      (node (ref "IC15") (pin "28") (pinfunction "IO35_28") (pintype "bidirectional"))
    )
    (net (code "286") (name "unconnected-(IC15-IO36-Pad29)") (class "Default")
      (node (ref "IC15") (pin "29") (pinfunction "IO36_29") (pintype "bidirectional"))
    )
    (net (code "287") (name "unconnected-(IC15-IO37-Pad30)") (class "Default")
      (node (ref "IC15") (pin "30") (pinfunction "IO37_30") (pintype "bidirectional"))
    )
    (net (code "288") (name "unconnected-(IC15-IO38-Pad31)") (class "Default")
      (node (ref "IC15") (pin "31") (pinfunction "IO38_31") (pintype "bidirectional"))
    )
    (net (code "289") (name "unconnected-(IC15-IO39-Pad32)") (class "Default")
      (node (ref "IC15") (pin "32") (pinfunction "IO39_32") (pintype "bidirectional"))
    )
    (net (code "290") (name "unconnected-(IC15-IO40-Pad33)") (class "Default")
      (node (ref "IC15") (pin "33") (pinfunction "IO40_33") (pintype "bidirectional"))
    )
    (net (code "291") (name "unconnected-(IC15-IO41-Pad34)") (class "Default")
      (node (ref "IC15") (pin "34") (pinfunction "IO41_34") (pintype "bidirectional"))
    )
    (net (code "292") (name "unconnected-(IC15-IO42-Pad35)") (class "Default")
      (node (ref "IC15") (pin "35") (pinfunction "IO42_35") (pintype "bidirectional"))
    )
    (net (code "293") (name "unconnected-(IC15-IO45-Pad26)") (class "Default")
      (node (ref "IC15") (pin "26") (pinfunction "IO45_26") (pintype "bidirectional"))
    )
    (net (code "294") (name "unconnected-(IC15-IO46-Pad16)") (class "Default")
      (node (ref "IC15") (pin "16") (pinfunction "IO46_16") (pintype "bidirectional"))
    )
    (net (code "295") (name "unconnected-(IC15-IO47-Pad24)") (class "Default")
      (node (ref "IC15") (pin "24") (pinfunction "IO47_24") (pintype "bidirectional"))
    )
    (net (code "296") (name "unconnected-(IC15-IO48-Pad25)") (class "Default")
      (node (ref "IC15") (pin "25") (pinfunction "IO48_25") (pintype "bidirectional"))
    )
    (net (code "297") (name "unconnected-(IC16-XTAL_OUT-Pad4)") (class "Default")
      (node (ref "IC16") (pin "4") (pinfunction "XTAL_OUT_4") (pintype "bidirectional"))
    )
    (net (code "298") (name "unconnected-(J2-VPP-PadC6)") (class "Default")
      (node (ref "J2") (pin "C6") (pinfunction "VPP_C6") (pintype "bidirectional"))
    )
    (net (code "299") (name "unconnected-(J4-NC_1-Pad9)") (class "Default")
      (node (ref "J4") (pin "9") (pinfunction "NC_1_9") (pintype "bidirectional"))
    )
    (net (code "300") (name "unconnected-(J4-NC_2-Pad10)") (class "Default")
      (node (ref "J4") (pin "10") (pinfunction "NC_2_10") (pintype "bidirectional"))
    )
    (net (code "301") (name "unconnected-(J4-PadMP1)") (class "Default")
      (node (ref "J4") (pin "MP1") (pinfunction "MP1_MP1") (pintype "bidirectional"))
    )
    (net (code "302") (name "unconnected-(J4-PadMP2)") (class "Default")
      (node (ref "J4") (pin "MP2") (pinfunction "MP2_MP2") (pintype "bidirectional"))
    )
    (net (code "303") (name "unconnected-(J5-PadMP1)") (class "Default")
      (node (ref "J5") (pin "MP1") (pinfunction "MP1_MP1") (pintype "bidirectional"))
    )
    (net (code "304") (name "unconnected-(J5-PadMP2)") (class "Default")
      (node (ref "J5") (pin "MP2") (pinfunction "MP2_MP2") (pintype "bidirectional"))
    )
    (net (code "305") (name "unconnected-(J7-Pad1)") (class "Default")
      (node (ref "J7") (pin "1") (pinfunction "1_1") (pintype "bidirectional"))
    )
    (net (code "306") (name "unconnected-(J7-Pad4)") (class "Default")
      (node (ref "J7") (pin "4") (pinfunction "4_4") (pintype "bidirectional"))
    )
    (net (code "307") (name "unconnected-(J7-PadMP1)") (class "Default")
      (node (ref "J7") (pin "MP1") (pinfunction "MP1_MP1") (pintype "bidirectional"))
    )
    (net (code "308") (name "unconnected-(J7-PadMP2)") (class "Default")
      (node (ref "J7") (pin "MP2") (pinfunction "MP2_MP2") (pintype "bidirectional"))
    )
    (net (code "309") (name "unconnected-(J10-Pad13)") (class "Default")
      (node (ref "J10") (pin "13") (pinfunction "13_13") (pintype "bidirectional"))
    )
    (net (code "310") (name "unconnected-(J11B-P-Pad2)") (class "Default")
      (node (ref "J11") (pin "2") (pinfunction "P_2") (pintype "bidirectional"))
    )
    (net (code "311") (name "unconnected-(J11C-P-Pad3)") (class "Default")
      (node (ref "J11") (pin "3") (pinfunction "P_3") (pintype "bidirectional"))
    )
    (net (code "312") (name "unconnected-(J11F-P-Pad6)") (class "Default")
      (node (ref "J11") (pin "6") (pinfunction "P_6") (pintype "bidirectional"))
    )
  )
)
